# ME461_F28379D.net
KiCad netlist of a schematic drawn in EAGLE
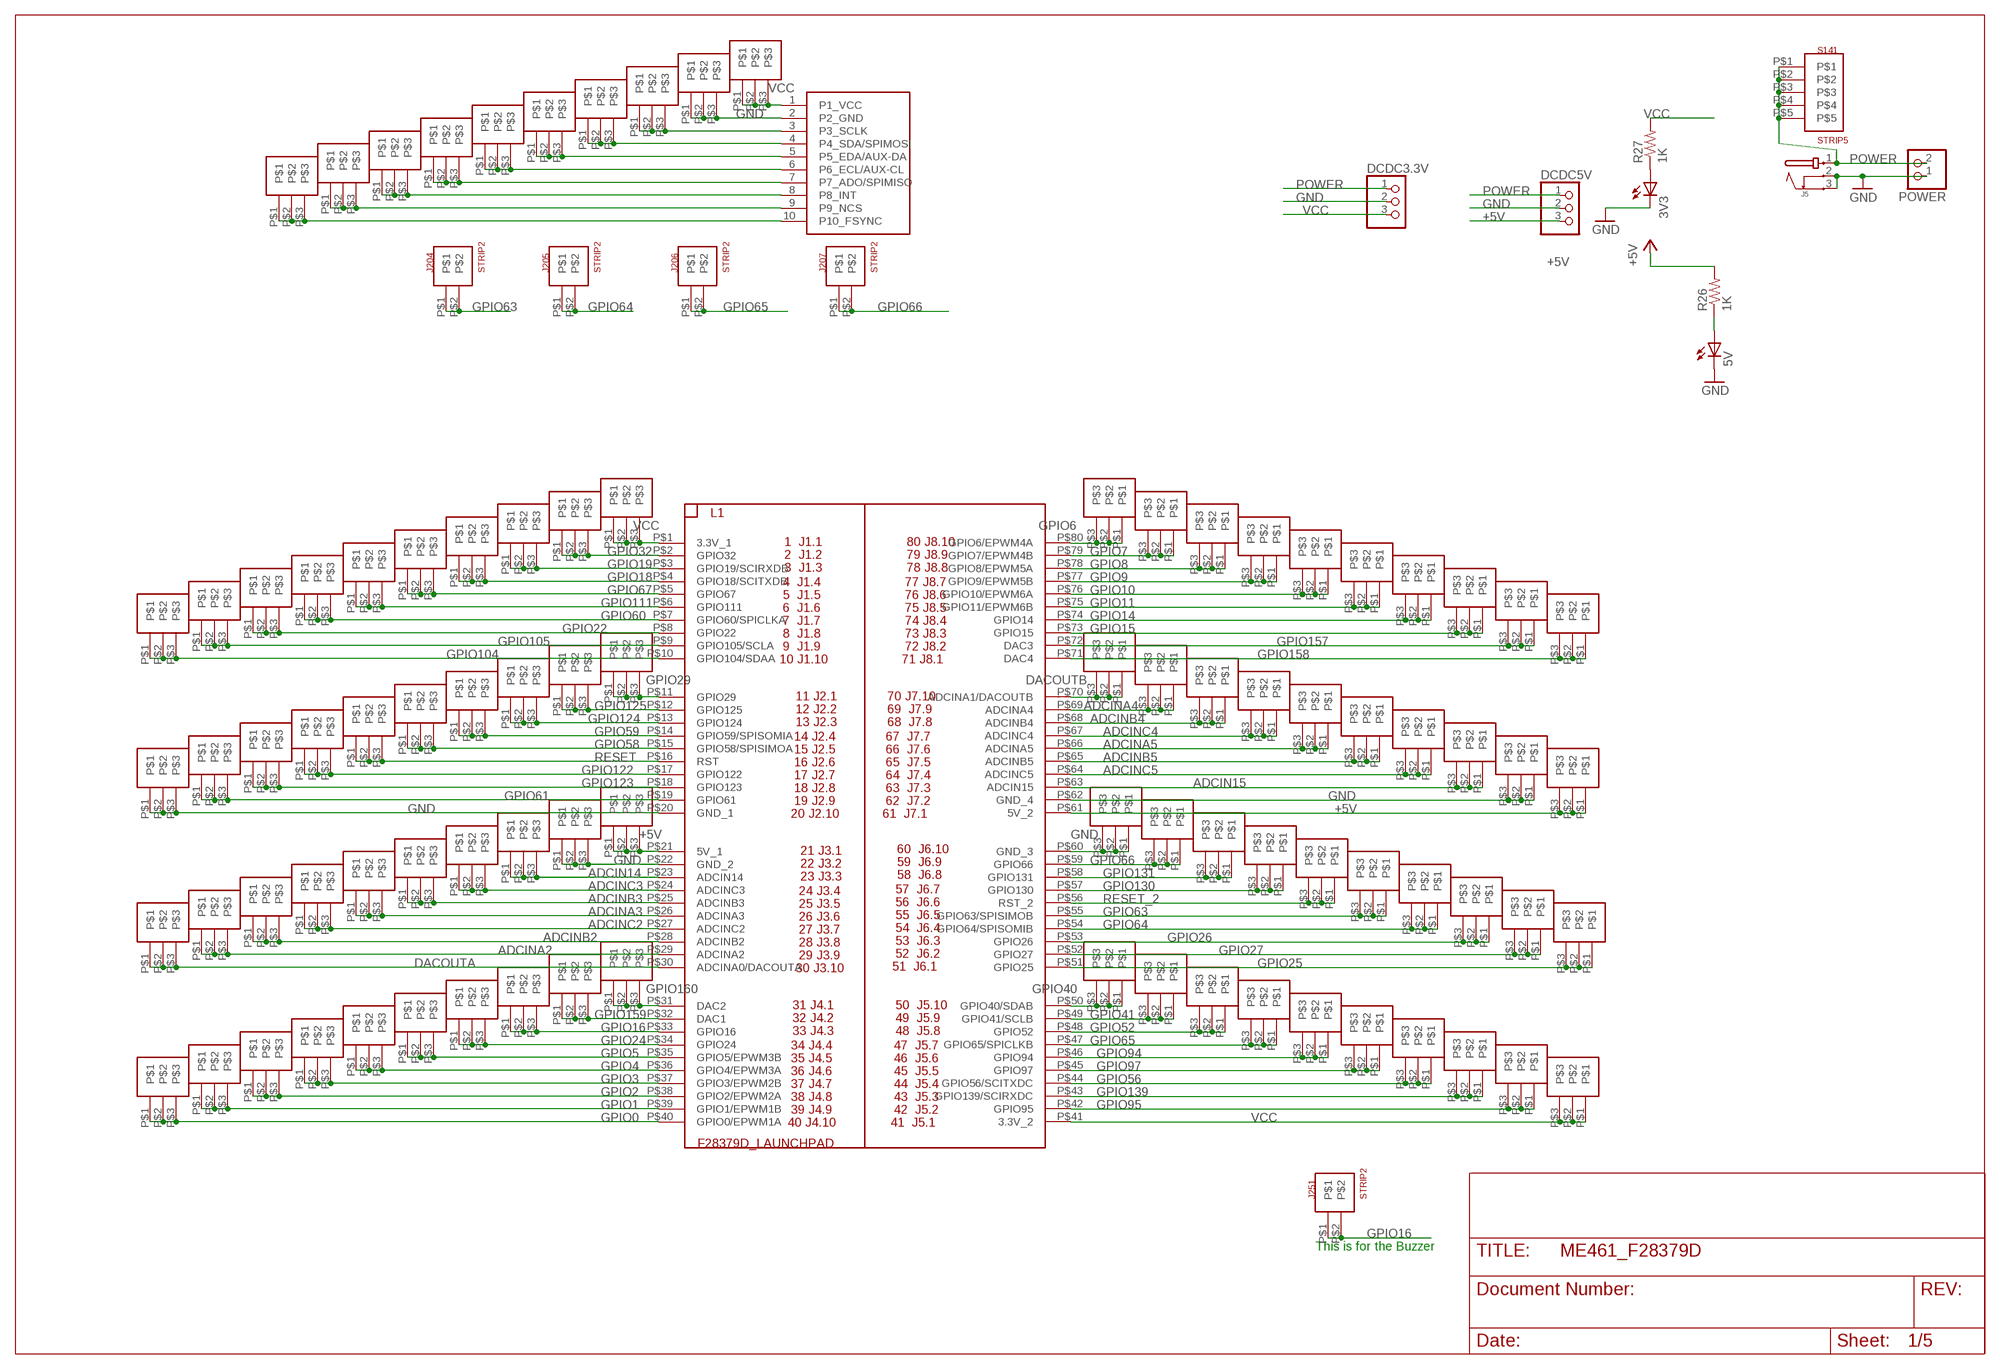
[diagram p0: schematic, sheet 1]
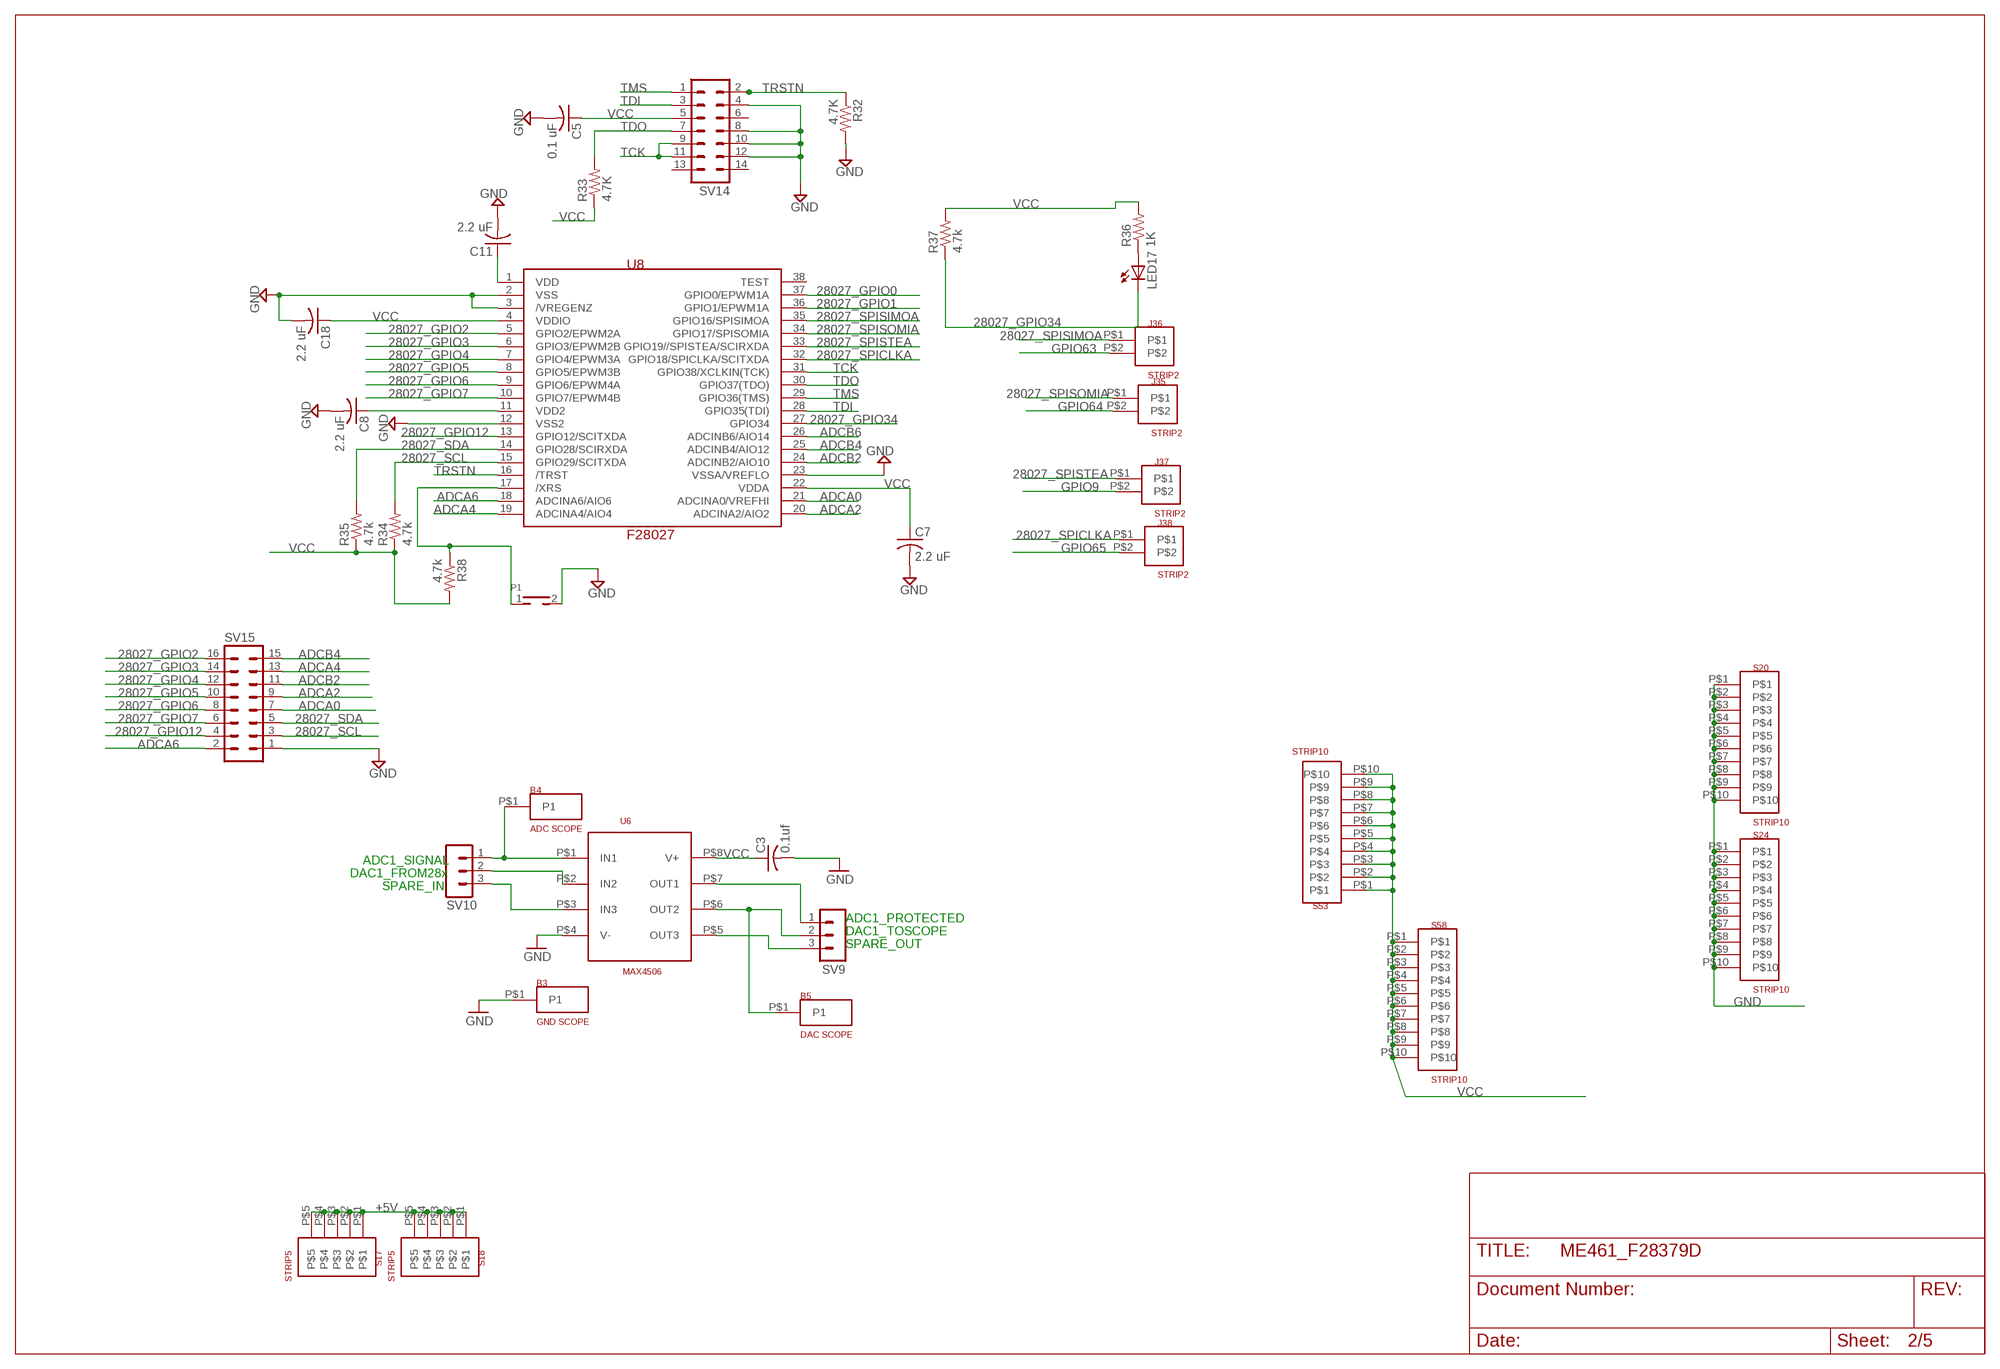
[diagram p1: schematic, sheet 2]
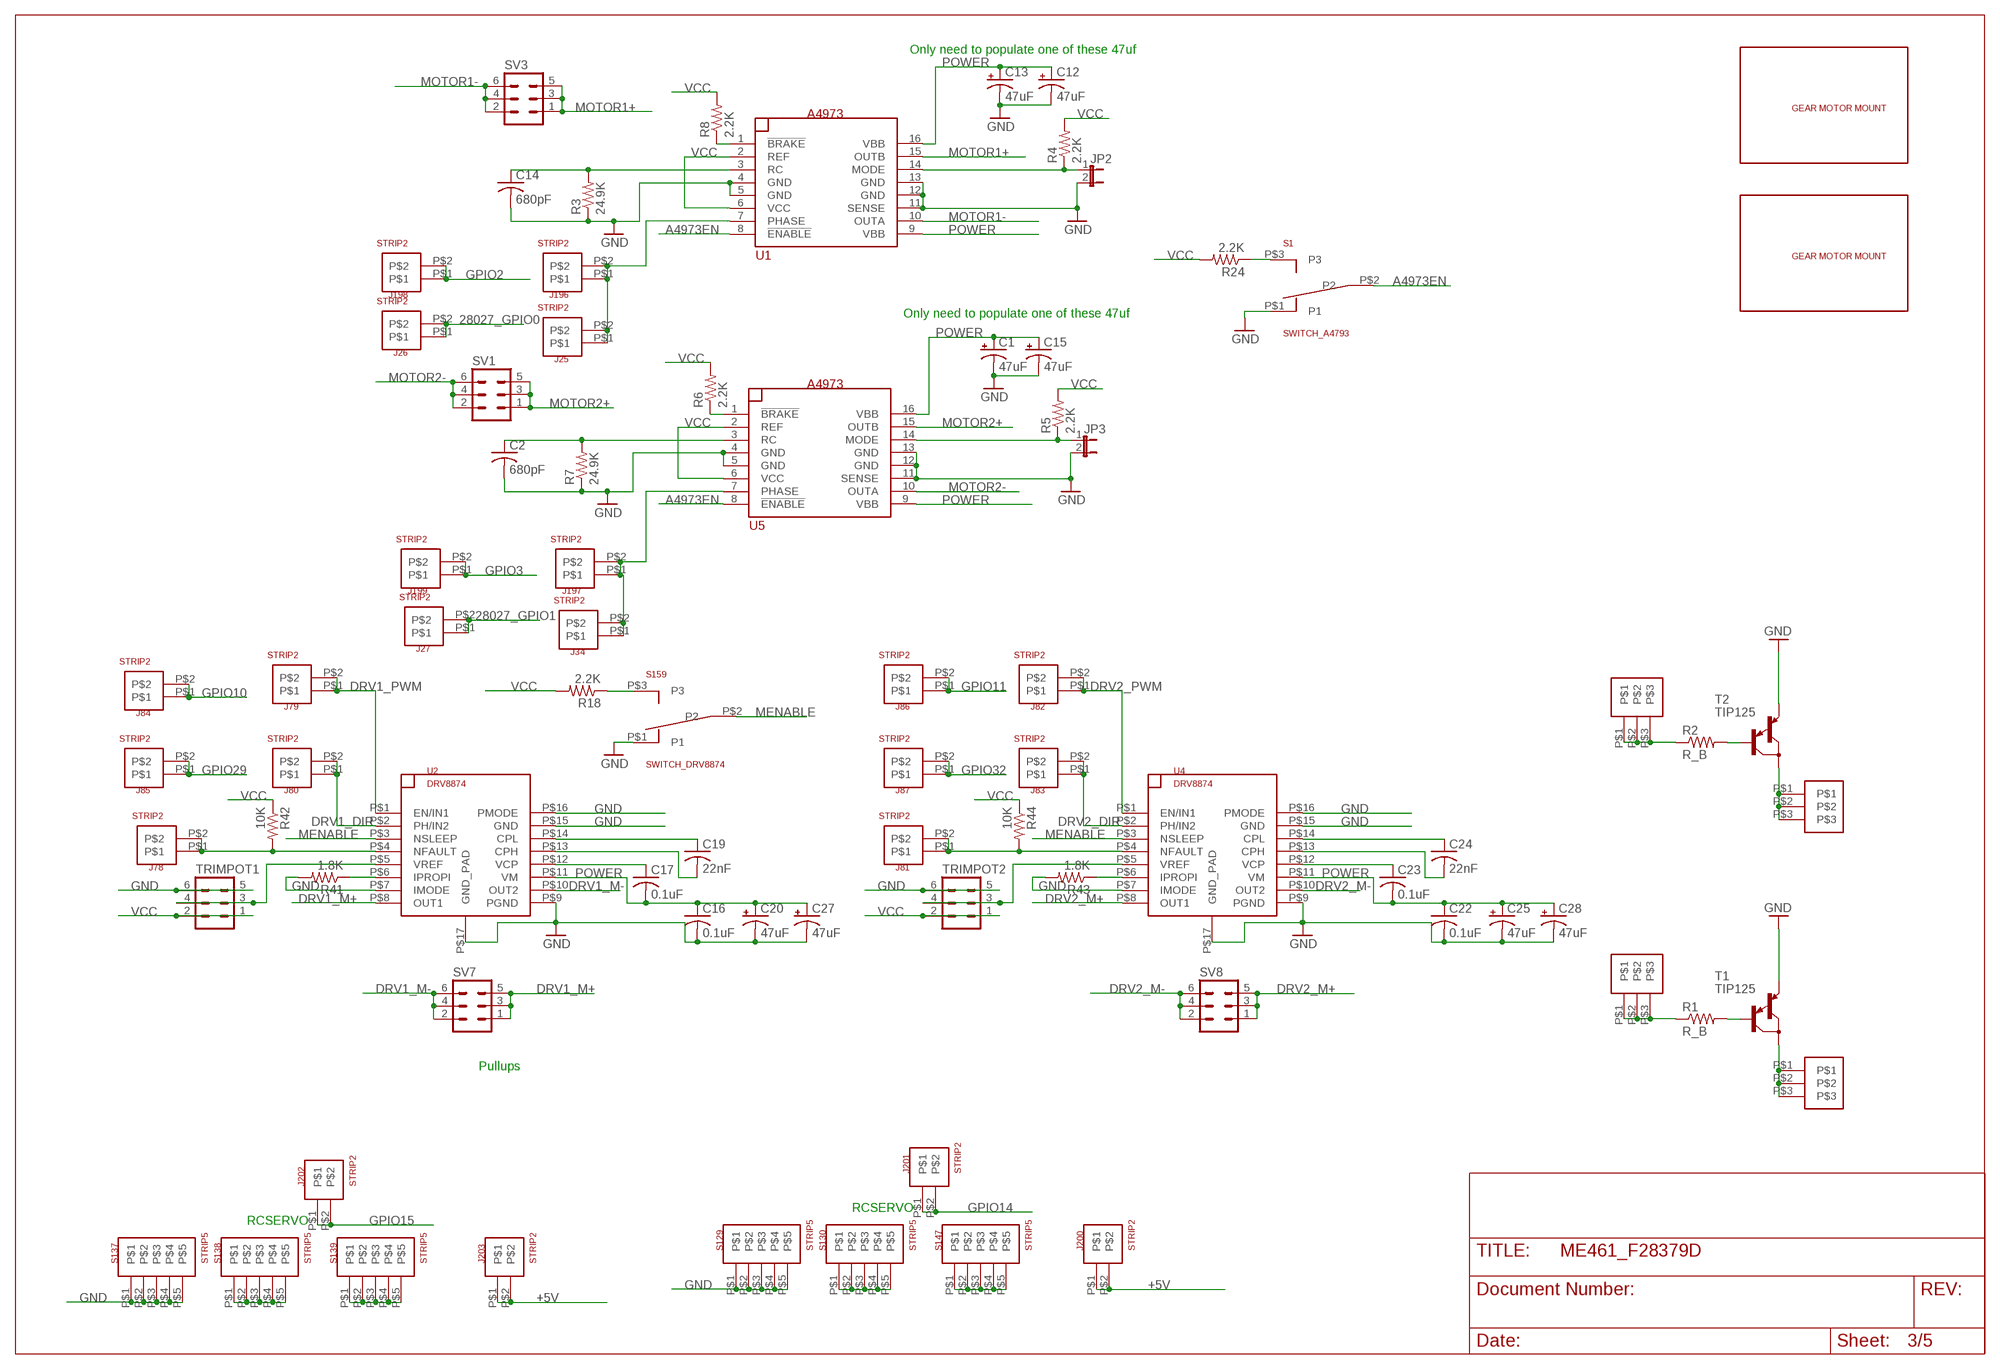
[diagram p2: schematic, sheet 3]
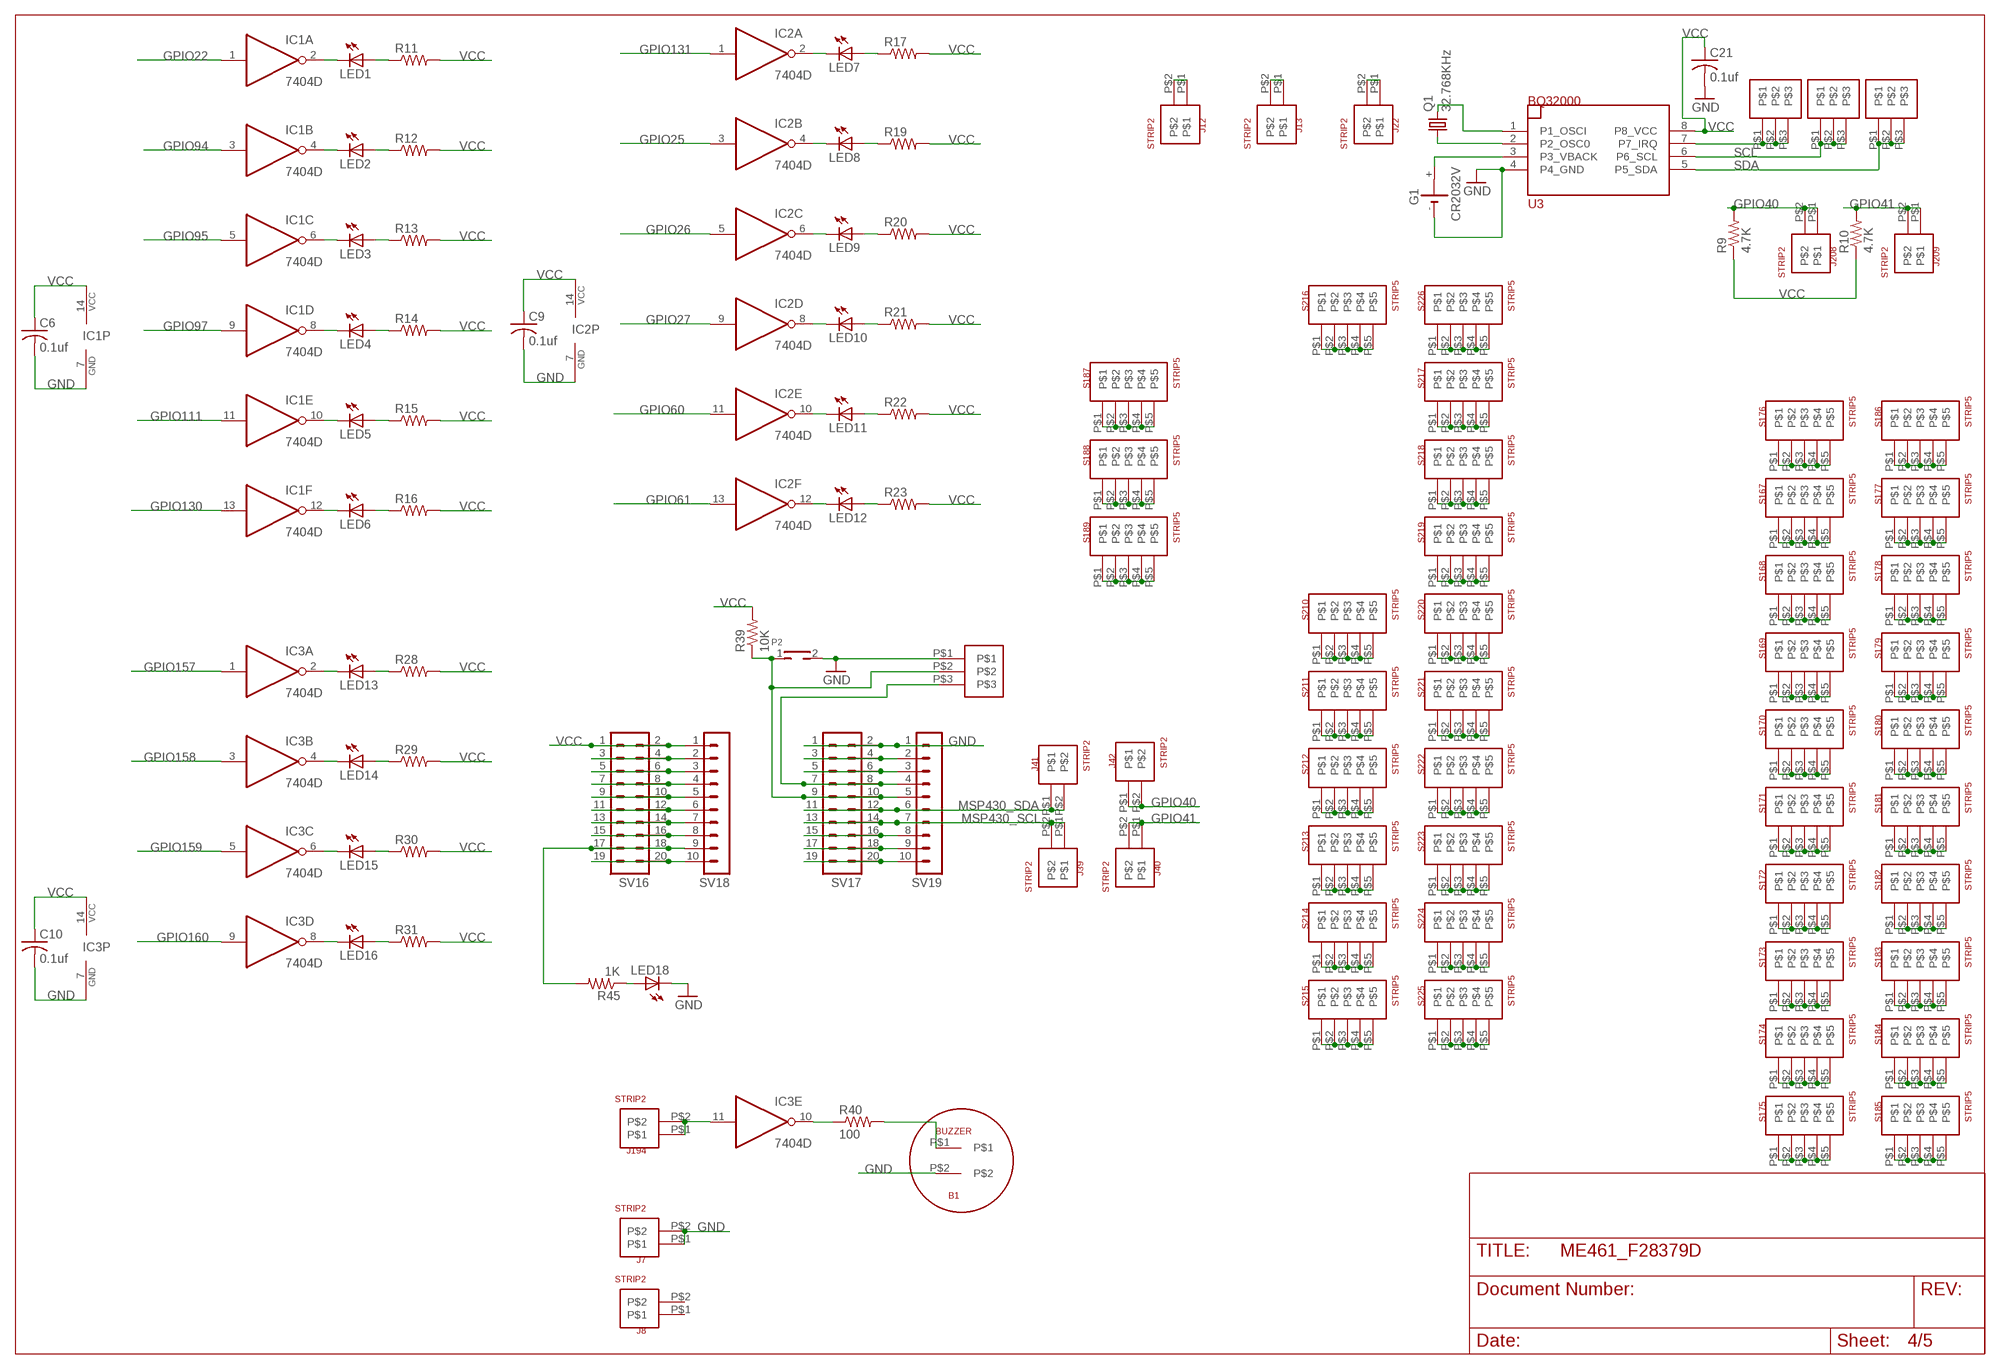
[diagram p3: schematic, sheet 4]
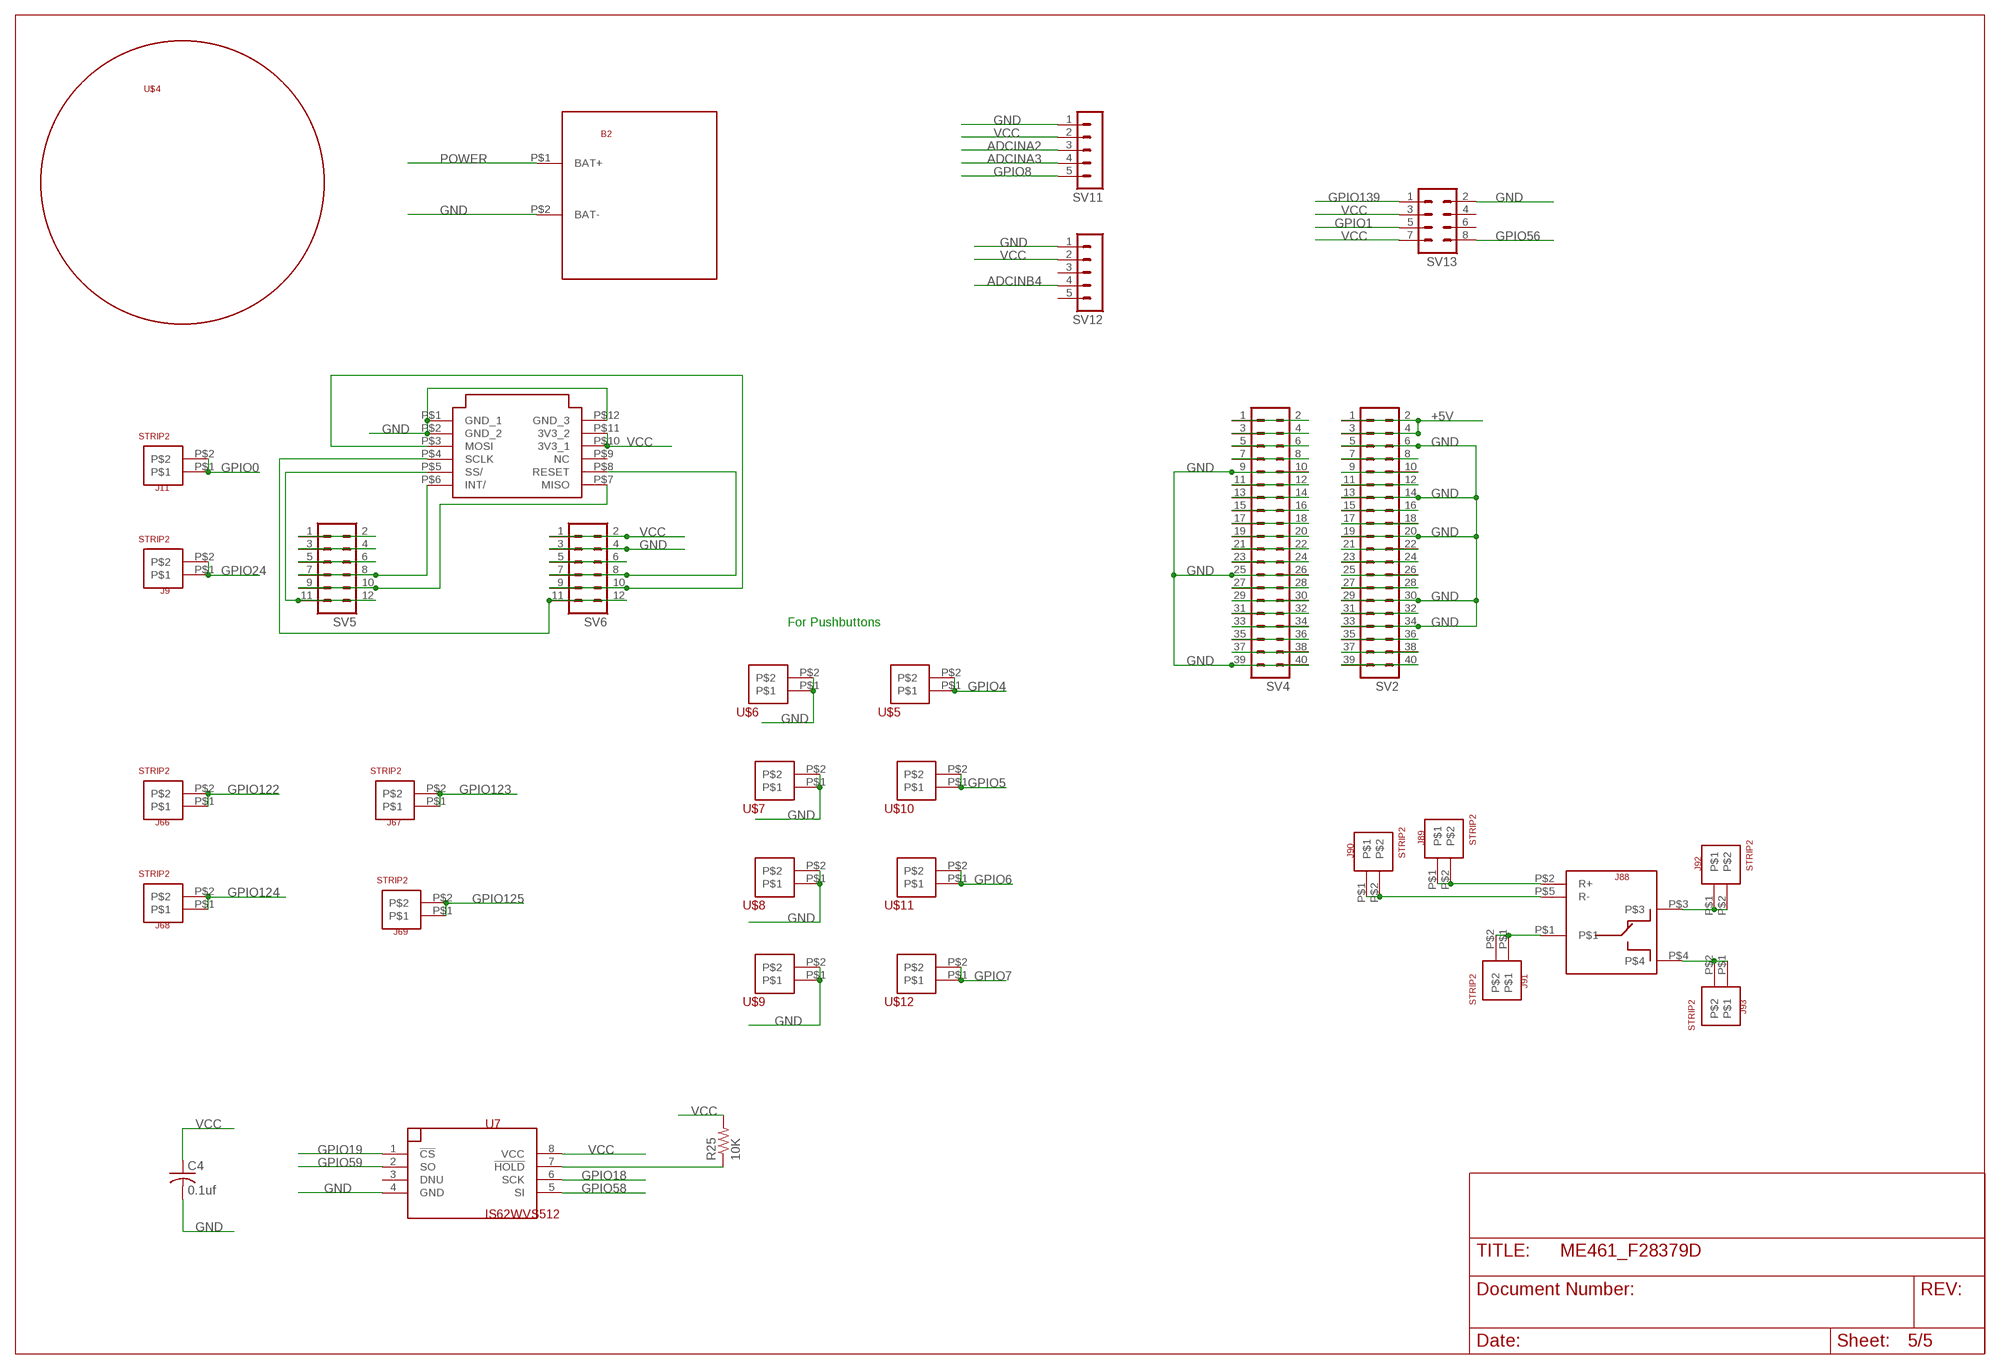
[diagram p4: schematic, sheet 5]

(export (version "E")
  (design (tool "Eeschema 10.0.6"))
  (components
    (comp (ref "B1")
      (value "BUZZER")
      (footprint "eagle-import:BUZZER")
      (libsource (lib "eagle-import") (part "BUZZER"))
    )
    (comp (ref "C6")
      (value "0.1uf")
      (footprint "eagle-import:C1206")
      (libsource (lib "eagle-import") (part "C-USC1206"))
    )
    (comp (ref "C9")
      (value "0.1uf")
      (footprint "eagle-import:C1206")
      (libsource (lib "eagle-import") (part "C-USC1206"))
    )
    (comp (ref "C10")
      (value "0.1uf")
      (footprint "eagle-import:C1206")
      (libsource (lib "eagle-import") (part "C-USC1206"))
    )
    (comp (ref "C21")
      (value "0.1uf")
      (footprint "eagle-import:C1206")
      (libsource (lib "eagle-import") (part "C-USC1206"))
    )
    (comp (ref "G1")
      (value "CR2032V")
      (footprint "eagle-import:CR2032V")
      (libsource (lib "eagle-import") (part "CR2032V"))
    )
    (comp (ref "IC1")
      (value "7404D")
      (footprint "eagle-import:SO14")
      (libsource (lib "eagle-import") (part "7404D"))
    )
    (comp (ref "IC2")
      (value "7404D")
      (footprint "eagle-import:SO14")
      (libsource (lib "eagle-import") (part "7404D"))
    )
    (comp (ref "IC3")
      (value "7404D")
      (footprint "eagle-import:SO14")
      (libsource (lib "eagle-import") (part "7404D"))
    )
    (comp (ref "J1")
      (value "STRIP3")
      (footprint "eagle-import:STRIP3")
      (libsource (lib "eagle-import") (part "STRIP3"))
    )
    (comp (ref "J2")
      (value "STRIP3")
      (footprint "eagle-import:STRIP3")
      (libsource (lib "eagle-import") (part "STRIP3"))
    )
    (comp (ref "J3")
      (value "STRIP3")
      (footprint "eagle-import:STRIP3")
      (libsource (lib "eagle-import") (part "STRIP3"))
    )
    (comp (ref "J7")
      (value "STRIP2")
      (footprint "eagle-import:STRIP2")
      (libsource (lib "eagle-import") (part "STRIP2"))
    )
    (comp (ref "J8")
      (value "STRIP2")
      (footprint "eagle-import:STRIP2")
      (libsource (lib "eagle-import") (part "STRIP2"))
    )
    (comp (ref "J12")
      (value "STRIP2")
      (footprint "eagle-import:STRIP2")
      (libsource (lib "eagle-import") (part "STRIP2"))
    )
    (comp (ref "J13")
      (value "STRIP2")
      (footprint "eagle-import:STRIP2")
      (libsource (lib "eagle-import") (part "STRIP2"))
    )
    (comp (ref "J22")
      (value "STRIP2")
      (footprint "eagle-import:STRIP2")
      (libsource (lib "eagle-import") (part "STRIP2"))
    )
    (comp (ref "J39")
      (value "STRIP2")
      (footprint "eagle-import:STRIP2")
      (libsource (lib "eagle-import") (part "STRIP2"))
    )
    (comp (ref "J40")
      (value "STRIP2")
      (footprint "eagle-import:STRIP2")
      (libsource (lib "eagle-import") (part "STRIP2"))
    )
    (comp (ref "J41")
      (value "STRIP2")
      (footprint "eagle-import:STRIP2")
      (libsource (lib "eagle-import") (part "STRIP2"))
    )
    (comp (ref "J42")
      (value "STRIP2")
      (footprint "eagle-import:STRIP2")
      (libsource (lib "eagle-import") (part "STRIP2"))
    )
    (comp (ref "J43")
      (value "STRIP3")
      (footprint "eagle-import:STRIP3")
      (libsource (lib "eagle-import") (part "STRIP3"))
    )
    (comp (ref "J194")
      (value "STRIP2")
      (footprint "eagle-import:STRIP2")
      (libsource (lib "eagle-import") (part "STRIP2"))
    )
    (comp (ref "J208")
      (value "STRIP2")
      (footprint "eagle-import:STRIP2")
      (libsource (lib "eagle-import") (part "STRIP2"))
    )
    (comp (ref "J209")
      (value "STRIP2")
      (footprint "eagle-import:STRIP2")
      (libsource (lib "eagle-import") (part "STRIP2"))
    )
    (comp (ref "LED1")
      (value "LEDCHIPLED_1206")
      (footprint "eagle-import:CHIPLED_1206")
      (libsource (lib "eagle-import") (part "LEDCHIPLED_1206"))
    )
    (comp (ref "LED2")
      (value "LEDCHIPLED_1206")
      (footprint "eagle-import:CHIPLED_1206")
      (libsource (lib "eagle-import") (part "LEDCHIPLED_1206"))
    )
    (comp (ref "LED3")
      (value "LEDCHIPLED_1206")
      (footprint "eagle-import:CHIPLED_1206")
      (libsource (lib "eagle-import") (part "LEDCHIPLED_1206"))
    )
    (comp (ref "LED4")
      (value "LEDCHIPLED_1206")
      (footprint "eagle-import:CHIPLED_1206")
      (libsource (lib "eagle-import") (part "LEDCHIPLED_1206"))
    )
    (comp (ref "LED5")
      (value "LEDCHIPLED_1206")
      (footprint "eagle-import:CHIPLED_1206")
      (libsource (lib "eagle-import") (part "LEDCHIPLED_1206"))
    )
    (comp (ref "LED6")
      (value "LEDCHIPLED_1206")
      (footprint "eagle-import:CHIPLED_1206")
      (libsource (lib "eagle-import") (part "LEDCHIPLED_1206"))
    )
    (comp (ref "LED7")
      (value "LEDCHIPLED_1206")
      (footprint "eagle-import:CHIPLED_1206")
      (libsource (lib "eagle-import") (part "LEDCHIPLED_1206"))
    )
    (comp (ref "LED8")
      (value "LEDCHIPLED_1206")
      (footprint "eagle-import:CHIPLED_1206")
      (libsource (lib "eagle-import") (part "LEDCHIPLED_1206"))
    )
    (comp (ref "LED9")
      (value "LEDCHIPLED_1206")
      (footprint "eagle-import:CHIPLED_1206")
      (libsource (lib "eagle-import") (part "LEDCHIPLED_1206"))
    )
    (comp (ref "LED10")
      (value "LEDCHIPLED_1206")
      (footprint "eagle-import:CHIPLED_1206")
      (libsource (lib "eagle-import") (part "LEDCHIPLED_1206"))
    )
    (comp (ref "LED11")
      (value "LEDCHIPLED_1206")
      (footprint "eagle-import:CHIPLED_1206")
      (libsource (lib "eagle-import") (part "LEDCHIPLED_1206"))
    )
    (comp (ref "LED12")
      (value "LEDCHIPLED_1206")
      (footprint "eagle-import:CHIPLED_1206")
      (libsource (lib "eagle-import") (part "LEDCHIPLED_1206"))
    )
    (comp (ref "LED13")
      (value "LEDCHIPLED_1206")
      (footprint "eagle-import:CHIPLED_1206")
      (libsource (lib "eagle-import") (part "LEDCHIPLED_1206"))
    )
    (comp (ref "LED14")
      (value "LEDCHIPLED_1206")
      (footprint "eagle-import:CHIPLED_1206")
      (libsource (lib "eagle-import") (part "LEDCHIPLED_1206"))
    )
    (comp (ref "LED15")
      (value "LEDCHIPLED_1206")
      (footprint "eagle-import:CHIPLED_1206")
      (libsource (lib "eagle-import") (part "LEDCHIPLED_1206"))
    )
    (comp (ref "LED16")
      (value "LEDCHIPLED_1206")
      (footprint "eagle-import:CHIPLED_1206")
      (libsource (lib "eagle-import") (part "LEDCHIPLED_1206"))
    )
    (comp (ref "LED18")
      (value "LEDCHIPLED_1206")
      (footprint "eagle-import:CHIPLED_1206")
      (libsource (lib "eagle-import") (part "LEDCHIPLED_1206"))
    )
    (comp (ref "P2")
      (value "TH_PUSHBOTTON")
      (footprint "eagle-import:TH_PUSHBUTTON")
      (libsource (lib "eagle-import") (part "TH_PUSHBOTTON"))
    )
    (comp (ref "Q1")
      (value "32.768KHz")
      (footprint "eagle-import:TC26H")
      (libsource (lib "eagle-import") (part "CRYTALTC26H"))
    )
    (comp (ref "R9")
      (value "4.7K")
      (footprint "eagle-import:R1206")
      (libsource (lib "eagle-import") (part "R-US_R1206"))
    )
    (comp (ref "R10")
      (value "4.7K")
      (footprint "eagle-import:R1206")
      (libsource (lib "eagle-import") (part "R-US_R1206"))
    )
    (comp (ref "R11")
      (value "R-US_R1206")
      (footprint "eagle-import:R1206")
      (libsource (lib "eagle-import") (part "R-US_R1206"))
    )
    (comp (ref "R12")
      (value "R-US_R1206")
      (footprint "eagle-import:R1206")
      (libsource (lib "eagle-import") (part "R-US_R1206"))
    )
    (comp (ref "R13")
      (value "R-US_R1206")
      (footprint "eagle-import:R1206")
      (libsource (lib "eagle-import") (part "R-US_R1206"))
    )
    (comp (ref "R14")
      (value "R-US_R1206")
      (footprint "eagle-import:R1206")
      (libsource (lib "eagle-import") (part "R-US_R1206"))
    )
    (comp (ref "R15")
      (value "R-US_R1206")
      (footprint "eagle-import:R1206")
      (libsource (lib "eagle-import") (part "R-US_R1206"))
    )
    (comp (ref "R16")
      (value "R-US_R1206")
      (footprint "eagle-import:R1206")
      (libsource (lib "eagle-import") (part "R-US_R1206"))
    )
    (comp (ref "R17")
      (value "R-US_R1206")
      (footprint "eagle-import:R1206")
      (libsource (lib "eagle-import") (part "R-US_R1206"))
    )
    (comp (ref "R19")
      (value "R-US_R1206")
      (footprint "eagle-import:R1206")
      (libsource (lib "eagle-import") (part "R-US_R1206"))
    )
    (comp (ref "R20")
      (value "R-US_R1206")
      (footprint "eagle-import:R1206")
      (libsource (lib "eagle-import") (part "R-US_R1206"))
    )
    (comp (ref "R21")
      (value "R-US_R1206")
      (footprint "eagle-import:R1206")
      (libsource (lib "eagle-import") (part "R-US_R1206"))
    )
    (comp (ref "R22")
      (value "R-US_R1206")
      (footprint "eagle-import:R1206")
      (libsource (lib "eagle-import") (part "R-US_R1206"))
    )
    (comp (ref "R23")
      (value "R-US_R1206")
      (footprint "eagle-import:R1206")
      (libsource (lib "eagle-import") (part "R-US_R1206"))
    )
    (comp (ref "R28")
      (value "R-US_R1206")
      (footprint "eagle-import:R1206")
      (libsource (lib "eagle-import") (part "R-US_R1206"))
    )
    (comp (ref "R29")
      (value "R-US_R1206")
      (footprint "eagle-import:R1206")
      (libsource (lib "eagle-import") (part "R-US_R1206"))
    )
    (comp (ref "R30")
      (value "R-US_R1206")
      (footprint "eagle-import:R1206")
      (libsource (lib "eagle-import") (part "R-US_R1206"))
    )
    (comp (ref "R31")
      (value "R-US_R1206")
      (footprint "eagle-import:R1206")
      (libsource (lib "eagle-import") (part "R-US_R1206"))
    )
    (comp (ref "R39")
      (value "10K")
      (footprint "eagle-import:R1206")
      (libsource (lib "eagle-import") (part "R-US_R1206"))
    )
    (comp (ref "R40")
      (value "100")
      (footprint "eagle-import:R1206")
      (libsource (lib "eagle-import") (part "R-US_R1206"))
    )
    (comp (ref "R45")
      (value "1K")
      (footprint "eagle-import:R1206")
      (libsource (lib "eagle-import") (part "R-US_R1206"))
    )
    (comp (ref "S167")
      (value "STRIP5")
      (footprint "eagle-import:STRIP5")
      (libsource (lib "eagle-import") (part "STRIP5"))
    )
    (comp (ref "S168")
      (value "STRIP5")
      (footprint "eagle-import:STRIP5")
      (libsource (lib "eagle-import") (part "STRIP5"))
    )
    (comp (ref "S169")
      (value "STRIP5")
      (footprint "eagle-import:STRIP5")
      (libsource (lib "eagle-import") (part "STRIP5"))
    )
    (comp (ref "S170")
      (value "STRIP5")
      (footprint "eagle-import:STRIP5")
      (libsource (lib "eagle-import") (part "STRIP5"))
    )
    (comp (ref "S171")
      (value "STRIP5")
      (footprint "eagle-import:STRIP5")
      (libsource (lib "eagle-import") (part "STRIP5"))
    )
    (comp (ref "S172")
      (value "STRIP5")
      (footprint "eagle-import:STRIP5")
      (libsource (lib "eagle-import") (part "STRIP5"))
    )
    (comp (ref "S173")
      (value "STRIP5")
      (footprint "eagle-import:STRIP5")
      (libsource (lib "eagle-import") (part "STRIP5"))
    )
    (comp (ref "S174")
      (value "STRIP5")
      (footprint "eagle-import:STRIP5")
      (libsource (lib "eagle-import") (part "STRIP5"))
    )
    (comp (ref "S175")
      (value "STRIP5")
      (footprint "eagle-import:STRIP5")
      (libsource (lib "eagle-import") (part "STRIP5"))
    )
    (comp (ref "S176")
      (value "STRIP5")
      (footprint "eagle-import:STRIP5")
      (libsource (lib "eagle-import") (part "STRIP5"))
    )
    (comp (ref "S177")
      (value "STRIP5")
      (footprint "eagle-import:STRIP5")
      (libsource (lib "eagle-import") (part "STRIP5"))
    )
    (comp (ref "S178")
      (value "STRIP5")
      (footprint "eagle-import:STRIP5")
      (libsource (lib "eagle-import") (part "STRIP5"))
    )
    (comp (ref "S179")
      (value "STRIP5")
      (footprint "eagle-import:STRIP5")
      (libsource (lib "eagle-import") (part "STRIP5"))
    )
    (comp (ref "S180")
      (value "STRIP5")
      (footprint "eagle-import:STRIP5")
      (libsource (lib "eagle-import") (part "STRIP5"))
    )
    (comp (ref "S181")
      (value "STRIP5")
      (footprint "eagle-import:STRIP5")
      (libsource (lib "eagle-import") (part "STRIP5"))
    )
    (comp (ref "S182")
      (value "STRIP5")
      (footprint "eagle-import:STRIP5")
      (libsource (lib "eagle-import") (part "STRIP5"))
    )
    (comp (ref "S183")
      (value "STRIP5")
      (footprint "eagle-import:STRIP5")
      (libsource (lib "eagle-import") (part "STRIP5"))
    )
    (comp (ref "S184")
      (value "STRIP5")
      (footprint "eagle-import:STRIP5")
      (libsource (lib "eagle-import") (part "STRIP5"))
    )
    (comp (ref "S185")
      (value "STRIP5")
      (footprint "eagle-import:STRIP5")
      (libsource (lib "eagle-import") (part "STRIP5"))
    )
    (comp (ref "S186")
      (value "STRIP5")
      (footprint "eagle-import:STRIP5")
      (libsource (lib "eagle-import") (part "STRIP5"))
    )
    (comp (ref "S187")
      (value "STRIP5")
      (footprint "eagle-import:STRIP5")
      (libsource (lib "eagle-import") (part "STRIP5"))
    )
    (comp (ref "S188")
      (value "STRIP5")
      (footprint "eagle-import:STRIP5")
      (libsource (lib "eagle-import") (part "STRIP5"))
    )
    (comp (ref "S189")
      (value "STRIP5")
      (footprint "eagle-import:STRIP5")
      (libsource (lib "eagle-import") (part "STRIP5"))
    )
    (comp (ref "S210")
      (value "STRIP5")
      (footprint "eagle-import:STRIP5")
      (libsource (lib "eagle-import") (part "STRIP5"))
    )
    (comp (ref "S211")
      (value "STRIP5")
      (footprint "eagle-import:STRIP5")
      (libsource (lib "eagle-import") (part "STRIP5"))
    )
    (comp (ref "S212")
      (value "STRIP5")
      (footprint "eagle-import:STRIP5")
      (libsource (lib "eagle-import") (part "STRIP5"))
    )
    (comp (ref "S213")
      (value "STRIP5")
      (footprint "eagle-import:STRIP5")
      (libsource (lib "eagle-import") (part "STRIP5"))
    )
    (comp (ref "S214")
      (value "STRIP5")
      (footprint "eagle-import:STRIP5")
      (libsource (lib "eagle-import") (part "STRIP5"))
    )
    (comp (ref "S215")
      (value "STRIP5")
      (footprint "eagle-import:STRIP5")
      (libsource (lib "eagle-import") (part "STRIP5"))
    )
    (comp (ref "S216")
      (value "STRIP5")
      (footprint "eagle-import:STRIP5")
      (libsource (lib "eagle-import") (part "STRIP5"))
    )
    (comp (ref "S217")
      (value "STRIP5")
      (footprint "eagle-import:STRIP5")
      (libsource (lib "eagle-import") (part "STRIP5"))
    )
    (comp (ref "S218")
      (value "STRIP5")
      (footprint "eagle-import:STRIP5")
      (libsource (lib "eagle-import") (part "STRIP5"))
    )
    (comp (ref "S219")
      (value "STRIP5")
      (footprint "eagle-import:STRIP5")
      (libsource (lib "eagle-import") (part "STRIP5"))
    )
    (comp (ref "S220")
      (value "STRIP5")
      (footprint "eagle-import:STRIP5")
      (libsource (lib "eagle-import") (part "STRIP5"))
    )
    (comp (ref "S221")
      (value "STRIP5")
      (footprint "eagle-import:STRIP5")
      (libsource (lib "eagle-import") (part "STRIP5"))
    )
    (comp (ref "S222")
      (value "STRIP5")
      (footprint "eagle-import:STRIP5")
      (libsource (lib "eagle-import") (part "STRIP5"))
    )
    (comp (ref "S223")
      (value "STRIP5")
      (footprint "eagle-import:STRIP5")
      (libsource (lib "eagle-import") (part "STRIP5"))
    )
    (comp (ref "S224")
      (value "STRIP5")
      (footprint "eagle-import:STRIP5")
      (libsource (lib "eagle-import") (part "STRIP5"))
    )
    (comp (ref "S225")
      (value "STRIP5")
      (footprint "eagle-import:STRIP5")
      (libsource (lib "eagle-import") (part "STRIP5"))
    )
    (comp (ref "S226")
      (value "STRIP5")
      (footprint "eagle-import:STRIP5")
      (libsource (lib "eagle-import") (part "STRIP5"))
    )
    (comp (ref "SV16")
      (value "MA10-2")
      (footprint "eagle-import:MA10-2")
      (libsource (lib "eagle-import") (part "MA10-2"))
    )
    (comp (ref "SV17")
      (value "MA10-2")
      (footprint "eagle-import:MA10-2")
      (libsource (lib "eagle-import") (part "MA10-2"))
    )
    (comp (ref "SV18")
      (value "MA10-1")
      (footprint "eagle-import:MA10-1")
      (libsource (lib "eagle-import") (part "MA10-1"))
    )
    (comp (ref "SV19")
      (value "MA10-1")
      (footprint "eagle-import:MA10-1")
      (libsource (lib "eagle-import") (part "MA10-1"))
    )
    (comp (ref "U3")
      (value "BQ32000")
      (footprint "eagle-import:SO08")
      (libsource (lib "eagle-import") (part "BQ32000"))
    )
    (comp (ref "3V3")
      (value "LEDCHIPLED_1206")
      (footprint "eagle-import:CHIPLED_1206")
      (libsource (lib "eagle-import") (part "LEDCHIPLED_1206"))
    )
    (comp (ref "5V")
      (value "LEDCHIPLED_1206")
      (footprint "eagle-import:CHIPLED_1206")
      (libsource (lib "eagle-import") (part "LEDCHIPLED_1206"))
    )
    (comp (ref "DCDC3.3V")
      (value "PINHD-1X3")
      (footprint "eagle-import:1X03")
      (libsource (lib "eagle-import") (part "PINHD-1X3"))
    )
    (comp (ref "DCDC5V")
      (value "PINHD-1X3")
      (footprint "eagle-import:1X03")
      (libsource (lib "eagle-import") (part "PINHD-1X3"))
    )
    (comp (ref "J5")
      (value "JACK-PMS")
      (footprint "eagle-import:JACK-PMS")
      (libsource (lib "eagle-import") (part "JACK-PMS"))
    )
    (comp (ref "J10")
      (value "STRIP3")
      (footprint "eagle-import:STRIP3")
      (libsource (lib "eagle-import") (part "STRIP3"))
    )
    (comp (ref "J14")
      (value "STRIP3")
      (footprint "eagle-import:STRIP3")
      (libsource (lib "eagle-import") (part "STRIP3"))
    )
    (comp (ref "J15")
      (value "STRIP3")
      (footprint "eagle-import:STRIP3")
      (libsource (lib "eagle-import") (part "STRIP3"))
    )
    (comp (ref "J16")
      (value "STRIP3")
      (footprint "eagle-import:STRIP3")
      (libsource (lib "eagle-import") (part "STRIP3"))
    )
    (comp (ref "J17")
      (value "STRIP3")
      (footprint "eagle-import:STRIP3")
      (libsource (lib "eagle-import") (part "STRIP3"))
    )
    (comp (ref "J18")
      (value "STRIP3")
      (footprint "eagle-import:STRIP3")
      (libsource (lib "eagle-import") (part "STRIP3"))
    )
    (comp (ref "J19")
      (value "STRIP3")
      (footprint "eagle-import:STRIP3")
      (libsource (lib "eagle-import") (part "STRIP3"))
    )
    (comp (ref "J20")
      (value "STRIP3")
      (footprint "eagle-import:STRIP3")
      (libsource (lib "eagle-import") (part "STRIP3"))
    )
    (comp (ref "J21")
      (value "STRIP3")
      (footprint "eagle-import:STRIP3")
      (libsource (lib "eagle-import") (part "STRIP3"))
    )
    (comp (ref "J28")
      (value "STRIP3")
      (footprint "eagle-import:STRIP3")
      (libsource (lib "eagle-import") (part "STRIP3"))
    )
    (comp (ref "J29")
      (value "STRIP3")
      (footprint "eagle-import:STRIP3")
      (libsource (lib "eagle-import") (part "STRIP3"))
    )
    (comp (ref "J30")
      (value "STRIP3")
      (footprint "eagle-import:STRIP3")
      (libsource (lib "eagle-import") (part "STRIP3"))
    )
    (comp (ref "J31")
      (value "STRIP3")
      (footprint "eagle-import:STRIP3")
      (libsource (lib "eagle-import") (part "STRIP3"))
    )
    (comp (ref "J32")
      (value "STRIP3")
      (footprint "eagle-import:STRIP3")
      (libsource (lib "eagle-import") (part "STRIP3"))
    )
    (comp (ref "J33")
      (value "STRIP3")
      (footprint "eagle-import:STRIP3")
      (libsource (lib "eagle-import") (part "STRIP3"))
    )
    (comp (ref "J98")
      (value "STRIP3")
      (footprint "eagle-import:STRIP3")
      (libsource (lib "eagle-import") (part "STRIP3"))
    )
    (comp (ref "J99")
      (value "STRIP3")
      (footprint "eagle-import:STRIP3")
      (libsource (lib "eagle-import") (part "STRIP3"))
    )
    (comp (ref "J100")
      (value "STRIP3")
      (footprint "eagle-import:STRIP3")
      (libsource (lib "eagle-import") (part "STRIP3"))
    )
    (comp (ref "J101")
      (value "STRIP3")
      (footprint "eagle-import:STRIP3")
      (libsource (lib "eagle-import") (part "STRIP3"))
    )
    (comp (ref "J102")
      (value "STRIP3")
      (footprint "eagle-import:STRIP3")
      (libsource (lib "eagle-import") (part "STRIP3"))
    )
    (comp (ref "J103")
      (value "STRIP3")
      (footprint "eagle-import:STRIP3")
      (libsource (lib "eagle-import") (part "STRIP3"))
    )
    (comp (ref "J104")
      (value "STRIP3")
      (footprint "eagle-import:STRIP3")
      (libsource (lib "eagle-import") (part "STRIP3"))
    )
    (comp (ref "J105")
      (value "STRIP3")
      (footprint "eagle-import:STRIP3")
      (libsource (lib "eagle-import") (part "STRIP3"))
    )
    (comp (ref "J106")
      (value "STRIP3")
      (footprint "eagle-import:STRIP3")
      (libsource (lib "eagle-import") (part "STRIP3"))
    )
    (comp (ref "J107")
      (value "STRIP3")
      (footprint "eagle-import:STRIP3")
      (libsource (lib "eagle-import") (part "STRIP3"))
    )
    (comp (ref "J108")
      (value "STRIP3")
      (footprint "eagle-import:STRIP3")
      (libsource (lib "eagle-import") (part "STRIP3"))
    )
    (comp (ref "J109")
      (value "STRIP3")
      (footprint "eagle-import:STRIP3")
      (libsource (lib "eagle-import") (part "STRIP3"))
    )
    (comp (ref "J110")
      (value "STRIP3")
      (footprint "eagle-import:STRIP3")
      (libsource (lib "eagle-import") (part "STRIP3"))
    )
    (comp (ref "J111")
      (value "STRIP3")
      (footprint "eagle-import:STRIP3")
      (libsource (lib "eagle-import") (part "STRIP3"))
    )
    (comp (ref "J112")
      (value "STRIP3")
      (footprint "eagle-import:STRIP3")
      (libsource (lib "eagle-import") (part "STRIP3"))
    )
    (comp (ref "J113")
      (value "STRIP3")
      (footprint "eagle-import:STRIP3")
      (libsource (lib "eagle-import") (part "STRIP3"))
    )
    (comp (ref "J114")
      (value "STRIP3")
      (footprint "eagle-import:STRIP3")
      (libsource (lib "eagle-import") (part "STRIP3"))
    )
    (comp (ref "J115")
      (value "STRIP3")
      (footprint "eagle-import:STRIP3")
      (libsource (lib "eagle-import") (part "STRIP3"))
    )
    (comp (ref "J116")
      (value "STRIP3")
      (footprint "eagle-import:STRIP3")
      (libsource (lib "eagle-import") (part "STRIP3"))
    )
    (comp (ref "J117")
      (value "STRIP3")
      (footprint "eagle-import:STRIP3")
      (libsource (lib "eagle-import") (part "STRIP3"))
    )
    (comp (ref "J118")
      (value "STRIP3")
      (footprint "eagle-import:STRIP3")
      (libsource (lib "eagle-import") (part "STRIP3"))
    )
    (comp (ref "J119")
      (value "STRIP3")
      (footprint "eagle-import:STRIP3")
      (libsource (lib "eagle-import") (part "STRIP3"))
    )
    (comp (ref "J120")
      (value "STRIP3")
      (footprint "eagle-import:STRIP3")
      (libsource (lib "eagle-import") (part "STRIP3"))
    )
    (comp (ref "J121")
      (value "STRIP3")
      (footprint "eagle-import:STRIP3")
      (libsource (lib "eagle-import") (part "STRIP3"))
    )
    (comp (ref "J122")
      (value "STRIP3")
      (footprint "eagle-import:STRIP3")
      (libsource (lib "eagle-import") (part "STRIP3"))
    )
    (comp (ref "J123")
      (value "STRIP3")
      (footprint "eagle-import:STRIP3")
      (libsource (lib "eagle-import") (part "STRIP3"))
    )
    (comp (ref "J124")
      (value "STRIP3")
      (footprint "eagle-import:STRIP3")
      (libsource (lib "eagle-import") (part "STRIP3"))
    )
    (comp (ref "J125")
      (value "STRIP3")
      (footprint "eagle-import:STRIP3")
      (libsource (lib "eagle-import") (part "STRIP3"))
    )
    (comp (ref "J126")
      (value "STRIP3")
      (footprint "eagle-import:STRIP3")
      (libsource (lib "eagle-import") (part "STRIP3"))
    )
    (comp (ref "J127")
      (value "STRIP3")
      (footprint "eagle-import:STRIP3")
      (libsource (lib "eagle-import") (part "STRIP3"))
    )
    (comp (ref "J128")
      (value "STRIP3")
      (footprint "eagle-import:STRIP3")
      (libsource (lib "eagle-import") (part "STRIP3"))
    )
    (comp (ref "J129")
      (value "STRIP3")
      (footprint "eagle-import:STRIP3")
      (libsource (lib "eagle-import") (part "STRIP3"))
    )
    (comp (ref "J130")
      (value "STRIP3")
      (footprint "eagle-import:STRIP3")
      (libsource (lib "eagle-import") (part "STRIP3"))
    )
    (comp (ref "J131")
      (value "STRIP3")
      (footprint "eagle-import:STRIP3")
      (libsource (lib "eagle-import") (part "STRIP3"))
    )
    (comp (ref "J132")
      (value "STRIP3")
      (footprint "eagle-import:STRIP3")
      (libsource (lib "eagle-import") (part "STRIP3"))
    )
    (comp (ref "J133")
      (value "STRIP3")
      (footprint "eagle-import:STRIP3")
      (libsource (lib "eagle-import") (part "STRIP3"))
    )
    (comp (ref "J134")
      (value "STRIP3")
      (footprint "eagle-import:STRIP3")
      (libsource (lib "eagle-import") (part "STRIP3"))
    )
    (comp (ref "J135")
      (value "STRIP3")
      (footprint "eagle-import:STRIP3")
      (libsource (lib "eagle-import") (part "STRIP3"))
    )
    (comp (ref "J136")
      (value "STRIP3")
      (footprint "eagle-import:STRIP3")
      (libsource (lib "eagle-import") (part "STRIP3"))
    )
    (comp (ref "J137")
      (value "STRIP3")
      (footprint "eagle-import:STRIP3")
      (libsource (lib "eagle-import") (part "STRIP3"))
    )
    (comp (ref "J138")
      (value "STRIP3")
      (footprint "eagle-import:STRIP3")
      (libsource (lib "eagle-import") (part "STRIP3"))
    )
    (comp (ref "J139")
      (value "STRIP3")
      (footprint "eagle-import:STRIP3")
      (libsource (lib "eagle-import") (part "STRIP3"))
    )
    (comp (ref "J140")
      (value "STRIP3")
      (footprint "eagle-import:STRIP3")
      (libsource (lib "eagle-import") (part "STRIP3"))
    )
    (comp (ref "J141")
      (value "STRIP3")
      (footprint "eagle-import:STRIP3")
      (libsource (lib "eagle-import") (part "STRIP3"))
    )
    (comp (ref "J142")
      (value "STRIP3")
      (footprint "eagle-import:STRIP3")
      (libsource (lib "eagle-import") (part "STRIP3"))
    )
    (comp (ref "J143")
      (value "STRIP3")
      (footprint "eagle-import:STRIP3")
      (libsource (lib "eagle-import") (part "STRIP3"))
    )
    (comp (ref "J144")
      (value "STRIP3")
      (footprint "eagle-import:STRIP3")
      (libsource (lib "eagle-import") (part "STRIP3"))
    )
    (comp (ref "J145")
      (value "STRIP3")
      (footprint "eagle-import:STRIP3")
      (libsource (lib "eagle-import") (part "STRIP3"))
    )
    (comp (ref "J146")
      (value "STRIP3")
      (footprint "eagle-import:STRIP3")
      (libsource (lib "eagle-import") (part "STRIP3"))
    )
    (comp (ref "J147")
      (value "STRIP3")
      (footprint "eagle-import:STRIP3")
      (libsource (lib "eagle-import") (part "STRIP3"))
    )
    (comp (ref "J148")
      (value "STRIP3")
      (footprint "eagle-import:STRIP3")
      (libsource (lib "eagle-import") (part "STRIP3"))
    )
    (comp (ref "J149")
      (value "STRIP3")
      (footprint "eagle-import:STRIP3")
      (libsource (lib "eagle-import") (part "STRIP3"))
    )
    (comp (ref "J150")
      (value "STRIP3")
      (footprint "eagle-import:STRIP3")
      (libsource (lib "eagle-import") (part "STRIP3"))
    )
    (comp (ref "J151")
      (value "STRIP3")
      (footprint "eagle-import:STRIP3")
      (libsource (lib "eagle-import") (part "STRIP3"))
    )
    (comp (ref "J152")
      (value "STRIP3")
      (footprint "eagle-import:STRIP3")
      (libsource (lib "eagle-import") (part "STRIP3"))
    )
    (comp (ref "J153")
      (value "STRIP3")
      (footprint "eagle-import:STRIP3")
      (libsource (lib "eagle-import") (part "STRIP3"))
    )
    (comp (ref "J154")
      (value "STRIP3")
      (footprint "eagle-import:STRIP3")
      (libsource (lib "eagle-import") (part "STRIP3"))
    )
    (comp (ref "J155")
      (value "STRIP3")
      (footprint "eagle-import:STRIP3")
      (libsource (lib "eagle-import") (part "STRIP3"))
    )
    (comp (ref "J156")
      (value "STRIP3")
      (footprint "eagle-import:STRIP3")
      (libsource (lib "eagle-import") (part "STRIP3"))
    )
    (comp (ref "J157")
      (value "STRIP3")
      (footprint "eagle-import:STRIP3")
      (libsource (lib "eagle-import") (part "STRIP3"))
    )
    (comp (ref "J158")
      (value "STRIP3")
      (footprint "eagle-import:STRIP3")
      (libsource (lib "eagle-import") (part "STRIP3"))
    )
    (comp (ref "J159")
      (value "STRIP3")
      (footprint "eagle-import:STRIP3")
      (libsource (lib "eagle-import") (part "STRIP3"))
    )
    (comp (ref "J160")
      (value "STRIP3")
      (footprint "eagle-import:STRIP3")
      (libsource (lib "eagle-import") (part "STRIP3"))
    )
    (comp (ref "J161")
      (value "STRIP3")
      (footprint "eagle-import:STRIP3")
      (libsource (lib "eagle-import") (part "STRIP3"))
    )
    (comp (ref "J162")
      (value "STRIP3")
      (footprint "eagle-import:STRIP3")
      (libsource (lib "eagle-import") (part "STRIP3"))
    )
    (comp (ref "J163")
      (value "STRIP3")
      (footprint "eagle-import:STRIP3")
      (libsource (lib "eagle-import") (part "STRIP3"))
    )
    (comp (ref "J164")
      (value "STRIP3")
      (footprint "eagle-import:STRIP3")
      (libsource (lib "eagle-import") (part "STRIP3"))
    )
    (comp (ref "J165")
      (value "STRIP3")
      (footprint "eagle-import:STRIP3")
      (libsource (lib "eagle-import") (part "STRIP3"))
    )
    (comp (ref "J166")
      (value "STRIP3")
      (footprint "eagle-import:STRIP3")
      (libsource (lib "eagle-import") (part "STRIP3"))
    )
    (comp (ref "J167")
      (value "STRIP3")
      (footprint "eagle-import:STRIP3")
      (libsource (lib "eagle-import") (part "STRIP3"))
    )
    (comp (ref "J168")
      (value "STRIP3")
      (footprint "eagle-import:STRIP3")
      (libsource (lib "eagle-import") (part "STRIP3"))
    )
    (comp (ref "J169")
      (value "STRIP3")
      (footprint "eagle-import:STRIP3")
      (libsource (lib "eagle-import") (part "STRIP3"))
    )
    (comp (ref "J170")
      (value "STRIP3")
      (footprint "eagle-import:STRIP3")
      (libsource (lib "eagle-import") (part "STRIP3"))
    )
    (comp (ref "J176")
      (value "STRIP3")
      (footprint "eagle-import:STRIP3")
      (libsource (lib "eagle-import") (part "STRIP3"))
    )
    (comp (ref "J177")
      (value "STRIP3")
      (footprint "eagle-import:STRIP3")
      (libsource (lib "eagle-import") (part "STRIP3"))
    )
    (comp (ref "J204")
      (value "STRIP2")
      (footprint "eagle-import:STRIP2")
      (libsource (lib "eagle-import") (part "STRIP2"))
    )
    (comp (ref "J205")
      (value "STRIP2")
      (footprint "eagle-import:STRIP2")
      (libsource (lib "eagle-import") (part "STRIP2"))
    )
    (comp (ref "J206")
      (value "STRIP2")
      (footprint "eagle-import:STRIP2")
      (libsource (lib "eagle-import") (part "STRIP2"))
    )
    (comp (ref "J207")
      (value "STRIP2")
      (footprint "eagle-import:STRIP2")
      (libsource (lib "eagle-import") (part "STRIP2"))
    )
    (comp (ref "J251")
      (value "STRIP2")
      (footprint "eagle-import:STRIP2")
      (libsource (lib "eagle-import") (part "STRIP2"))
    )
    (comp (ref "L1")
      (value "F28379D_LAUNCHPAD")
      (footprint "eagle-import:F28379D_LAUNCHPAD")
      (libsource (lib "eagle-import") (part "F28379D_LAUNCHPAD"))
    )
    (comp (ref "POWER")
      (value "PINHD-1X2")
      (footprint "eagle-import:1X02")
      (libsource (lib "eagle-import") (part "PINHD-1X2"))
    )
    (comp (ref "R26")
      (value "1K")
      (footprint "eagle-import:M1206")
      (libsource (lib "eagle-import") (part "R-US_M1206"))
    )
    (comp (ref "R27")
      (value "1K")
      (footprint "eagle-import:M1206")
      (libsource (lib "eagle-import") (part "R-US_M1206"))
    )
    (comp (ref "S141")
      (value "STRIP5")
      (footprint "eagle-import:STRIP5")
      (libsource (lib "eagle-import") (part "STRIP5"))
    )
    (comp (ref "U$1")
      (value "MPU-9250-BB")
      (footprint "eagle-import:MPU-9250-BB")
      (libsource (lib "eagle-import") (part "MPU-9250-BB"))
    )
    (comp (ref "B3")
      (value "GND SCOPE")
      (footprint "eagle-import:BANANA_MALE")
      (libsource (lib "eagle-import") (part "BANANA_MALE"))
    )
    (comp (ref "B4")
      (value "ADC SCOPE")
      (footprint "eagle-import:BANANA_MALE")
      (libsource (lib "eagle-import") (part "BANANA_MALE"))
    )
    (comp (ref "B5")
      (value "DAC SCOPE")
      (footprint "eagle-import:BANANA_MALE")
      (libsource (lib "eagle-import") (part "BANANA_MALE"))
    )
    (comp (ref "C3")
      (value "0.1uf")
      (footprint "eagle-import:C1206")
      (libsource (lib "eagle-import") (part "C-USC1206"))
    )
    (comp (ref "C5")
      (value "0.1 uF")
      (footprint "eagle-import:C1206")
      (libsource (lib "eagle-import") (part "C-USC1206"))
    )
    (comp (ref "C7")
      (value "2.2 uF")
      (footprint "eagle-import:C1206")
      (libsource (lib "eagle-import") (part "C-USC1206"))
    )
    (comp (ref "C8")
      (value "2.2 uF")
      (footprint "eagle-import:C1206")
      (libsource (lib "eagle-import") (part "C-USC1206"))
    )
    (comp (ref "C11")
      (value "2.2 uF")
      (footprint "eagle-import:C1206")
      (libsource (lib "eagle-import") (part "C-USC1206"))
    )
    (comp (ref "C18")
      (value "2.2 uF")
      (footprint "eagle-import:C1206")
      (libsource (lib "eagle-import") (part "C-USC1206"))
    )
    (comp (ref "J35")
      (value "STRIP2")
      (footprint "eagle-import:STRIP2")
      (libsource (lib "eagle-import") (part "STRIP2"))
    )
    (comp (ref "J36")
      (value "STRIP2")
      (footprint "eagle-import:STRIP2")
      (libsource (lib "eagle-import") (part "STRIP2"))
    )
    (comp (ref "J37")
      (value "STRIP2")
      (footprint "eagle-import:STRIP2")
      (libsource (lib "eagle-import") (part "STRIP2"))
    )
    (comp (ref "J38")
      (value "STRIP2")
      (footprint "eagle-import:STRIP2")
      (libsource (lib "eagle-import") (part "STRIP2"))
    )
    (comp (ref "LED17")
      (value "LEDCHIPLED_1206")
      (footprint "eagle-import:CHIPLED_1206")
      (libsource (lib "eagle-import") (part "LEDCHIPLED_1206"))
    )
    (comp (ref "P1")
      (value "TH_PUSHBOTTON")
      (footprint "eagle-import:TH_PUSHBUTTON")
      (libsource (lib "eagle-import") (part "TH_PUSHBOTTON"))
    )
    (comp (ref "R32")
      (value "4.7K")
      (footprint "eagle-import:M1206")
      (libsource (lib "eagle-import") (part "R-US_M1206"))
    )
    (comp (ref "R33")
      (value "4.7K")
      (footprint "eagle-import:M1206")
      (libsource (lib "eagle-import") (part "R-US_M1206"))
    )
    (comp (ref "R34")
      (value "4.7k")
      (footprint "eagle-import:M1206")
      (libsource (lib "eagle-import") (part "R-US_M1206"))
    )
    (comp (ref "R35")
      (value "4.7k")
      (footprint "eagle-import:M1206")
      (libsource (lib "eagle-import") (part "R-US_M1206"))
    )
    (comp (ref "R36")
      (value "1K")
      (footprint "eagle-import:M1206")
      (libsource (lib "eagle-import") (part "R-US_M1206"))
    )
    (comp (ref "R37")
      (value "4.7k")
      (footprint "eagle-import:M1206")
      (libsource (lib "eagle-import") (part "R-US_M1206"))
    )
    (comp (ref "R38")
      (value "4.7k")
      (footprint "eagle-import:M1206")
      (libsource (lib "eagle-import") (part "R-US_M1206"))
    )
    (comp (ref "S17")
      (value "STRIP5")
      (footprint "eagle-import:STRIP5")
      (libsource (lib "eagle-import") (part "STRIP5"))
    )
    (comp (ref "S18")
      (value "STRIP5")
      (footprint "eagle-import:STRIP5")
      (libsource (lib "eagle-import") (part "STRIP5"))
    )
    (comp (ref "S20")
      (value "STRIP10")
      (footprint "eagle-import:STRIP10")
      (libsource (lib "eagle-import") (part "STRIP10"))
    )
    (comp (ref "S24")
      (value "STRIP10")
      (footprint "eagle-import:STRIP10")
      (libsource (lib "eagle-import") (part "STRIP10"))
    )
    (comp (ref "S53")
      (value "STRIP10")
      (footprint "eagle-import:STRIP10")
      (libsource (lib "eagle-import") (part "STRIP10"))
    )
    (comp (ref "S58")
      (value "STRIP10")
      (footprint "eagle-import:STRIP10")
      (libsource (lib "eagle-import") (part "STRIP10"))
    )
    (comp (ref "SV9")
      (value "MA03-1")
      (footprint "eagle-import:MA03-1")
      (libsource (lib "eagle-import") (part "MA03-1"))
    )
    (comp (ref "SV10")
      (value "MA03-1")
      (footprint "eagle-import:MA03-1")
      (libsource (lib "eagle-import") (part "MA03-1"))
    )
    (comp (ref "SV14")
      (value "MA07-2")
      (footprint "eagle-import:MA07-2")
      (libsource (lib "eagle-import") (part "MA07-2"))
    )
    (comp (ref "SV15")
      (value "MA08-2")
      (footprint "eagle-import:MA08-2")
      (libsource (lib "eagle-import") (part "MA08-2"))
    )
    (comp (ref "U6")
      (value "MAX4506")
      (footprint "eagle-import:SOIC-8")
      (libsource (lib "eagle-import") (part "MAX4506-SOIC8"))
    )
    (comp (ref "U8")
      (value "F28027")
      (footprint "eagle-import:DA38")
      (libsource (lib "eagle-import") (part "TMS320F28027DAS"))
    )
    (comp (ref "C1")
      (value "47uF")
      (footprint "eagle-import:153CLV-0810")
      (libsource (lib "eagle-import") (part "CPOL-US153CLV-0810"))
    )
    (comp (ref "C2")
      (value "680pF")
      (footprint "eagle-import:C1206")
      (libsource (lib "eagle-import") (part "C-USC1206"))
    )
    (comp (ref "C12")
      (value "47uF")
      (footprint "eagle-import:153CLV-0810")
      (libsource (lib "eagle-import") (part "CPOL-US153CLV-0810"))
    )
    (comp (ref "C13")
      (value "47uF")
      (footprint "eagle-import:153CLV-0810")
      (libsource (lib "eagle-import") (part "CPOL-US153CLV-0810"))
    )
    (comp (ref "C14")
      (value "680pF")
      (footprint "eagle-import:C1206")
      (libsource (lib "eagle-import") (part "C-USC1206"))
    )
    (comp (ref "C15")
      (value "47uF")
      (footprint "eagle-import:153CLV-0810")
      (libsource (lib "eagle-import") (part "CPOL-US153CLV-0810"))
    )
    (comp (ref "C16")
      (value "0.1uF")
      (footprint "eagle-import:C1206")
      (libsource (lib "eagle-import") (part "C-USC1206"))
    )
    (comp (ref "C17")
      (value "0.1uF")
      (footprint "eagle-import:C1206")
      (libsource (lib "eagle-import") (part "C-USC1206"))
    )
    (comp (ref "C19")
      (value "22nF")
      (footprint "eagle-import:C1206")
      (libsource (lib "eagle-import") (part "C-USC1206"))
    )
    (comp (ref "C20")
      (value "47uF")
      (footprint "eagle-import:153CLV-0810")
      (libsource (lib "eagle-import") (part "CPOL-US153CLV-0810"))
    )
    (comp (ref "C22")
      (value "0.1uF")
      (footprint "eagle-import:C1206")
      (libsource (lib "eagle-import") (part "C-USC1206"))
    )
    (comp (ref "C23")
      (value "0.1uF")
      (footprint "eagle-import:C1206")
      (libsource (lib "eagle-import") (part "C-USC1206"))
    )
    (comp (ref "C24")
      (value "22nF")
      (footprint "eagle-import:C1206")
      (libsource (lib "eagle-import") (part "C-USC1206"))
    )
    (comp (ref "C25")
      (value "47uF")
      (footprint "eagle-import:153CLV-0810")
      (libsource (lib "eagle-import") (part "CPOL-US153CLV-0810"))
    )
    (comp (ref "C27")
      (value "47uF")
      (footprint "eagle-import:153CLV-0810")
      (libsource (lib "eagle-import") (part "CPOL-US153CLV-0810"))
    )
    (comp (ref "C28")
      (value "47uF")
      (footprint "eagle-import:153CLV-0810")
      (libsource (lib "eagle-import") (part "CPOL-US153CLV-0810"))
    )
    (comp (ref "J4")
      (value "STRIP3")
      (footprint "eagle-import:STRIP3")
      (libsource (lib "eagle-import") (part "STRIP3"))
    )
    (comp (ref "J6")
      (value "STRIP3")
      (footprint "eagle-import:STRIP3")
      (libsource (lib "eagle-import") (part "STRIP3"))
    )
    (comp (ref "J23")
      (value "STRIP3")
      (footprint "eagle-import:STRIP3")
      (libsource (lib "eagle-import") (part "STRIP3"))
    )
    (comp (ref "J24")
      (value "STRIP3")
      (footprint "eagle-import:STRIP3")
      (libsource (lib "eagle-import") (part "STRIP3"))
    )
    (comp (ref "J25")
      (value "STRIP2")
      (footprint "eagle-import:STRIP2")
      (libsource (lib "eagle-import") (part "STRIP2"))
    )
    (comp (ref "J26")
      (value "STRIP2")
      (footprint "eagle-import:STRIP2")
      (libsource (lib "eagle-import") (part "STRIP2"))
    )
    (comp (ref "J27")
      (value "STRIP2")
      (footprint "eagle-import:STRIP2")
      (libsource (lib "eagle-import") (part "STRIP2"))
    )
    (comp (ref "J34")
      (value "STRIP2")
      (footprint "eagle-import:STRIP2")
      (libsource (lib "eagle-import") (part "STRIP2"))
    )
    (comp (ref "J78")
      (value "STRIP2")
      (footprint "eagle-import:STRIP2")
      (libsource (lib "eagle-import") (part "STRIP2"))
    )
    (comp (ref "J79")
      (value "STRIP2")
      (footprint "eagle-import:STRIP2")
      (libsource (lib "eagle-import") (part "STRIP2"))
    )
    (comp (ref "J80")
      (value "STRIP2")
      (footprint "eagle-import:STRIP2")
      (libsource (lib "eagle-import") (part "STRIP2"))
    )
    (comp (ref "J81")
      (value "STRIP2")
      (footprint "eagle-import:STRIP2")
      (libsource (lib "eagle-import") (part "STRIP2"))
    )
    (comp (ref "J82")
      (value "STRIP2")
      (footprint "eagle-import:STRIP2")
      (libsource (lib "eagle-import") (part "STRIP2"))
    )
    (comp (ref "J83")
      (value "STRIP2")
      (footprint "eagle-import:STRIP2")
      (libsource (lib "eagle-import") (part "STRIP2"))
    )
    (comp (ref "J84")
      (value "STRIP2")
      (footprint "eagle-import:STRIP2")
      (libsource (lib "eagle-import") (part "STRIP2"))
    )
    (comp (ref "J85")
      (value "STRIP2")
      (footprint "eagle-import:STRIP2")
      (libsource (lib "eagle-import") (part "STRIP2"))
    )
    (comp (ref "J86")
      (value "STRIP2")
      (footprint "eagle-import:STRIP2")
      (libsource (lib "eagle-import") (part "STRIP2"))
    )
    (comp (ref "J87")
      (value "STRIP2")
      (footprint "eagle-import:STRIP2")
      (libsource (lib "eagle-import") (part "STRIP2"))
    )
    (comp (ref "J196")
      (value "STRIP2")
      (footprint "eagle-import:STRIP2")
      (libsource (lib "eagle-import") (part "STRIP2"))
    )
    (comp (ref "J197")
      (value "STRIP2")
      (footprint "eagle-import:STRIP2")
      (libsource (lib "eagle-import") (part "STRIP2"))
    )
    (comp (ref "J198")
      (value "STRIP2")
      (footprint "eagle-import:STRIP2")
      (libsource (lib "eagle-import") (part "STRIP2"))
    )
    (comp (ref "J199")
      (value "STRIP2")
      (footprint "eagle-import:STRIP2")
      (libsource (lib "eagle-import") (part "STRIP2"))
    )
    (comp (ref "J200")
      (value "STRIP2")
      (footprint "eagle-import:STRIP2")
      (libsource (lib "eagle-import") (part "STRIP2"))
    )
    (comp (ref "J201")
      (value "STRIP2")
      (footprint "eagle-import:STRIP2")
      (libsource (lib "eagle-import") (part "STRIP2"))
    )
    (comp (ref "J202")
      (value "STRIP2")
      (footprint "eagle-import:STRIP2")
      (libsource (lib "eagle-import") (part "STRIP2"))
    )
    (comp (ref "J203")
      (value "STRIP2")
      (footprint "eagle-import:STRIP2")
      (libsource (lib "eagle-import") (part "STRIP2"))
    )
    (comp (ref "JP2")
      (value "JP1E")
      (footprint "eagle-import:JP1")
      (libsource (lib "eagle-import") (part "JP1E"))
    )
    (comp (ref "JP3")
      (value "JP1E")
      (footprint "eagle-import:JP1")
      (libsource (lib "eagle-import") (part "JP1E"))
    )
    (comp (ref "R1")
      (value "R_B")
      (footprint "eagle-import:0207_10")
      (libsource (lib "eagle-import") (part "R-US_0207/10"))
    )
    (comp (ref "R2")
      (value "R_B")
      (footprint "eagle-import:0207_10")
      (libsource (lib "eagle-import") (part "R-US_0207/10"))
    )
    (comp (ref "R3")
      (value "24.9K")
      (footprint "eagle-import:M1206")
      (libsource (lib "eagle-import") (part "R-US_M1206"))
    )
    (comp (ref "R4")
      (value "2.2K")
      (footprint "eagle-import:M1206")
      (libsource (lib "eagle-import") (part "R-US_M1206"))
    )
    (comp (ref "R5")
      (value "2.2K")
      (footprint "eagle-import:M1206")
      (libsource (lib "eagle-import") (part "R-US_M1206"))
    )
    (comp (ref "R6")
      (value "2.2K")
      (footprint "eagle-import:M1206")
      (libsource (lib "eagle-import") (part "R-US_M1206"))
    )
    (comp (ref "R7")
      (value "24.9K")
      (footprint "eagle-import:M1206")
      (libsource (lib "eagle-import") (part "R-US_M1206"))
    )
    (comp (ref "R8")
      (value "2.2K")
      (footprint "eagle-import:M1206")
      (libsource (lib "eagle-import") (part "R-US_M1206"))
    )
    (comp (ref "R18")
      (value "2.2K")
      (footprint "eagle-import:M1206")
      (libsource (lib "eagle-import") (part "R-US_M1206"))
    )
    (comp (ref "R24")
      (value "2.2K")
      (footprint "eagle-import:M1206")
      (libsource (lib "eagle-import") (part "R-US_M1206"))
    )
    (comp (ref "R41")
      (value "1.8K")
      (footprint "eagle-import:M1206")
      (libsource (lib "eagle-import") (part "R-US_M1206"))
    )
    (comp (ref "R42")
      (value "10K")
      (footprint "eagle-import:M1206")
      (libsource (lib "eagle-import") (part "R-US_M1206"))
    )
    (comp (ref "R43")
      (value "1.8K")
      (footprint "eagle-import:M1206")
      (libsource (lib "eagle-import") (part "R-US_M1206"))
    )
    (comp (ref "R44")
      (value "10K")
      (footprint "eagle-import:M1206")
      (libsource (lib "eagle-import") (part "R-US_M1206"))
    )
    (comp (ref "S1")
      (value "SWITCH_A4793")
      (footprint "eagle-import:SWITCH_SLIDE")
      (libsource (lib "eagle-import") (part "SWITCH_SLIDE"))
    )
    (comp (ref "S129")
      (value "STRIP5")
      (footprint "eagle-import:STRIP5")
      (libsource (lib "eagle-import") (part "STRIP5"))
    )
    (comp (ref "S130")
      (value "STRIP5")
      (footprint "eagle-import:STRIP5")
      (libsource (lib "eagle-import") (part "STRIP5"))
    )
    (comp (ref "S137")
      (value "STRIP5")
      (footprint "eagle-import:STRIP5")
      (libsource (lib "eagle-import") (part "STRIP5"))
    )
    (comp (ref "S138")
      (value "STRIP5")
      (footprint "eagle-import:STRIP5")
      (libsource (lib "eagle-import") (part "STRIP5"))
    )
    (comp (ref "S139")
      (value "STRIP5")
      (footprint "eagle-import:STRIP5")
      (libsource (lib "eagle-import") (part "STRIP5"))
    )
    (comp (ref "S147")
      (value "STRIP5")
      (footprint "eagle-import:STRIP5")
      (libsource (lib "eagle-import") (part "STRIP5"))
    )
    (comp (ref "S159")
      (value "SWITCH_DRV8874")
      (footprint "eagle-import:SWITCH_SLIDE")
      (libsource (lib "eagle-import") (part "SWITCH_SLIDE"))
    )
    (comp (ref "SV1")
      (value "MA03-2")
      (footprint "eagle-import:MA03-2")
      (libsource (lib "eagle-import") (part "MA03-2"))
    )
    (comp (ref "SV3")
      (value "MA03-2")
      (footprint "eagle-import:MA03-2")
      (libsource (lib "eagle-import") (part "MA03-2"))
    )
    (comp (ref "SV7")
      (value "MA03-2")
      (footprint "eagle-import:MA03-2")
      (libsource (lib "eagle-import") (part "MA03-2"))
    )
    (comp (ref "SV8")
      (value "MA03-2")
      (footprint "eagle-import:MA03-2")
      (libsource (lib "eagle-import") (part "MA03-2"))
    )
    (comp (ref "T1")
      (value "TIP125")
      (footprint "eagle-import:TO220")
      (libsource (lib "eagle-import") (part "TIP125"))
    )
    (comp (ref "T2")
      (value "TIP125")
      (footprint "eagle-import:TO220")
      (libsource (lib "eagle-import") (part "TIP125"))
    )
    (comp (ref "TRIMPOT1")
      (value "MA03-2")
      (footprint "eagle-import:MA03-2")
      (libsource (lib "eagle-import") (part "MA03-2"))
    )
    (comp (ref "TRIMPOT2")
      (value "MA03-2")
      (footprint "eagle-import:MA03-2")
      (libsource (lib "eagle-import") (part "MA03-2"))
    )
    (comp (ref "U$2")
      (value "GEARMOTOR_MOUNT")
      (footprint "eagle-import:GEARMOTOR_MOUNT")
      (libsource (lib "eagle-import") (part "GEARMOTOR_MOUNT"))
    )
    (comp (ref "U$3")
      (value "GEARMOTOR_MOUNT")
      (footprint "eagle-import:GEARMOTOR_MOUNT")
      (libsource (lib "eagle-import") (part "GEARMOTOR_MOUNT"))
    )
    (comp (ref "U1")
      (value "A4973")
      (footprint "eagle-import:SO16W_LONGERPINS")
      (libsource (lib "eagle-import") (part "A3953"))
    )
    (comp (ref "U2")
      (value "DRV8874")
      (footprint "eagle-import:HTSSOP16")
      (libsource (lib "eagle-import") (part "DRV8874"))
    )
    (comp (ref "U4")
      (value "DRV8874")
      (footprint "eagle-import:HTSSOP16")
      (libsource (lib "eagle-import") (part "DRV8874"))
    )
    (comp (ref "U5")
      (value "A4973")
      (footprint "eagle-import:SO16W_LONGERPINS")
      (libsource (lib "eagle-import") (part "A3953"))
    )
    (comp (ref "B2")
      (value "BATTERY_4AA_HOLDER")
      (footprint "eagle-import:BATTERY_4AA_HOLDER")
      (libsource (lib "eagle-import") (part "BATTERY_4AA_HOLDER"))
    )
    (comp (ref "C4")
      (value "0.1uf")
      (footprint "eagle-import:C1206")
      (libsource (lib "eagle-import") (part "C-USC1206"))
    )
    (comp (ref "ETH1")
      (value "USR_ES1_W5500")
      (footprint "eagle-import:USR_ES1_W5500")
      (libsource (lib "eagle-import") (part "USR_ES1_W5500"))
    )
    (comp (ref "J9")
      (value "STRIP2")
      (footprint "eagle-import:STRIP2")
      (libsource (lib "eagle-import") (part "STRIP2"))
    )
    (comp (ref "J11")
      (value "STRIP2")
      (footprint "eagle-import:STRIP2")
      (libsource (lib "eagle-import") (part "STRIP2"))
    )
    (comp (ref "J66")
      (value "STRIP2")
      (footprint "eagle-import:STRIP2")
      (libsource (lib "eagle-import") (part "STRIP2"))
    )
    (comp (ref "J67")
      (value "STRIP2")
      (footprint "eagle-import:STRIP2")
      (libsource (lib "eagle-import") (part "STRIP2"))
    )
    (comp (ref "J68")
      (value "STRIP2")
      (footprint "eagle-import:STRIP2")
      (libsource (lib "eagle-import") (part "STRIP2"))
    )
    (comp (ref "J69")
      (value "STRIP2")
      (footprint "eagle-import:STRIP2")
      (libsource (lib "eagle-import") (part "STRIP2"))
    )
    (comp (ref "J88")
      (value "RELAY_JQC-3F_5V")
      (footprint "eagle-import:RELAY_JQC-3F_5V")
      (libsource (lib "eagle-import") (part "RELAY_JQC-3F_5V"))
    )
    (comp (ref "J89")
      (value "STRIP2")
      (footprint "eagle-import:STRIP2")
      (libsource (lib "eagle-import") (part "STRIP2"))
    )
    (comp (ref "J90")
      (value "STRIP2")
      (footprint "eagle-import:STRIP2")
      (libsource (lib "eagle-import") (part "STRIP2"))
    )
    (comp (ref "J91")
      (value "STRIP2")
      (footprint "eagle-import:STRIP2")
      (libsource (lib "eagle-import") (part "STRIP2"))
    )
    (comp (ref "J92")
      (value "STRIP2")
      (footprint "eagle-import:STRIP2")
      (libsource (lib "eagle-import") (part "STRIP2"))
    )
    (comp (ref "J93")
      (value "STRIP2")
      (footprint "eagle-import:STRIP2")
      (libsource (lib "eagle-import") (part "STRIP2"))
    )
    (comp (ref "R25")
      (value "10K")
      (footprint "eagle-import:M1206")
      (libsource (lib "eagle-import") (part "R-US_M1206"))
    )
    (comp (ref "SV2")
      (value "MA20-2")
      (footprint "eagle-import:MA20-2")
      (libsource (lib "eagle-import") (part "MA20-2"))
    )
    (comp (ref "SV4")
      (value "MA20-2")
      (footprint "eagle-import:MA20-2")
      (libsource (lib "eagle-import") (part "MA20-2"))
    )
    (comp (ref "SV5")
      (value "MA06-2")
      (footprint "eagle-import:MA06-2")
      (libsource (lib "eagle-import") (part "MA06-2"))
    )
    (comp (ref "SV6")
      (value "MA06-2")
      (footprint "eagle-import:MA06-2")
      (libsource (lib "eagle-import") (part "MA06-2"))
    )
    (comp (ref "SV11")
      (value "MA05-1")
      (footprint "eagle-import:MA05-1")
      (libsource (lib "eagle-import") (part "MA05-1"))
    )
    (comp (ref "SV12")
      (value "MA05-1")
      (footprint "eagle-import:MA05-1")
      (libsource (lib "eagle-import") (part "MA05-1"))
    )
    (comp (ref "SV13")
      (value "MA04-2")
      (footprint "eagle-import:MA04-2")
      (libsource (lib "eagle-import") (part "MA04-2"))
    )
    (comp (ref "U$4")
      (value "CASTERWHEEL")
      (footprint "eagle-import:CASTERWHEEL")
      (libsource (lib "eagle-import") (part "CASTERWHEEL"))
    )
    (comp (ref "U$5")
      (value "2PIN50MIL")
      (footprint "eagle-import:2PIN50MIL")
      (libsource (lib "eagle-import") (part "2PIN50MIL"))
    )
    (comp (ref "U$6")
      (value "2PIN50MIL")
      (footprint "eagle-import:2PIN50MIL")
      (libsource (lib "eagle-import") (part "2PIN50MIL"))
    )
    (comp (ref "U$7")
      (value "2PIN50MIL")
      (footprint "eagle-import:2PIN50MIL")
      (libsource (lib "eagle-import") (part "2PIN50MIL"))
    )
    (comp (ref "U$8")
      (value "2PIN50MIL")
      (footprint "eagle-import:2PIN50MIL")
      (libsource (lib "eagle-import") (part "2PIN50MIL"))
    )
    (comp (ref "U$9")
      (value "2PIN50MIL")
      (footprint "eagle-import:2PIN50MIL")
      (libsource (lib "eagle-import") (part "2PIN50MIL"))
    )
    (comp (ref "U$10")
      (value "2PIN50MIL")
      (footprint "eagle-import:2PIN50MIL")
      (libsource (lib "eagle-import") (part "2PIN50MIL"))
    )
    (comp (ref "U$11")
      (value "2PIN50MIL")
      (footprint "eagle-import:2PIN50MIL")
      (libsource (lib "eagle-import") (part "2PIN50MIL"))
    )
    (comp (ref "U$12")
      (value "2PIN50MIL")
      (footprint "eagle-import:2PIN50MIL")
      (libsource (lib "eagle-import") (part "2PIN50MIL"))
    )
    (comp (ref "U7")
      (value "IS62WVS512")
      (footprint "eagle-import:SO08")
      (libsource (lib "eagle-import") (part "IS62WVS512"))
    )
  )
  (nets
    (net (code "1") (name "+5V") (class "Default")
      (node (ref "DCDC5V") (pin "3") (pinfunction "3_3") (pintype "passive"))
      (node (ref "J103") (pin "P$1") (pinfunction "P$1_P$1") (pintype "bidirectional"))
      (node (ref "J103") (pin "P$2") (pinfunction "P$2_P$2") (pintype "bidirectional"))
      (node (ref "J103") (pin "P$3") (pinfunction "P$3_P$3") (pintype "bidirectional"))
      (node (ref "J152") (pin "P$1") (pinfunction "P$1_P$1") (pintype "bidirectional"))
      (node (ref "J152") (pin "P$2") (pinfunction "P$2_P$2") (pintype "bidirectional"))
      (node (ref "J152") (pin "P$3") (pinfunction "P$3_P$3") (pintype "bidirectional"))
      (node (ref "J200") (pin "P$1") (pinfunction "P$1_P$1") (pintype "bidirectional"))
      (node (ref "J200") (pin "P$2") (pinfunction "P$2_P$2") (pintype "bidirectional"))
      (node (ref "J203") (pin "P$1") (pinfunction "P$1_P$1") (pintype "bidirectional"))
      (node (ref "J203") (pin "P$2") (pinfunction "P$2_P$2") (pintype "bidirectional"))
      (node (ref "L1") (pin "P$21") (pinfunction "5V_1_P$21") (pintype "bidirectional"))
      (node (ref "L1") (pin "P$61") (pinfunction "5V_2_P$61") (pintype "bidirectional"))
      (node (ref "R26") (pin "2") (pinfunction "2_2") (pintype "passive"))
      (node (ref "S17") (pin "P$1") (pinfunction "P$1_P$1") (pintype "bidirectional"))
      (node (ref "S17") (pin "P$2") (pinfunction "P$2_P$2") (pintype "bidirectional"))
      (node (ref "S17") (pin "P$3") (pinfunction "P$3_P$3") (pintype "bidirectional"))
      (node (ref "S17") (pin "P$4") (pinfunction "P$4_P$4") (pintype "bidirectional"))
      (node (ref "S17") (pin "P$5") (pinfunction "P$5_P$5") (pintype "bidirectional"))
      (node (ref "S18") (pin "P$1") (pinfunction "P$1_P$1") (pintype "bidirectional"))
      (node (ref "S18") (pin "P$2") (pinfunction "P$2_P$2") (pintype "bidirectional"))
      (node (ref "S18") (pin "P$3") (pinfunction "P$3_P$3") (pintype "bidirectional"))
      (node (ref "S18") (pin "P$4") (pinfunction "P$4_P$4") (pintype "bidirectional"))
      (node (ref "S18") (pin "P$5") (pinfunction "P$5_P$5") (pintype "bidirectional"))
      (node (ref "SV2") (pin "1") (pinfunction "1_1") (pintype "passive"))
      (node (ref "SV2") (pin "2") (pinfunction "2_2") (pintype "passive"))
      (node (ref "SV2") (pin "3") (pinfunction "3_3") (pintype "passive"))
      (node (ref "SV2") (pin "4") (pinfunction "4_4") (pintype "passive"))
    )
    (net (code "2") (name "28027_GPIO0") (class "Default")
      (node (ref "J26") (pin "P$1") (pinfunction "P$1_P$1") (pintype "bidirectional"))
      (node (ref "J26") (pin "P$2") (pinfunction "P$2_P$2") (pintype "bidirectional"))
      (node (ref "U8") (pin "37") (pinfunction "GPIO0/EPWM1A_37") (pintype "bidirectional"))
    )
    (net (code "3") (name "28027_GPIO1") (class "Default")
      (node (ref "J27") (pin "P$1") (pinfunction "P$1_P$1") (pintype "bidirectional"))
      (node (ref "J27") (pin "P$2") (pinfunction "P$2_P$2") (pintype "bidirectional"))
      (node (ref "U8") (pin "36") (pinfunction "GPIO1/EPWM1A_36") (pintype "bidirectional"))
    )
    (net (code "4") (name "28027_GPIO2") (class "Default")
      (node (ref "SV15") (pin "16") (pinfunction "16_16") (pintype "passive"))
      (node (ref "U8") (pin "5") (pinfunction "GPIO2/EPWM2A_5") (pintype "bidirectional"))
    )
    (net (code "5") (name "28027_GPIO3") (class "Default")
      (node (ref "SV15") (pin "14") (pinfunction "14_14") (pintype "passive"))
      (node (ref "U8") (pin "6") (pinfunction "GPIO3/EPWM2B_6") (pintype "bidirectional"))
    )
    (net (code "6") (name "28027_GPIO4") (class "Default")
      (node (ref "SV15") (pin "12") (pinfunction "12_12") (pintype "passive"))
      (node (ref "U8") (pin "7") (pinfunction "GPIO4/EPWM3A_7") (pintype "bidirectional"))
    )
    (net (code "7") (name "28027_GPIO5") (class "Default")
      (node (ref "SV15") (pin "10") (pinfunction "10_10") (pintype "passive"))
      (node (ref "U8") (pin "8") (pinfunction "GPIO5/EPWM3B_8") (pintype "bidirectional"))
    )
    (net (code "8") (name "28027_GPIO6") (class "Default")
      (node (ref "SV15") (pin "8") (pinfunction "8_8") (pintype "passive"))
      (node (ref "U8") (pin "9") (pinfunction "GPIO6/EPWM4A_9") (pintype "bidirectional"))
    )
    (net (code "9") (name "28027_GPIO7") (class "Default")
      (node (ref "SV15") (pin "6") (pinfunction "6_6") (pintype "passive"))
      (node (ref "U8") (pin "10") (pinfunction "GPIO7/EPWM4B_10") (pintype "bidirectional"))
    )
    (net (code "10") (name "28027_GPIO12") (class "Default")
      (node (ref "SV15") (pin "4") (pinfunction "4_4") (pintype "passive"))
      (node (ref "U8") (pin "13") (pinfunction "GPIO12/SCITXDA_13") (pintype "bidirectional"))
    )
    (net (code "11") (name "28027_GPIO34") (class "Default")
      (node (ref "LED17") (pin "C") (pinfunction "C_C") (pintype "passive"))
      (node (ref "R37") (pin "1") (pinfunction "1_1") (pintype "passive"))
      (node (ref "U8") (pin "27") (pinfunction "GPIO34_27") (pintype "bidirectional"))
    )
    (net (code "12") (name "28027_SCL") (class "Default")
      (node (ref "R34") (pin "2") (pinfunction "2_2") (pintype "passive"))
      (node (ref "SV15") (pin "3") (pinfunction "3_3") (pintype "passive"))
      (node (ref "U8") (pin "15") (pinfunction "GPIO29/SCITXDA_15") (pintype "bidirectional"))
    )
    (net (code "13") (name "28027_SDA") (class "Default")
      (node (ref "R35") (pin "2") (pinfunction "2_2") (pintype "passive"))
      (node (ref "SV15") (pin "5") (pinfunction "5_5") (pintype "passive"))
      (node (ref "U8") (pin "14") (pinfunction "GPIO28/SCIRXDA_14") (pintype "bidirectional"))
    )
    (net (code "14") (name "28027_SPICLKA") (class "Default")
      (node (ref "J38") (pin "P$1") (pinfunction "P$1_P$1") (pintype "bidirectional"))
      (node (ref "U8") (pin "32") (pinfunction "GPIO18/SPICLKA/SCITXDA_32") (pintype "bidirectional"))
    )
    (net (code "15") (name "28027_SPISIMOA") (class "Default")
      (node (ref "J36") (pin "P$1") (pinfunction "P$1_P$1") (pintype "bidirectional"))
      (node (ref "U8") (pin "35") (pinfunction "GPIO16/SPISIMOA_35") (pintype "bidirectional"))
    )
    (net (code "16") (name "28027_SPISOMIA") (class "Default")
      (node (ref "J35") (pin "P$1") (pinfunction "P$1_P$1") (pintype "bidirectional"))
      (node (ref "U8") (pin "34") (pinfunction "GPIO17/SPISOMIA_34") (pintype "bidirectional"))
    )
    (net (code "17") (name "28027_SPISTEA") (class "Default")
      (node (ref "J37") (pin "P$1") (pinfunction "P$1_P$1") (pintype "bidirectional"))
      (node (ref "U8") (pin "33") (pinfunction "GPIO19//SPISTEA/SCIRXDA_33") (pintype "bidirectional"))
    )
    (net (code "18") (name "A4973EN") (class "Default")
      (node (ref "S1") (pin "P$2") (pinfunction "P2_P$2") (pintype "bidirectional"))
      (node (ref "U1") (pin "8") (pinfunction "~{ENABLE}_8") (pintype "bidirectional"))
      (node (ref "U5") (pin "8") (pinfunction "~{ENABLE}_8") (pintype "bidirectional"))
    )
    (net (code "19") (name "ADCA0") (class "Default")
      (node (ref "SV15") (pin "7") (pinfunction "7_7") (pintype "passive"))
      (node (ref "U8") (pin "21") (pinfunction "ADCINA0/VREFHI_21") (pintype "bidirectional"))
    )
    (net (code "20") (name "ADCA2") (class "Default")
      (node (ref "SV15") (pin "9") (pinfunction "9_9") (pintype "passive"))
      (node (ref "U8") (pin "20") (pinfunction "ADCINA2/AIO2_20") (pintype "bidirectional"))
    )
    (net (code "21") (name "ADCA4") (class "Default")
      (node (ref "SV15") (pin "13") (pinfunction "13_13") (pintype "passive"))
      (node (ref "U8") (pin "19") (pinfunction "ADCINA4/AIO4_19") (pintype "bidirectional"))
    )
    (net (code "22") (name "ADCA6") (class "Default")
      (node (ref "SV15") (pin "2") (pinfunction "2_2") (pintype "passive"))
      (node (ref "U8") (pin "18") (pinfunction "ADCINA6/AIO6_18") (pintype "bidirectional"))
    )
    (net (code "23") (name "ADCB2") (class "Default")
      (node (ref "SV15") (pin "11") (pinfunction "11_11") (pintype "passive"))
      (node (ref "U8") (pin "24") (pinfunction "ADCINB2/AIO10_24") (pintype "bidirectional"))
    )
    (net (code "24") (name "ADCB4") (class "Default")
      (node (ref "SV15") (pin "15") (pinfunction "15_15") (pintype "passive"))
      (node (ref "U8") (pin "25") (pinfunction "ADCINB4/AIO12_25") (pintype "bidirectional"))
    )
    (net (code "25") (name "ADCB6") (class "Default")
      (node (ref "U8") (pin "26") (pinfunction "ADCINB6/AIO14_26") (pintype "bidirectional"))
    )
    (net (code "26") (name "ADCIN14") (class "Default")
      (node (ref "J105") (pin "P$1") (pinfunction "P$1_P$1") (pintype "bidirectional"))
      (node (ref "J105") (pin "P$2") (pinfunction "P$2_P$2") (pintype "bidirectional"))
      (node (ref "J105") (pin "P$3") (pinfunction "P$3_P$3") (pintype "bidirectional"))
      (node (ref "L1") (pin "P$23") (pinfunction "ADCIN14_P$23") (pintype "bidirectional"))
    )
    (net (code "27") (name "ADCIN15") (class "Default")
      (node (ref "J150") (pin "P$1") (pinfunction "P$1_P$1") (pintype "bidirectional"))
      (node (ref "J150") (pin "P$2") (pinfunction "P$2_P$2") (pintype "bidirectional"))
      (node (ref "J150") (pin "P$3") (pinfunction "P$3_P$3") (pintype "bidirectional"))
      (node (ref "L1") (pin "P$63") (pinfunction "ADCIN15_P$63") (pintype "bidirectional"))
    )
    (net (code "28") (name "ADCINA2") (class "Default")
      (node (ref "J111") (pin "P$1") (pinfunction "P$1_P$1") (pintype "bidirectional"))
      (node (ref "J111") (pin "P$2") (pinfunction "P$2_P$2") (pintype "bidirectional"))
      (node (ref "J111") (pin "P$3") (pinfunction "P$3_P$3") (pintype "bidirectional"))
      (node (ref "L1") (pin "P$29") (pinfunction "ADCINA2_P$29") (pintype "bidirectional"))
      (node (ref "SV11") (pin "3") (pinfunction "3_3") (pintype "passive"))
    )
    (net (code "29") (name "ADCINA3") (class "Default")
      (node (ref "J108") (pin "P$1") (pinfunction "P$1_P$1") (pintype "bidirectional"))
      (node (ref "J108") (pin "P$2") (pinfunction "P$2_P$2") (pintype "bidirectional"))
      (node (ref "J108") (pin "P$3") (pinfunction "P$3_P$3") (pintype "bidirectional"))
      (node (ref "L1") (pin "P$26") (pinfunction "ADCINA3_P$26") (pintype "bidirectional"))
      (node (ref "SV11") (pin "4") (pinfunction "4_4") (pintype "passive"))
    )
    (net (code "30") (name "ADCINA4") (class "Default")
      (node (ref "J144") (pin "P$1") (pinfunction "P$1_P$1") (pintype "bidirectional"))
      (node (ref "J144") (pin "P$2") (pinfunction "P$2_P$2") (pintype "bidirectional"))
      (node (ref "J144") (pin "P$3") (pinfunction "P$3_P$3") (pintype "bidirectional"))
      (node (ref "L1") (pin "P$69") (pinfunction "ADCINA4_P$69") (pintype "bidirectional"))
    )
    (net (code "31") (name "ADCINA5") (class "Default")
      (node (ref "J147") (pin "P$1") (pinfunction "P$1_P$1") (pintype "bidirectional"))
      (node (ref "J147") (pin "P$2") (pinfunction "P$2_P$2") (pintype "bidirectional"))
      (node (ref "J147") (pin "P$3") (pinfunction "P$3_P$3") (pintype "bidirectional"))
      (node (ref "L1") (pin "P$66") (pinfunction "ADCINA5_P$66") (pintype "bidirectional"))
    )
    (net (code "32") (name "ADCINB2") (class "Default")
      (node (ref "J110") (pin "P$1") (pinfunction "P$1_P$1") (pintype "bidirectional"))
      (node (ref "J110") (pin "P$2") (pinfunction "P$2_P$2") (pintype "bidirectional"))
      (node (ref "J110") (pin "P$3") (pinfunction "P$3_P$3") (pintype "bidirectional"))
      (node (ref "L1") (pin "P$28") (pinfunction "ADCINB2_P$28") (pintype "bidirectional"))
    )
    (net (code "33") (name "ADCINB3") (class "Default")
      (node (ref "J107") (pin "P$1") (pinfunction "P$1_P$1") (pintype "bidirectional"))
      (node (ref "J107") (pin "P$2") (pinfunction "P$2_P$2") (pintype "bidirectional"))
      (node (ref "J107") (pin "P$3") (pinfunction "P$3_P$3") (pintype "bidirectional"))
      (node (ref "L1") (pin "P$25") (pinfunction "ADCINB3_P$25") (pintype "bidirectional"))
    )
    (net (code "34") (name "ADCINB4") (class "Default")
      (node (ref "J145") (pin "P$1") (pinfunction "P$1_P$1") (pintype "bidirectional"))
      (node (ref "J145") (pin "P$2") (pinfunction "P$2_P$2") (pintype "bidirectional"))
      (node (ref "J145") (pin "P$3") (pinfunction "P$3_P$3") (pintype "bidirectional"))
      (node (ref "L1") (pin "P$68") (pinfunction "ADCINB4_P$68") (pintype "bidirectional"))
      (node (ref "SV12") (pin "4") (pinfunction "4_4") (pintype "passive"))
    )
    (net (code "35") (name "ADCINB5") (class "Default")
      (node (ref "J148") (pin "P$1") (pinfunction "P$1_P$1") (pintype "bidirectional"))
      (node (ref "J148") (pin "P$2") (pinfunction "P$2_P$2") (pintype "bidirectional"))
      (node (ref "J148") (pin "P$3") (pinfunction "P$3_P$3") (pintype "bidirectional"))
      (node (ref "L1") (pin "P$65") (pinfunction "ADCINB5_P$65") (pintype "bidirectional"))
    )
    (net (code "36") (name "ADCINC2") (class "Default")
      (node (ref "J109") (pin "P$1") (pinfunction "P$1_P$1") (pintype "bidirectional"))
      (node (ref "J109") (pin "P$2") (pinfunction "P$2_P$2") (pintype "bidirectional"))
      (node (ref "J109") (pin "P$3") (pinfunction "P$3_P$3") (pintype "bidirectional"))
      (node (ref "L1") (pin "P$27") (pinfunction "ADCINC2_P$27") (pintype "bidirectional"))
    )
    (net (code "37") (name "ADCINC3") (class "Default")
      (node (ref "J106") (pin "P$1") (pinfunction "P$1_P$1") (pintype "bidirectional"))
      (node (ref "J106") (pin "P$2") (pinfunction "P$2_P$2") (pintype "bidirectional"))
      (node (ref "J106") (pin "P$3") (pinfunction "P$3_P$3") (pintype "bidirectional"))
      (node (ref "L1") (pin "P$24") (pinfunction "ADCINC3_P$24") (pintype "bidirectional"))
    )
    (net (code "38") (name "ADCINC4") (class "Default")
      (node (ref "J146") (pin "P$1") (pinfunction "P$1_P$1") (pintype "bidirectional"))
      (node (ref "J146") (pin "P$2") (pinfunction "P$2_P$2") (pintype "bidirectional"))
      (node (ref "J146") (pin "P$3") (pinfunction "P$3_P$3") (pintype "bidirectional"))
      (node (ref "L1") (pin "P$67") (pinfunction "ADCINC4_P$67") (pintype "bidirectional"))
    )
    (net (code "39") (name "ADCINC5") (class "Default")
      (node (ref "J149") (pin "P$1") (pinfunction "P$1_P$1") (pintype "bidirectional"))
      (node (ref "J149") (pin "P$2") (pinfunction "P$2_P$2") (pintype "bidirectional"))
      (node (ref "J149") (pin "P$3") (pinfunction "P$3_P$3") (pintype "bidirectional"))
      (node (ref "L1") (pin "P$64") (pinfunction "ADCINC5_P$64") (pintype "bidirectional"))
    )
    (net (code "40") (name "DACOUTA") (class "Default")
      (node (ref "J112") (pin "P$1") (pinfunction "P$1_P$1") (pintype "bidirectional"))
      (node (ref "J112") (pin "P$2") (pinfunction "P$2_P$2") (pintype "bidirectional"))
      (node (ref "J112") (pin "P$3") (pinfunction "P$3_P$3") (pintype "bidirectional"))
      (node (ref "L1") (pin "P$30") (pinfunction "ADCINA0/DACOUTA_P$30") (pintype "bidirectional"))
    )
    (net (code "41") (name "DACOUTB") (class "Default")
      (node (ref "J143") (pin "P$1") (pinfunction "P$1_P$1") (pintype "bidirectional"))
      (node (ref "J143") (pin "P$2") (pinfunction "P$2_P$2") (pintype "bidirectional"))
      (node (ref "J143") (pin "P$3") (pinfunction "P$3_P$3") (pintype "bidirectional"))
      (node (ref "L1") (pin "P$70") (pinfunction "ADCINA1/DACOUTB_P$70") (pintype "bidirectional"))
    )
    (net (code "42") (name "DRV1_DIR") (class "Default")
      (node (ref "J80") (pin "P$1") (pinfunction "P$1_P$1") (pintype "bidirectional"))
      (node (ref "J80") (pin "P$2") (pinfunction "P$2_P$2") (pintype "bidirectional"))
      (node (ref "U2") (pin "P$2") (pinfunction "PH/IN2_P$2") (pintype "bidirectional"))
    )
    (net (code "43") (name "DRV1_M+") (class "Default")
      (node (ref "SV7") (pin "1") (pinfunction "1_1") (pintype "passive"))
      (node (ref "SV7") (pin "3") (pinfunction "3_3") (pintype "passive"))
      (node (ref "SV7") (pin "5") (pinfunction "5_5") (pintype "passive"))
      (node (ref "U2") (pin "P$8") (pinfunction "OUT1_P$8") (pintype "bidirectional"))
    )
    (net (code "44") (name "DRV1_M-") (class "Default")
      (node (ref "SV7") (pin "2") (pinfunction "2_2") (pintype "passive"))
      (node (ref "SV7") (pin "4") (pinfunction "4_4") (pintype "passive"))
      (node (ref "SV7") (pin "6") (pinfunction "6_6") (pintype "passive"))
      (node (ref "U2") (pin "P$10") (pinfunction "OUT2_P$10") (pintype "bidirectional"))
    )
    (net (code "45") (name "DRV1_PWM") (class "Default")
      (node (ref "J79") (pin "P$1") (pinfunction "P$1_P$1") (pintype "bidirectional"))
      (node (ref "J79") (pin "P$2") (pinfunction "P$2_P$2") (pintype "bidirectional"))
      (node (ref "U2") (pin "P$1") (pinfunction "EN/IN1_P$1") (pintype "bidirectional"))
    )
    (net (code "46") (name "DRV2_DIR") (class "Default")
      (node (ref "J83") (pin "P$1") (pinfunction "P$1_P$1") (pintype "bidirectional"))
      (node (ref "J83") (pin "P$2") (pinfunction "P$2_P$2") (pintype "bidirectional"))
      (node (ref "U4") (pin "P$2") (pinfunction "PH/IN2_P$2") (pintype "bidirectional"))
    )
    (net (code "47") (name "DRV2_M+") (class "Default")
      (node (ref "SV8") (pin "1") (pinfunction "1_1") (pintype "passive"))
      (node (ref "SV8") (pin "3") (pinfunction "3_3") (pintype "passive"))
      (node (ref "SV8") (pin "5") (pinfunction "5_5") (pintype "passive"))
      (node (ref "U4") (pin "P$8") (pinfunction "OUT1_P$8") (pintype "bidirectional"))
    )
    (net (code "48") (name "DRV2_M-") (class "Default")
      (node (ref "SV8") (pin "2") (pinfunction "2_2") (pintype "passive"))
      (node (ref "SV8") (pin "4") (pinfunction "4_4") (pintype "passive"))
      (node (ref "SV8") (pin "6") (pinfunction "6_6") (pintype "passive"))
      (node (ref "U4") (pin "P$10") (pinfunction "OUT2_P$10") (pintype "bidirectional"))
    )
    (net (code "49") (name "DRV2_PWM") (class "Default")
      (node (ref "J82") (pin "P$1") (pinfunction "P$1_P$1") (pintype "bidirectional"))
      (node (ref "J82") (pin "P$2") (pinfunction "P$2_P$2") (pintype "bidirectional"))
      (node (ref "U4") (pin "P$1") (pinfunction "EN/IN1_P$1") (pintype "bidirectional"))
    )
    (net (code "50") (name "GND") (class "Default")
      (node (ref "3V3") (pin "C") (pinfunction "C_C") (pintype "passive"))
      (node (ref "5V") (pin "C") (pinfunction "C_C") (pintype "passive"))
      (node (ref "B1") (pin "P$2") (pinfunction "P$2_P$2") (pintype "bidirectional"))
      (node (ref "B2") (pin "P$2") (pinfunction "BAT-_P$2") (pintype "bidirectional"))
      (node (ref "B3") (pin "P$1") (pinfunction "P1_P$1") (pintype "bidirectional"))
      (node (ref "C1") (pin "-") (pinfunction "-_-") (pintype "passive"))
      (node (ref "C10") (pin "2") (pinfunction "2_2") (pintype "passive"))
      (node (ref "C11") (pin "2") (pinfunction "2_2") (pintype "passive"))
      (node (ref "C12") (pin "-") (pinfunction "-_-") (pintype "passive"))
      (node (ref "C13") (pin "-") (pinfunction "-_-") (pintype "passive"))
      (node (ref "C14") (pin "2") (pinfunction "2_2") (pintype "passive"))
      (node (ref "C15") (pin "-") (pinfunction "-_-") (pintype "passive"))
      (node (ref "C16") (pin "2") (pinfunction "2_2") (pintype "passive"))
      (node (ref "C18") (pin "2") (pinfunction "2_2") (pintype "passive"))
      (node (ref "C2") (pin "2") (pinfunction "2_2") (pintype "passive"))
      (node (ref "C20") (pin "-") (pinfunction "-_-") (pintype "passive"))
      (node (ref "C21") (pin "2") (pinfunction "2_2") (pintype "passive"))
      (node (ref "C22") (pin "2") (pinfunction "2_2") (pintype "passive"))
      (node (ref "C25") (pin "-") (pinfunction "-_-") (pintype "passive"))
      (node (ref "C27") (pin "-") (pinfunction "-_-") (pintype "passive"))
      (node (ref "C28") (pin "-") (pinfunction "-_-") (pintype "passive"))
      (node (ref "C3") (pin "2") (pinfunction "2_2") (pintype "passive"))
      (node (ref "C4") (pin "2") (pinfunction "2_2") (pintype "passive"))
      (node (ref "C5") (pin "2") (pinfunction "2_2") (pintype "passive"))
      (node (ref "C6") (pin "2") (pinfunction "2_2") (pintype "passive"))
      (node (ref "C7") (pin "2") (pinfunction "2_2") (pintype "passive"))
      (node (ref "C8") (pin "2") (pinfunction "2_2") (pintype "passive"))
      (node (ref "C9") (pin "2") (pinfunction "2_2") (pintype "passive"))
      (node (ref "DCDC3.3V") (pin "2") (pinfunction "2_2") (pintype "passive"))
      (node (ref "DCDC5V") (pin "2") (pinfunction "2_2") (pintype "passive"))
      (node (ref "ETH1") (pin "P$1") (pinfunction "GND_1_P$1") (pintype "bidirectional"))
      (node (ref "ETH1") (pin "P$12") (pinfunction "GND_3_P$12") (pintype "bidirectional"))
      (node (ref "ETH1") (pin "P$2") (pinfunction "GND_2_P$2") (pintype "bidirectional"))
      (node (ref "G1") (pin "-") (pinfunction "-_-") (pintype "passive"))
      (node (ref "IC1") (pin "7") (pinfunction "GND_7") (pintype "power_in"))
      (node (ref "IC2") (pin "7") (pinfunction "GND_7") (pintype "power_in"))
      (node (ref "IC3") (pin "7") (pinfunction "GND_7") (pintype "power_in"))
      (node (ref "J102") (pin "P$1") (pinfunction "P$1_P$1") (pintype "bidirectional"))
      (node (ref "J102") (pin "P$2") (pinfunction "P$2_P$2") (pintype "bidirectional"))
      (node (ref "J102") (pin "P$3") (pinfunction "P$3_P$3") (pintype "bidirectional"))
      (node (ref "J104") (pin "P$1") (pinfunction "P$1_P$1") (pintype "bidirectional"))
      (node (ref "J104") (pin "P$2") (pinfunction "P$2_P$2") (pintype "bidirectional"))
      (node (ref "J104") (pin "P$3") (pinfunction "P$3_P$3") (pintype "bidirectional"))
      (node (ref "J124") (pin "P$1") (pinfunction "P$1_P$1") (pintype "bidirectional"))
      (node (ref "J124") (pin "P$2") (pinfunction "P$2_P$2") (pintype "bidirectional"))
      (node (ref "J124") (pin "P$3") (pinfunction "P$3_P$3") (pintype "bidirectional"))
      (node (ref "J151") (pin "P$1") (pinfunction "P$1_P$1") (pintype "bidirectional"))
      (node (ref "J151") (pin "P$2") (pinfunction "P$2_P$2") (pintype "bidirectional"))
      (node (ref "J151") (pin "P$3") (pinfunction "P$3_P$3") (pintype "bidirectional"))
      (node (ref "J153") (pin "P$1") (pinfunction "P$1_P$1") (pintype "bidirectional"))
      (node (ref "J153") (pin "P$2") (pinfunction "P$2_P$2") (pintype "bidirectional"))
      (node (ref "J153") (pin "P$3") (pinfunction "P$3_P$3") (pintype "bidirectional"))
      (node (ref "J43") (pin "P$1") (pinfunction "P$1_P$1") (pintype "bidirectional"))
      (node (ref "J5") (pin "2") (pinfunction "2_2") (pintype "passive"))
      (node (ref "J5") (pin "3") (pinfunction "3_3") (pintype "passive"))
      (node (ref "J7") (pin "P$1") (pinfunction "P$1_P$1") (pintype "bidirectional"))
      (node (ref "J7") (pin "P$2") (pinfunction "P$2_P$2") (pintype "bidirectional"))
      (node (ref "JP2") (pin "2") (pinfunction "2_2") (pintype "passive"))
      (node (ref "JP3") (pin "2") (pinfunction "2_2") (pintype "passive"))
      (node (ref "L1") (pin "P$20") (pinfunction "GND_1_P$20") (pintype "bidirectional"))
      (node (ref "L1") (pin "P$22") (pinfunction "GND_2_P$22") (pintype "bidirectional"))
      (node (ref "L1") (pin "P$60") (pinfunction "GND_3_P$60") (pintype "bidirectional"))
      (node (ref "L1") (pin "P$62") (pinfunction "GND_4_P$62") (pintype "bidirectional"))
      (node (ref "LED18") (pin "C") (pinfunction "C_C") (pintype "passive"))
      (node (ref "P1") (pin "2") (pinfunction "2_2") (pintype "bidirectional"))
      (node (ref "P2") (pin "2") (pinfunction "2_2") (pintype "bidirectional"))
      (node (ref "POWER") (pin "1") (pinfunction "1_1") (pintype "passive"))
      (node (ref "R3") (pin "1") (pinfunction "1_1") (pintype "passive"))
      (node (ref "R32") (pin "2") (pinfunction "2_2") (pintype "passive"))
      (node (ref "R41") (pin "2") (pinfunction "2_2") (pintype "passive"))
      (node (ref "R43") (pin "2") (pinfunction "2_2") (pintype "passive"))
      (node (ref "R7") (pin "1") (pinfunction "1_1") (pintype "passive"))
      (node (ref "S1") (pin "P$1") (pinfunction "P1_P$1") (pintype "bidirectional"))
      (node (ref "S129") (pin "P$1") (pinfunction "P$1_P$1") (pintype "bidirectional"))
      (node (ref "S129") (pin "P$2") (pinfunction "P$2_P$2") (pintype "bidirectional"))
      (node (ref "S129") (pin "P$3") (pinfunction "P$3_P$3") (pintype "bidirectional"))
      (node (ref "S129") (pin "P$4") (pinfunction "P$4_P$4") (pintype "bidirectional"))
      (node (ref "S129") (pin "P$5") (pinfunction "P$5_P$5") (pintype "bidirectional"))
      (node (ref "S137") (pin "P$1") (pinfunction "P$1_P$1") (pintype "bidirectional"))
      (node (ref "S137") (pin "P$2") (pinfunction "P$2_P$2") (pintype "bidirectional"))
      (node (ref "S137") (pin "P$3") (pinfunction "P$3_P$3") (pintype "bidirectional"))
      (node (ref "S137") (pin "P$4") (pinfunction "P$4_P$4") (pintype "bidirectional"))
      (node (ref "S137") (pin "P$5") (pinfunction "P$5_P$5") (pintype "bidirectional"))
      (node (ref "S159") (pin "P$1") (pinfunction "P1_P$1") (pintype "bidirectional"))
      (node (ref "S20") (pin "P$1") (pinfunction "P$1_P$1") (pintype "bidirectional"))
      (node (ref "S20") (pin "P$10") (pinfunction "P$10_P$10") (pintype "bidirectional"))
      (node (ref "S20") (pin "P$2") (pinfunction "P$2_P$2") (pintype "bidirectional"))
      (node (ref "S20") (pin "P$3") (pinfunction "P$3_P$3") (pintype "bidirectional"))
      (node (ref "S20") (pin "P$4") (pinfunction "P$4_P$4") (pintype "bidirectional"))
      (node (ref "S20") (pin "P$5") (pinfunction "P$5_P$5") (pintype "bidirectional"))
      (node (ref "S20") (pin "P$6") (pinfunction "P$6_P$6") (pintype "bidirectional"))
      (node (ref "S20") (pin "P$7") (pinfunction "P$7_P$7") (pintype "bidirectional"))
      (node (ref "S20") (pin "P$8") (pinfunction "P$8_P$8") (pintype "bidirectional"))
      (node (ref "S20") (pin "P$9") (pinfunction "P$9_P$9") (pintype "bidirectional"))
      (node (ref "S24") (pin "P$1") (pinfunction "P$1_P$1") (pintype "bidirectional"))
      (node (ref "S24") (pin "P$10") (pinfunction "P$10_P$10") (pintype "bidirectional"))
      (node (ref "S24") (pin "P$2") (pinfunction "P$2_P$2") (pintype "bidirectional"))
      (node (ref "S24") (pin "P$3") (pinfunction "P$3_P$3") (pintype "bidirectional"))
      (node (ref "S24") (pin "P$4") (pinfunction "P$4_P$4") (pintype "bidirectional"))
      (node (ref "S24") (pin "P$5") (pinfunction "P$5_P$5") (pintype "bidirectional"))
      (node (ref "S24") (pin "P$6") (pinfunction "P$6_P$6") (pintype "bidirectional"))
      (node (ref "S24") (pin "P$7") (pinfunction "P$7_P$7") (pintype "bidirectional"))
      (node (ref "S24") (pin "P$8") (pinfunction "P$8_P$8") (pintype "bidirectional"))
      (node (ref "S24") (pin "P$9") (pinfunction "P$9_P$9") (pintype "bidirectional"))
      (node (ref "SV11") (pin "1") (pinfunction "1_1") (pintype "passive"))
      (node (ref "SV12") (pin "1") (pinfunction "1_1") (pintype "passive"))
      (node (ref "SV13") (pin "2") (pinfunction "2_2") (pintype "passive"))
      (node (ref "SV14") (pin "10") (pinfunction "10_10") (pintype "passive"))
      (node (ref "SV14") (pin "12") (pinfunction "12_12") (pintype "passive"))
      (node (ref "SV14") (pin "4") (pinfunction "4_4") (pintype "passive"))
      (node (ref "SV14") (pin "8") (pinfunction "8_8") (pintype "passive"))
      (node (ref "SV15") (pin "1") (pinfunction "1_1") (pintype "passive"))
      (node (ref "SV17") (pin "1") (pinfunction "1_1") (pintype "passive"))
      (node (ref "SV17") (pin "2") (pinfunction "2_2") (pintype "passive"))
      (node (ref "SV19") (pin "1") (pinfunction "1_1") (pintype "passive"))
      (node (ref "SV2") (pin "13") (pinfunction "13_13") (pintype "passive"))
      (node (ref "SV2") (pin "14") (pinfunction "14_14") (pintype "passive"))
      (node (ref "SV2") (pin "19") (pinfunction "19_19") (pintype "passive"))
      (node (ref "SV2") (pin "20") (pinfunction "20_20") (pintype "passive"))
      (node (ref "SV2") (pin "29") (pinfunction "29_29") (pintype "passive"))
      (node (ref "SV2") (pin "30") (pinfunction "30_30") (pintype "passive"))
      (node (ref "SV2") (pin "33") (pinfunction "33_33") (pintype "passive"))
      (node (ref "SV2") (pin "34") (pinfunction "34_34") (pintype "passive"))
      (node (ref "SV2") (pin "5") (pinfunction "5_5") (pintype "passive"))
      (node (ref "SV2") (pin "6") (pinfunction "6_6") (pintype "passive"))
      (node (ref "SV4") (pin "10") (pinfunction "10_10") (pintype "passive"))
      (node (ref "SV4") (pin "25") (pinfunction "25_25") (pintype "passive"))
      (node (ref "SV4") (pin "26") (pinfunction "26_26") (pintype "passive"))
      (node (ref "SV4") (pin "39") (pinfunction "39_39") (pintype "passive"))
      (node (ref "SV4") (pin "40") (pinfunction "40_40") (pintype "passive"))
      (node (ref "SV4") (pin "9") (pinfunction "9_9") (pintype "passive"))
      (node (ref "SV6") (pin "3") (pinfunction "3_3") (pintype "passive"))
      (node (ref "SV6") (pin "4") (pinfunction "4_4") (pintype "passive"))
      (node (ref "T1") (pin "3") (pinfunction "E_3") (pintype "passive"))
      (node (ref "T2") (pin "3") (pinfunction "E_3") (pintype "passive"))
      (node (ref "TRIMPOT1") (pin "5") (pinfunction "5_5") (pintype "passive"))
      (node (ref "TRIMPOT1") (pin "6") (pinfunction "6_6") (pintype "passive"))
      (node (ref "TRIMPOT2") (pin "5") (pinfunction "5_5") (pintype "passive"))
      (node (ref "TRIMPOT2") (pin "6") (pinfunction "6_6") (pintype "passive"))
      (node (ref "U$1") (pin "2") (pinfunction "P2_GND_2") (pintype "bidirectional"))
      (node (ref "U$6") (pin "P$1") (pinfunction "P$1_P$1") (pintype "bidirectional"))
      (node (ref "U$6") (pin "P$2") (pinfunction "P$2_P$2") (pintype "bidirectional"))
      (node (ref "U$7") (pin "P$1") (pinfunction "P$1_P$1") (pintype "bidirectional"))
      (node (ref "U$7") (pin "P$2") (pinfunction "P$2_P$2") (pintype "bidirectional"))
      (node (ref "U$8") (pin "P$1") (pinfunction "P$1_P$1") (pintype "bidirectional"))
      (node (ref "U$8") (pin "P$2") (pinfunction "P$2_P$2") (pintype "bidirectional"))
      (node (ref "U$9") (pin "P$1") (pinfunction "P$1_P$1") (pintype "bidirectional"))
      (node (ref "U$9") (pin "P$2") (pinfunction "P$2_P$2") (pintype "bidirectional"))
      (node (ref "U1") (pin "11") (pinfunction "SENSE_11") (pintype "bidirectional"))
      (node (ref "U1") (pin "12") (pinfunction "GND_12") (pintype "bidirectional"))
      (node (ref "U1") (pin "13") (pinfunction "GND_13") (pintype "bidirectional"))
      (node (ref "U1") (pin "4") (pinfunction "GND_4") (pintype "bidirectional"))
      (node (ref "U1") (pin "5") (pinfunction "GND_5") (pintype "bidirectional"))
      (node (ref "U2") (pin "P$15") (pinfunction "GND_P$15") (pintype "bidirectional"))
      (node (ref "U2") (pin "P$16") (pinfunction "PMODE_P$16") (pintype "bidirectional"))
      (node (ref "U2") (pin "P$17") (pinfunction "GND_PAD_P$17") (pintype "bidirectional"))
      (node (ref "U2") (pin "P$7") (pinfunction "IMODE_P$7") (pintype "bidirectional"))
      (node (ref "U2") (pin "P$9") (pinfunction "PGND_P$9") (pintype "bidirectional"))
      (node (ref "U3") (pin "4") (pinfunction "P4_GND_4") (pintype "bidirectional"))
      (node (ref "U4") (pin "P$15") (pinfunction "GND_P$15") (pintype "bidirectional"))
      (node (ref "U4") (pin "P$16") (pinfunction "PMODE_P$16") (pintype "bidirectional"))
      (node (ref "U4") (pin "P$17") (pinfunction "GND_PAD_P$17") (pintype "bidirectional"))
      (node (ref "U4") (pin "P$7") (pinfunction "IMODE_P$7") (pintype "bidirectional"))
      (node (ref "U4") (pin "P$9") (pinfunction "PGND_P$9") (pintype "bidirectional"))
      (node (ref "U5") (pin "11") (pinfunction "SENSE_11") (pintype "bidirectional"))
      (node (ref "U5") (pin "12") (pinfunction "GND_12") (pintype "bidirectional"))
      (node (ref "U5") (pin "13") (pinfunction "GND_13") (pintype "bidirectional"))
      (node (ref "U5") (pin "4") (pinfunction "GND_4") (pintype "bidirectional"))
      (node (ref "U5") (pin "5") (pinfunction "GND_5") (pintype "bidirectional"))
      (node (ref "U6") (pin "P$4") (pinfunction "V-_P$4") (pintype "bidirectional"))
      (node (ref "U7") (pin "4") (pinfunction "GND_4") (pintype "bidirectional"))
      (node (ref "U8") (pin "12") (pinfunction "VSS2_12") (pintype "bidirectional"))
      (node (ref "U8") (pin "2") (pinfunction "VSS_2") (pintype "bidirectional"))
      (node (ref "U8") (pin "23") (pinfunction "VSSA/VREFLO_23") (pintype "bidirectional"))
      (node (ref "U8") (pin "3") (pinfunction "/VREGENZ_3") (pintype "bidirectional"))
    )
    (net (code "51") (name "GPIO0") (class "Default")
      (node (ref "J11") (pin "P$1") (pinfunction "P$1_P$1") (pintype "bidirectional"))
      (node (ref "J11") (pin "P$2") (pinfunction "P$2_P$2") (pintype "bidirectional"))
      (node (ref "J122") (pin "P$1") (pinfunction "P$1_P$1") (pintype "bidirectional"))
      (node (ref "J122") (pin "P$2") (pinfunction "P$2_P$2") (pintype "bidirectional"))
      (node (ref "J122") (pin "P$3") (pinfunction "P$3_P$3") (pintype "bidirectional"))
      (node (ref "L1") (pin "P$40") (pinfunction "GPIO0/EPWM1A_P$40") (pintype "bidirectional"))
    )
    (net (code "52") (name "GPIO1") (class "Default")
      (node (ref "J121") (pin "P$1") (pinfunction "P$1_P$1") (pintype "bidirectional"))
      (node (ref "J121") (pin "P$2") (pinfunction "P$2_P$2") (pintype "bidirectional"))
      (node (ref "J121") (pin "P$3") (pinfunction "P$3_P$3") (pintype "bidirectional"))
      (node (ref "L1") (pin "P$39") (pinfunction "GPIO1/EPWM1B_P$39") (pintype "bidirectional"))
      (node (ref "SV13") (pin "5") (pinfunction "5_5") (pintype "passive"))
    )
    (net (code "53") (name "GPIO2") (class "Default")
      (node (ref "J120") (pin "P$1") (pinfunction "P$1_P$1") (pintype "bidirectional"))
      (node (ref "J120") (pin "P$2") (pinfunction "P$2_P$2") (pintype "bidirectional"))
      (node (ref "J120") (pin "P$3") (pinfunction "P$3_P$3") (pintype "bidirectional"))
      (node (ref "J198") (pin "P$1") (pinfunction "P$1_P$1") (pintype "bidirectional"))
      (node (ref "J198") (pin "P$2") (pinfunction "P$2_P$2") (pintype "bidirectional"))
      (node (ref "L1") (pin "P$38") (pinfunction "GPIO2/EPWM2A_P$38") (pintype "bidirectional"))
    )
    (net (code "54") (name "GPIO3") (class "Default")
      (node (ref "J119") (pin "P$1") (pinfunction "P$1_P$1") (pintype "bidirectional"))
      (node (ref "J119") (pin "P$2") (pinfunction "P$2_P$2") (pintype "bidirectional"))
      (node (ref "J119") (pin "P$3") (pinfunction "P$3_P$3") (pintype "bidirectional"))
      (node (ref "J199") (pin "P$1") (pinfunction "P$1_P$1") (pintype "bidirectional"))
      (node (ref "J199") (pin "P$2") (pinfunction "P$2_P$2") (pintype "bidirectional"))
      (node (ref "L1") (pin "P$37") (pinfunction "GPIO3/EPWM2B_P$37") (pintype "bidirectional"))
    )
    (net (code "55") (name "GPIO4") (class "Default")
      (node (ref "J118") (pin "P$1") (pinfunction "P$1_P$1") (pintype "bidirectional"))
      (node (ref "J118") (pin "P$2") (pinfunction "P$2_P$2") (pintype "bidirectional"))
      (node (ref "J118") (pin "P$3") (pinfunction "P$3_P$3") (pintype "bidirectional"))
      (node (ref "L1") (pin "P$36") (pinfunction "GPIO4/EPWM3A_P$36") (pintype "bidirectional"))
      (node (ref "U$5") (pin "P$1") (pinfunction "P$1_P$1") (pintype "bidirectional"))
      (node (ref "U$5") (pin "P$2") (pinfunction "P$2_P$2") (pintype "bidirectional"))
    )
    (net (code "56") (name "GPIO5") (class "Default")
      (node (ref "J117") (pin "P$1") (pinfunction "P$1_P$1") (pintype "bidirectional"))
      (node (ref "J117") (pin "P$2") (pinfunction "P$2_P$2") (pintype "bidirectional"))
      (node (ref "J117") (pin "P$3") (pinfunction "P$3_P$3") (pintype "bidirectional"))
      (node (ref "L1") (pin "P$35") (pinfunction "GPIO5/EPWM3B_P$35") (pintype "bidirectional"))
      (node (ref "U$10") (pin "P$1") (pinfunction "P$1_P$1") (pintype "bidirectional"))
      (node (ref "U$10") (pin "P$2") (pinfunction "P$2_P$2") (pintype "bidirectional"))
    )
    (net (code "57") (name "GPIO6") (class "Default")
      (node (ref "J133") (pin "P$1") (pinfunction "P$1_P$1") (pintype "bidirectional"))
      (node (ref "J133") (pin "P$2") (pinfunction "P$2_P$2") (pintype "bidirectional"))
      (node (ref "J133") (pin "P$3") (pinfunction "P$3_P$3") (pintype "bidirectional"))
      (node (ref "L1") (pin "P$80") (pinfunction "GPIO6/EPWM4A_P$80") (pintype "bidirectional"))
      (node (ref "U$11") (pin "P$1") (pinfunction "P$1_P$1") (pintype "bidirectional"))
      (node (ref "U$11") (pin "P$2") (pinfunction "P$2_P$2") (pintype "bidirectional"))
    )
    (net (code "58") (name "GPIO7") (class "Default")
      (node (ref "J134") (pin "P$1") (pinfunction "P$1_P$1") (pintype "bidirectional"))
      (node (ref "J134") (pin "P$2") (pinfunction "P$2_P$2") (pintype "bidirectional"))
      (node (ref "J134") (pin "P$3") (pinfunction "P$3_P$3") (pintype "bidirectional"))
      (node (ref "L1") (pin "P$79") (pinfunction "GPIO7/EPWM4B_P$79") (pintype "bidirectional"))
      (node (ref "U$12") (pin "P$1") (pinfunction "P$1_P$1") (pintype "bidirectional"))
      (node (ref "U$12") (pin "P$2") (pinfunction "P$2_P$2") (pintype "bidirectional"))
    )
    (net (code "59") (name "GPIO8") (class "Default")
      (node (ref "J135") (pin "P$1") (pinfunction "P$1_P$1") (pintype "bidirectional"))
      (node (ref "J135") (pin "P$2") (pinfunction "P$2_P$2") (pintype "bidirectional"))
      (node (ref "J135") (pin "P$3") (pinfunction "P$3_P$3") (pintype "bidirectional"))
      (node (ref "L1") (pin "P$78") (pinfunction "GPIO8/EPWM5A_P$78") (pintype "bidirectional"))
      (node (ref "SV11") (pin "5") (pinfunction "5_5") (pintype "passive"))
    )
    (net (code "60") (name "GPIO9") (class "Default")
      (node (ref "J136") (pin "P$1") (pinfunction "P$1_P$1") (pintype "bidirectional"))
      (node (ref "J136") (pin "P$2") (pinfunction "P$2_P$2") (pintype "bidirectional"))
      (node (ref "J136") (pin "P$3") (pinfunction "P$3_P$3") (pintype "bidirectional"))
      (node (ref "J37") (pin "P$2") (pinfunction "P$2_P$2") (pintype "bidirectional"))
      (node (ref "L1") (pin "P$77") (pinfunction "GPIO9/EPWM5B_P$77") (pintype "bidirectional"))
    )
    (net (code "61") (name "GPIO10") (class "Default")
      (node (ref "J137") (pin "P$1") (pinfunction "P$1_P$1") (pintype "bidirectional"))
      (node (ref "J137") (pin "P$2") (pinfunction "P$2_P$2") (pintype "bidirectional"))
      (node (ref "J137") (pin "P$3") (pinfunction "P$3_P$3") (pintype "bidirectional"))
      (node (ref "J84") (pin "P$1") (pinfunction "P$1_P$1") (pintype "bidirectional"))
      (node (ref "J84") (pin "P$2") (pinfunction "P$2_P$2") (pintype "bidirectional"))
      (node (ref "L1") (pin "P$76") (pinfunction "GPIO10/EPWM6A_P$76") (pintype "bidirectional"))
    )
    (net (code "62") (name "GPIO11") (class "Default")
      (node (ref "J138") (pin "P$1") (pinfunction "P$1_P$1") (pintype "bidirectional"))
      (node (ref "J138") (pin "P$2") (pinfunction "P$2_P$2") (pintype "bidirectional"))
      (node (ref "J138") (pin "P$3") (pinfunction "P$3_P$3") (pintype "bidirectional"))
      (node (ref "J86") (pin "P$1") (pinfunction "P$1_P$1") (pintype "bidirectional"))
      (node (ref "J86") (pin "P$2") (pinfunction "P$2_P$2") (pintype "bidirectional"))
      (node (ref "L1") (pin "P$75") (pinfunction "GPIO11/EPWM6B_P$75") (pintype "bidirectional"))
    )
    (net (code "63") (name "GPIO14") (class "Default")
      (node (ref "J139") (pin "P$1") (pinfunction "P$1_P$1") (pintype "bidirectional"))
      (node (ref "J139") (pin "P$2") (pinfunction "P$2_P$2") (pintype "bidirectional"))
      (node (ref "J139") (pin "P$3") (pinfunction "P$3_P$3") (pintype "bidirectional"))
      (node (ref "J201") (pin "P$1") (pinfunction "P$1_P$1") (pintype "bidirectional"))
      (node (ref "J201") (pin "P$2") (pinfunction "P$2_P$2") (pintype "bidirectional"))
      (node (ref "L1") (pin "P$74") (pinfunction "GPIO14_P$74") (pintype "bidirectional"))
    )
    (net (code "64") (name "GPIO15") (class "Default")
      (node (ref "J140") (pin "P$1") (pinfunction "P$1_P$1") (pintype "bidirectional"))
      (node (ref "J140") (pin "P$2") (pinfunction "P$2_P$2") (pintype "bidirectional"))
      (node (ref "J140") (pin "P$3") (pinfunction "P$3_P$3") (pintype "bidirectional"))
      (node (ref "J202") (pin "P$1") (pinfunction "P$1_P$1") (pintype "bidirectional"))
      (node (ref "J202") (pin "P$2") (pinfunction "P$2_P$2") (pintype "bidirectional"))
      (node (ref "L1") (pin "P$73") (pinfunction "GPIO15_P$73") (pintype "bidirectional"))
    )
    (net (code "65") (name "GPIO16") (class "Default")
      (node (ref "J115") (pin "P$1") (pinfunction "P$1_P$1") (pintype "bidirectional"))
      (node (ref "J115") (pin "P$2") (pinfunction "P$2_P$2") (pintype "bidirectional"))
      (node (ref "J115") (pin "P$3") (pinfunction "P$3_P$3") (pintype "bidirectional"))
      (node (ref "J251") (pin "P$1") (pinfunction "P$1_P$1") (pintype "bidirectional"))
      (node (ref "J251") (pin "P$2") (pinfunction "P$2_P$2") (pintype "bidirectional"))
      (node (ref "L1") (pin "P$33") (pinfunction "GPIO16_P$33") (pintype "bidirectional"))
    )
    (net (code "66") (name "GPIO18") (class "Default")
      (node (ref "J16") (pin "P$1") (pinfunction "P$1_P$1") (pintype "bidirectional"))
      (node (ref "J16") (pin "P$2") (pinfunction "P$2_P$2") (pintype "bidirectional"))
      (node (ref "J16") (pin "P$3") (pinfunction "P$3_P$3") (pintype "bidirectional"))
      (node (ref "L1") (pin "P$4") (pinfunction "GPIO18/SCITXDB_P$4") (pintype "bidirectional"))
      (node (ref "U7") (pin "6") (pinfunction "SCK_6") (pintype "bidirectional"))
    )
    (net (code "67") (name "GPIO19") (class "Default")
      (node (ref "J15") (pin "P$1") (pinfunction "P$1_P$1") (pintype "bidirectional"))
      (node (ref "J15") (pin "P$2") (pinfunction "P$2_P$2") (pintype "bidirectional"))
      (node (ref "J15") (pin "P$3") (pinfunction "P$3_P$3") (pintype "bidirectional"))
      (node (ref "L1") (pin "P$3") (pinfunction "GPIO19/SCIRXDB_P$3") (pintype "bidirectional"))
      (node (ref "U7") (pin "1") (pinfunction "~{CS}_1") (pintype "bidirectional"))
    )
    (net (code "68") (name "GPIO22") (class "Default")
      (node (ref "IC1") (pin "1") (pinfunction "I_1") (pintype "input"))
      (node (ref "J20") (pin "P$1") (pinfunction "P$1_P$1") (pintype "bidirectional"))
      (node (ref "J20") (pin "P$2") (pinfunction "P$2_P$2") (pintype "bidirectional"))
      (node (ref "J20") (pin "P$3") (pinfunction "P$3_P$3") (pintype "bidirectional"))
      (node (ref "L1") (pin "P$8") (pinfunction "GPIO22_P$8") (pintype "bidirectional"))
    )
    (net (code "69") (name "GPIO24") (class "Default")
      (node (ref "J116") (pin "P$1") (pinfunction "P$1_P$1") (pintype "bidirectional"))
      (node (ref "J116") (pin "P$2") (pinfunction "P$2_P$2") (pintype "bidirectional"))
      (node (ref "J116") (pin "P$3") (pinfunction "P$3_P$3") (pintype "bidirectional"))
      (node (ref "J9") (pin "P$1") (pinfunction "P$1_P$1") (pintype "bidirectional"))
      (node (ref "J9") (pin "P$2") (pinfunction "P$2_P$2") (pintype "bidirectional"))
      (node (ref "L1") (pin "P$34") (pinfunction "GPIO24_P$34") (pintype "bidirectional"))
    )
    (net (code "70") (name "GPIO25") (class "Default")
      (node (ref "IC2") (pin "3") (pinfunction "I_3") (pintype "input"))
      (node (ref "J162") (pin "P$1") (pinfunction "P$1_P$1") (pintype "bidirectional"))
      (node (ref "J162") (pin "P$2") (pinfunction "P$2_P$2") (pintype "bidirectional"))
      (node (ref "J162") (pin "P$3") (pinfunction "P$3_P$3") (pintype "bidirectional"))
      (node (ref "L1") (pin "P$51") (pinfunction "GPIO25_P$51") (pintype "bidirectional"))
    )
    (net (code "71") (name "GPIO26") (class "Default")
      (node (ref "IC2") (pin "5") (pinfunction "I_5") (pintype "input"))
      (node (ref "J160") (pin "P$1") (pinfunction "P$1_P$1") (pintype "bidirectional"))
      (node (ref "J160") (pin "P$2") (pinfunction "P$2_P$2") (pintype "bidirectional"))
      (node (ref "J160") (pin "P$3") (pinfunction "P$3_P$3") (pintype "bidirectional"))
      (node (ref "L1") (pin "P$53") (pinfunction "GPIO26_P$53") (pintype "bidirectional"))
    )
    (net (code "72") (name "GPIO27") (class "Default")
      (node (ref "IC2") (pin "9") (pinfunction "I_9") (pintype "input"))
      (node (ref "J161") (pin "P$1") (pinfunction "P$1_P$1") (pintype "bidirectional"))
      (node (ref "J161") (pin "P$2") (pinfunction "P$2_P$2") (pintype "bidirectional"))
      (node (ref "J161") (pin "P$3") (pinfunction "P$3_P$3") (pintype "bidirectional"))
      (node (ref "L1") (pin "P$52") (pinfunction "GPIO27_P$52") (pintype "bidirectional"))
    )
    (net (code "73") (name "GPIO29") (class "Default")
      (node (ref "J29") (pin "P$1") (pinfunction "P$1_P$1") (pintype "bidirectional"))
      (node (ref "J29") (pin "P$2") (pinfunction "P$2_P$2") (pintype "bidirectional"))
      (node (ref "J29") (pin "P$3") (pinfunction "P$3_P$3") (pintype "bidirectional"))
      (node (ref "J85") (pin "P$1") (pinfunction "P$1_P$1") (pintype "bidirectional"))
      (node (ref "J85") (pin "P$2") (pinfunction "P$2_P$2") (pintype "bidirectional"))
      (node (ref "L1") (pin "P$11") (pinfunction "GPIO29_P$11") (pintype "bidirectional"))
    )
    (net (code "74") (name "GPIO32") (class "Default")
      (node (ref "J14") (pin "P$1") (pinfunction "P$1_P$1") (pintype "bidirectional"))
      (node (ref "J14") (pin "P$2") (pinfunction "P$2_P$2") (pintype "bidirectional"))
      (node (ref "J14") (pin "P$3") (pinfunction "P$3_P$3") (pintype "bidirectional"))
      (node (ref "J87") (pin "P$1") (pinfunction "P$1_P$1") (pintype "bidirectional"))
      (node (ref "J87") (pin "P$2") (pinfunction "P$2_P$2") (pintype "bidirectional"))
      (node (ref "L1") (pin "P$2") (pinfunction "GPIO32_P$2") (pintype "bidirectional"))
    )
    (net (code "75") (name "GPIO40") (class "Default")
      (node (ref "J163") (pin "P$1") (pinfunction "P$1_P$1") (pintype "bidirectional"))
      (node (ref "J163") (pin "P$2") (pinfunction "P$2_P$2") (pintype "bidirectional"))
      (node (ref "J163") (pin "P$3") (pinfunction "P$3_P$3") (pintype "bidirectional"))
      (node (ref "J208") (pin "P$1") (pinfunction "P$1_P$1") (pintype "bidirectional"))
      (node (ref "J208") (pin "P$2") (pinfunction "P$2_P$2") (pintype "bidirectional"))
      (node (ref "J42") (pin "P$1") (pinfunction "P$1_P$1") (pintype "bidirectional"))
      (node (ref "J42") (pin "P$2") (pinfunction "P$2_P$2") (pintype "bidirectional"))
      (node (ref "L1") (pin "P$50") (pinfunction "GPIO40/SDAB_P$50") (pintype "bidirectional"))
      (node (ref "R9") (pin "2") (pinfunction "2_2") (pintype "passive"))
    )
    (net (code "76") (name "GPIO41") (class "Default")
      (node (ref "J164") (pin "P$1") (pinfunction "P$1_P$1") (pintype "bidirectional"))
      (node (ref "J164") (pin "P$2") (pinfunction "P$2_P$2") (pintype "bidirectional"))
      (node (ref "J164") (pin "P$3") (pinfunction "P$3_P$3") (pintype "bidirectional"))
      (node (ref "J209") (pin "P$1") (pinfunction "P$1_P$1") (pintype "bidirectional"))
      (node (ref "J209") (pin "P$2") (pinfunction "P$2_P$2") (pintype "bidirectional"))
      (node (ref "J40") (pin "P$1") (pinfunction "P$1_P$1") (pintype "bidirectional"))
      (node (ref "J40") (pin "P$2") (pinfunction "P$2_P$2") (pintype "bidirectional"))
      (node (ref "L1") (pin "P$49") (pinfunction "GPIO41/SCLB_P$49") (pintype "bidirectional"))
      (node (ref "R10") (pin "2") (pinfunction "2_2") (pintype "passive"))
    )
    (net (code "77") (name "GPIO52") (class "Default")
      (node (ref "J165") (pin "P$1") (pinfunction "P$1_P$1") (pintype "bidirectional"))
      (node (ref "J165") (pin "P$2") (pinfunction "P$2_P$2") (pintype "bidirectional"))
      (node (ref "J165") (pin "P$3") (pinfunction "P$3_P$3") (pintype "bidirectional"))
      (node (ref "L1") (pin "P$48") (pinfunction "GPIO52_P$48") (pintype "bidirectional"))
    )
    (net (code "78") (name "GPIO56") (class "Default")
      (node (ref "J169") (pin "P$1") (pinfunction "P$1_P$1") (pintype "bidirectional"))
      (node (ref "J169") (pin "P$2") (pinfunction "P$2_P$2") (pintype "bidirectional"))
      (node (ref "J169") (pin "P$3") (pinfunction "P$3_P$3") (pintype "bidirectional"))
      (node (ref "L1") (pin "P$44") (pinfunction "GPIO56/SCITXDC_P$44") (pintype "bidirectional"))
      (node (ref "SV13") (pin "8") (pinfunction "8_8") (pintype "passive"))
    )
    (net (code "79") (name "GPIO58") (class "Default")
      (node (ref "J33") (pin "P$1") (pinfunction "P$1_P$1") (pintype "bidirectional"))
      (node (ref "J33") (pin "P$2") (pinfunction "P$2_P$2") (pintype "bidirectional"))
      (node (ref "J33") (pin "P$3") (pinfunction "P$3_P$3") (pintype "bidirectional"))
      (node (ref "L1") (pin "P$15") (pinfunction "GPIO58/SPISIMOA_P$15") (pintype "bidirectional"))
      (node (ref "U7") (pin "5") (pinfunction "SI_5") (pintype "bidirectional"))
    )
    (net (code "80") (name "GPIO59") (class "Default")
      (node (ref "J32") (pin "P$1") (pinfunction "P$1_P$1") (pintype "bidirectional"))
      (node (ref "J32") (pin "P$2") (pinfunction "P$2_P$2") (pintype "bidirectional"))
      (node (ref "J32") (pin "P$3") (pinfunction "P$3_P$3") (pintype "bidirectional"))
      (node (ref "L1") (pin "P$14") (pinfunction "GPIO59/SPISOMIA_P$14") (pintype "bidirectional"))
      (node (ref "U7") (pin "2") (pinfunction "SO_2") (pintype "bidirectional"))
    )
    (net (code "81") (name "GPIO60") (class "Default")
      (node (ref "IC2") (pin "11") (pinfunction "I_11") (pintype "input"))
      (node (ref "J19") (pin "P$1") (pinfunction "P$1_P$1") (pintype "bidirectional"))
      (node (ref "J19") (pin "P$2") (pinfunction "P$2_P$2") (pintype "bidirectional"))
      (node (ref "J19") (pin "P$3") (pinfunction "P$3_P$3") (pintype "bidirectional"))
      (node (ref "L1") (pin "P$7") (pinfunction "GPIO60/SPICLKA_P$7") (pintype "bidirectional"))
    )
    (net (code "82") (name "GPIO61") (class "Default")
      (node (ref "IC2") (pin "13") (pinfunction "I_13") (pintype "input"))
      (node (ref "J101") (pin "P$1") (pinfunction "P$1_P$1") (pintype "bidirectional"))
      (node (ref "J101") (pin "P$2") (pinfunction "P$2_P$2") (pintype "bidirectional"))
      (node (ref "J101") (pin "P$3") (pinfunction "P$3_P$3") (pintype "bidirectional"))
      (node (ref "L1") (pin "P$19") (pinfunction "GPIO61_P$19") (pintype "bidirectional"))
    )
    (net (code "83") (name "GPIO63") (class "Default")
      (node (ref "J158") (pin "P$1") (pinfunction "P$1_P$1") (pintype "bidirectional"))
      (node (ref "J158") (pin "P$2") (pinfunction "P$2_P$2") (pintype "bidirectional"))
      (node (ref "J158") (pin "P$3") (pinfunction "P$3_P$3") (pintype "bidirectional"))
      (node (ref "J204") (pin "P$1") (pinfunction "P$1_P$1") (pintype "bidirectional"))
      (node (ref "J204") (pin "P$2") (pinfunction "P$2_P$2") (pintype "bidirectional"))
      (node (ref "J36") (pin "P$2") (pinfunction "P$2_P$2") (pintype "bidirectional"))
      (node (ref "L1") (pin "P$55") (pinfunction "GPIO63/SPISIMOB_P$55") (pintype "bidirectional"))
    )
    (net (code "84") (name "GPIO64") (class "Default")
      (node (ref "J159") (pin "P$1") (pinfunction "P$1_P$1") (pintype "bidirectional"))
      (node (ref "J159") (pin "P$2") (pinfunction "P$2_P$2") (pintype "bidirectional"))
      (node (ref "J159") (pin "P$3") (pinfunction "P$3_P$3") (pintype "bidirectional"))
      (node (ref "J205") (pin "P$1") (pinfunction "P$1_P$1") (pintype "bidirectional"))
      (node (ref "J205") (pin "P$2") (pinfunction "P$2_P$2") (pintype "bidirectional"))
      (node (ref "J35") (pin "P$2") (pinfunction "P$2_P$2") (pintype "bidirectional"))
      (node (ref "L1") (pin "P$54") (pinfunction "GPIO64/SPISOMIB_P$54") (pintype "bidirectional"))
    )
    (net (code "85") (name "GPIO65") (class "Default")
      (node (ref "J166") (pin "P$1") (pinfunction "P$1_P$1") (pintype "bidirectional"))
      (node (ref "J166") (pin "P$2") (pinfunction "P$2_P$2") (pintype "bidirectional"))
      (node (ref "J166") (pin "P$3") (pinfunction "P$3_P$3") (pintype "bidirectional"))
      (node (ref "J206") (pin "P$1") (pinfunction "P$1_P$1") (pintype "bidirectional"))
      (node (ref "J206") (pin "P$2") (pinfunction "P$2_P$2") (pintype "bidirectional"))
      (node (ref "J38") (pin "P$2") (pinfunction "P$2_P$2") (pintype "bidirectional"))
      (node (ref "L1") (pin "P$47") (pinfunction "GPIO65/SPICLKB_P$47") (pintype "bidirectional"))
    )
    (net (code "86") (name "GPIO66") (class "Default")
      (node (ref "J154") (pin "P$1") (pinfunction "P$1_P$1") (pintype "bidirectional"))
      (node (ref "J154") (pin "P$2") (pinfunction "P$2_P$2") (pintype "bidirectional"))
      (node (ref "J154") (pin "P$3") (pinfunction "P$3_P$3") (pintype "bidirectional"))
      (node (ref "J207") (pin "P$1") (pinfunction "P$1_P$1") (pintype "bidirectional"))
      (node (ref "J207") (pin "P$2") (pinfunction "P$2_P$2") (pintype "bidirectional"))
      (node (ref "L1") (pin "P$59") (pinfunction "GPIO66_P$59") (pintype "bidirectional"))
    )
    (net (code "87") (name "GPIO67") (class "Default")
      (node (ref "J17") (pin "P$1") (pinfunction "P$1_P$1") (pintype "bidirectional"))
      (node (ref "J17") (pin "P$2") (pinfunction "P$2_P$2") (pintype "bidirectional"))
      (node (ref "J17") (pin "P$3") (pinfunction "P$3_P$3") (pintype "bidirectional"))
      (node (ref "L1") (pin "P$5") (pinfunction "GPIO67_P$5") (pintype "bidirectional"))
    )
    (net (code "88") (name "GPIO94") (class "Default")
      (node (ref "IC1") (pin "3") (pinfunction "I_3") (pintype "input"))
      (node (ref "J167") (pin "P$1") (pinfunction "P$1_P$1") (pintype "bidirectional"))
      (node (ref "J167") (pin "P$2") (pinfunction "P$2_P$2") (pintype "bidirectional"))
      (node (ref "J167") (pin "P$3") (pinfunction "P$3_P$3") (pintype "bidirectional"))
      (node (ref "L1") (pin "P$46") (pinfunction "GPIO94_P$46") (pintype "bidirectional"))
    )
    (net (code "89") (name "GPIO95") (class "Default")
      (node (ref "IC1") (pin "5") (pinfunction "I_5") (pintype "input"))
      (node (ref "J176") (pin "P$1") (pinfunction "P$1_P$1") (pintype "bidirectional"))
      (node (ref "J176") (pin "P$2") (pinfunction "P$2_P$2") (pintype "bidirectional"))
      (node (ref "J176") (pin "P$3") (pinfunction "P$3_P$3") (pintype "bidirectional"))
      (node (ref "L1") (pin "P$42") (pinfunction "GPIO95_P$42") (pintype "bidirectional"))
    )
    (net (code "90") (name "GPIO97") (class "Default")
      (node (ref "IC1") (pin "9") (pinfunction "I_9") (pintype "input"))
      (node (ref "J168") (pin "P$1") (pinfunction "P$1_P$1") (pintype "bidirectional"))
      (node (ref "J168") (pin "P$2") (pinfunction "P$2_P$2") (pintype "bidirectional"))
      (node (ref "J168") (pin "P$3") (pinfunction "P$3_P$3") (pintype "bidirectional"))
      (node (ref "L1") (pin "P$45") (pinfunction "GPIO97_P$45") (pintype "bidirectional"))
    )
    (net (code "91") (name "GPIO104") (class "Default")
      (node (ref "J28") (pin "P$1") (pinfunction "P$1_P$1") (pintype "bidirectional"))
      (node (ref "J28") (pin "P$2") (pinfunction "P$2_P$2") (pintype "bidirectional"))
      (node (ref "J28") (pin "P$3") (pinfunction "P$3_P$3") (pintype "bidirectional"))
      (node (ref "L1") (pin "P$10") (pinfunction "GPIO104/SDAA_P$10") (pintype "bidirectional"))
    )
    (net (code "92") (name "GPIO105") (class "Default")
      (node (ref "J21") (pin "P$1") (pinfunction "P$1_P$1") (pintype "bidirectional"))
      (node (ref "J21") (pin "P$2") (pinfunction "P$2_P$2") (pintype "bidirectional"))
      (node (ref "J21") (pin "P$3") (pinfunction "P$3_P$3") (pintype "bidirectional"))
      (node (ref "L1") (pin "P$9") (pinfunction "GPIO105/SCLA_P$9") (pintype "bidirectional"))
    )
    (net (code "93") (name "GPIO111") (class "Default")
      (node (ref "IC1") (pin "11") (pinfunction "I_11") (pintype "input"))
      (node (ref "J18") (pin "P$1") (pinfunction "P$1_P$1") (pintype "bidirectional"))
      (node (ref "J18") (pin "P$2") (pinfunction "P$2_P$2") (pintype "bidirectional"))
      (node (ref "J18") (pin "P$3") (pinfunction "P$3_P$3") (pintype "bidirectional"))
      (node (ref "L1") (pin "P$6") (pinfunction "GPIO111_P$6") (pintype "bidirectional"))
    )
    (net (code "94") (name "GPIO122") (class "Default")
      (node (ref "J66") (pin "P$1") (pinfunction "P$1_P$1") (pintype "bidirectional"))
      (node (ref "J66") (pin "P$2") (pinfunction "P$2_P$2") (pintype "bidirectional"))
      (node (ref "J99") (pin "P$1") (pinfunction "P$1_P$1") (pintype "bidirectional"))
      (node (ref "J99") (pin "P$2") (pinfunction "P$2_P$2") (pintype "bidirectional"))
      (node (ref "J99") (pin "P$3") (pinfunction "P$3_P$3") (pintype "bidirectional"))
      (node (ref "L1") (pin "P$17") (pinfunction "GPIO122_P$17") (pintype "bidirectional"))
    )
    (net (code "95") (name "GPIO123") (class "Default")
      (node (ref "J100") (pin "P$1") (pinfunction "P$1_P$1") (pintype "bidirectional"))
      (node (ref "J100") (pin "P$2") (pinfunction "P$2_P$2") (pintype "bidirectional"))
      (node (ref "J100") (pin "P$3") (pinfunction "P$3_P$3") (pintype "bidirectional"))
      (node (ref "J67") (pin "P$1") (pinfunction "P$1_P$1") (pintype "bidirectional"))
      (node (ref "J67") (pin "P$2") (pinfunction "P$2_P$2") (pintype "bidirectional"))
      (node (ref "L1") (pin "P$18") (pinfunction "GPIO123_P$18") (pintype "bidirectional"))
    )
    (net (code "96") (name "GPIO124") (class "Default")
      (node (ref "J31") (pin "P$1") (pinfunction "P$1_P$1") (pintype "bidirectional"))
      (node (ref "J31") (pin "P$2") (pinfunction "P$2_P$2") (pintype "bidirectional"))
      (node (ref "J31") (pin "P$3") (pinfunction "P$3_P$3") (pintype "bidirectional"))
      (node (ref "J68") (pin "P$1") (pinfunction "P$1_P$1") (pintype "bidirectional"))
      (node (ref "J68") (pin "P$2") (pinfunction "P$2_P$2") (pintype "bidirectional"))
      (node (ref "L1") (pin "P$13") (pinfunction "GPIO124_P$13") (pintype "bidirectional"))
    )
    (net (code "97") (name "GPIO125") (class "Default")
      (node (ref "J30") (pin "P$1") (pinfunction "P$1_P$1") (pintype "bidirectional"))
      (node (ref "J30") (pin "P$2") (pinfunction "P$2_P$2") (pintype "bidirectional"))
      (node (ref "J30") (pin "P$3") (pinfunction "P$3_P$3") (pintype "bidirectional"))
      (node (ref "J69") (pin "P$1") (pinfunction "P$1_P$1") (pintype "bidirectional"))
      (node (ref "J69") (pin "P$2") (pinfunction "P$2_P$2") (pintype "bidirectional"))
      (node (ref "L1") (pin "P$12") (pinfunction "GPIO125_P$12") (pintype "bidirectional"))
    )
    (net (code "98") (name "GPIO130") (class "Default")
      (node (ref "IC1") (pin "13") (pinfunction "I_13") (pintype "input"))
      (node (ref "J156") (pin "P$1") (pinfunction "P$1_P$1") (pintype "bidirectional"))
      (node (ref "J156") (pin "P$2") (pinfunction "P$2_P$2") (pintype "bidirectional"))
      (node (ref "J156") (pin "P$3") (pinfunction "P$3_P$3") (pintype "bidirectional"))
      (node (ref "L1") (pin "P$57") (pinfunction "GPIO130_P$57") (pintype "bidirectional"))
    )
    (net (code "99") (name "GPIO131") (class "Default")
      (node (ref "IC2") (pin "1") (pinfunction "I_1") (pintype "input"))
      (node (ref "J155") (pin "P$1") (pinfunction "P$1_P$1") (pintype "bidirectional"))
      (node (ref "J155") (pin "P$2") (pinfunction "P$2_P$2") (pintype "bidirectional"))
      (node (ref "J155") (pin "P$3") (pinfunction "P$3_P$3") (pintype "bidirectional"))
      (node (ref "L1") (pin "P$58") (pinfunction "GPIO131_P$58") (pintype "bidirectional"))
    )
    (net (code "100") (name "GPIO139") (class "Default")
      (node (ref "J170") (pin "P$1") (pinfunction "P$1_P$1") (pintype "bidirectional"))
      (node (ref "J170") (pin "P$2") (pinfunction "P$2_P$2") (pintype "bidirectional"))
      (node (ref "J170") (pin "P$3") (pinfunction "P$3_P$3") (pintype "bidirectional"))
      (node (ref "L1") (pin "P$43") (pinfunction "GPIO139/SCIRXDC_P$43") (pintype "bidirectional"))
      (node (ref "SV13") (pin "1") (pinfunction "1_1") (pintype "passive"))
    )
    (net (code "101") (name "GPIO157") (class "Default")
      (node (ref "IC3") (pin "1") (pinfunction "I_1") (pintype "input"))
      (node (ref "J141") (pin "P$1") (pinfunction "P$1_P$1") (pintype "bidirectional"))
      (node (ref "J141") (pin "P$2") (pinfunction "P$2_P$2") (pintype "bidirectional"))
      (node (ref "J141") (pin "P$3") (pinfunction "P$3_P$3") (pintype "bidirectional"))
      (node (ref "L1") (pin "P$72") (pinfunction "DAC3_P$72") (pintype "bidirectional"))
    )
    (net (code "102") (name "GPIO158") (class "Default")
      (node (ref "IC3") (pin "3") (pinfunction "I_3") (pintype "input"))
      (node (ref "J142") (pin "P$1") (pinfunction "P$1_P$1") (pintype "bidirectional"))
      (node (ref "J142") (pin "P$2") (pinfunction "P$2_P$2") (pintype "bidirectional"))
      (node (ref "J142") (pin "P$3") (pinfunction "P$3_P$3") (pintype "bidirectional"))
      (node (ref "L1") (pin "P$71") (pinfunction "DAC4_P$71") (pintype "bidirectional"))
    )
    (net (code "103") (name "GPIO159") (class "Default")
      (node (ref "IC3") (pin "5") (pinfunction "I_5") (pintype "input"))
      (node (ref "J114") (pin "P$1") (pinfunction "P$1_P$1") (pintype "bidirectional"))
      (node (ref "J114") (pin "P$2") (pinfunction "P$2_P$2") (pintype "bidirectional"))
      (node (ref "J114") (pin "P$3") (pinfunction "P$3_P$3") (pintype "bidirectional"))
      (node (ref "L1") (pin "P$32") (pinfunction "DAC1_P$32") (pintype "bidirectional"))
    )
    (net (code "104") (name "GPIO160") (class "Default")
      (node (ref "IC3") (pin "9") (pinfunction "I_9") (pintype "input"))
      (node (ref "J113") (pin "P$1") (pinfunction "P$1_P$1") (pintype "bidirectional"))
      (node (ref "J113") (pin "P$2") (pinfunction "P$2_P$2") (pintype "bidirectional"))
      (node (ref "J113") (pin "P$3") (pinfunction "P$3_P$3") (pintype "bidirectional"))
      (node (ref "L1") (pin "P$31") (pinfunction "DAC2_P$31") (pintype "bidirectional"))
    )
    (net (code "105") (name "MENABLE") (class "Default")
      (node (ref "S159") (pin "P$2") (pinfunction "P2_P$2") (pintype "bidirectional"))
      (node (ref "U2") (pin "P$3") (pinfunction "NSLEEP_P$3") (pintype "bidirectional"))
      (node (ref "U4") (pin "P$3") (pinfunction "NSLEEP_P$3") (pintype "bidirectional"))
    )
    (net (code "106") (name "MOTOR1+") (class "Default")
      (node (ref "SV3") (pin "1") (pinfunction "1_1") (pintype "passive"))
      (node (ref "SV3") (pin "3") (pinfunction "3_3") (pintype "passive"))
      (node (ref "SV3") (pin "5") (pinfunction "5_5") (pintype "passive"))
      (node (ref "U1") (pin "15") (pinfunction "OUTB_15") (pintype "bidirectional"))
    )
    (net (code "107") (name "MOTOR1-") (class "Default")
      (node (ref "SV3") (pin "2") (pinfunction "2_2") (pintype "passive"))
      (node (ref "SV3") (pin "4") (pinfunction "4_4") (pintype "passive"))
      (node (ref "SV3") (pin "6") (pinfunction "6_6") (pintype "passive"))
      (node (ref "U1") (pin "10") (pinfunction "OUTA_10") (pintype "bidirectional"))
    )
    (net (code "108") (name "MOTOR2+") (class "Default")
      (node (ref "SV1") (pin "1") (pinfunction "1_1") (pintype "passive"))
      (node (ref "SV1") (pin "3") (pinfunction "3_3") (pintype "passive"))
      (node (ref "SV1") (pin "5") (pinfunction "5_5") (pintype "passive"))
      (node (ref "U5") (pin "15") (pinfunction "OUTB_15") (pintype "bidirectional"))
    )
    (net (code "109") (name "MOTOR2-") (class "Default")
      (node (ref "SV1") (pin "2") (pinfunction "2_2") (pintype "passive"))
      (node (ref "SV1") (pin "4") (pinfunction "4_4") (pintype "passive"))
      (node (ref "SV1") (pin "6") (pinfunction "6_6") (pintype "passive"))
      (node (ref "U5") (pin "10") (pinfunction "OUTA_10") (pintype "bidirectional"))
    )
    (net (code "110") (name "MSP430_SCL") (class "Default")
      (node (ref "J39") (pin "P$1") (pinfunction "P$1_P$1") (pintype "bidirectional"))
      (node (ref "J39") (pin "P$2") (pinfunction "P$2_P$2") (pintype "bidirectional"))
      (node (ref "SV17") (pin "13") (pinfunction "13_13") (pintype "passive"))
      (node (ref "SV17") (pin "14") (pinfunction "14_14") (pintype "passive"))
      (node (ref "SV19") (pin "7") (pinfunction "7_7") (pintype "passive"))
    )
    (net (code "111") (name "MSP430_SDA") (class "Default")
      (node (ref "J41") (pin "P$1") (pinfunction "P$1_P$1") (pintype "bidirectional"))
      (node (ref "J41") (pin "P$2") (pinfunction "P$2_P$2") (pintype "bidirectional"))
      (node (ref "SV17") (pin "11") (pinfunction "11_11") (pintype "passive"))
      (node (ref "SV17") (pin "12") (pinfunction "12_12") (pintype "passive"))
      (node (ref "SV19") (pin "6") (pinfunction "6_6") (pintype "passive"))
    )
    (net (code "112") (name "Net-(3V3-PadA)") (class "Default")
      (node (ref "3V3") (pin "A") (pinfunction "A_A") (pintype "passive"))
      (node (ref "R27") (pin "1") (pinfunction "1_1") (pintype "passive"))
    )
    (net (code "113") (name "Net-(5V-PadA)") (class "Default")
      (node (ref "5V") (pin "A") (pinfunction "A_A") (pintype "passive"))
      (node (ref "R26") (pin "1") (pinfunction "1_1") (pintype "passive"))
    )
    (net (code "114") (name "Net-(B1-PadP$1)") (class "Default")
      (node (ref "B1") (pin "P$1") (pinfunction "P$1_P$1") (pintype "bidirectional"))
      (node (ref "R40") (pin "2") (pinfunction "2_2") (pintype "passive"))
    )
    (net (code "115") (name "Net-(B4-P1)") (class "Default")
      (node (ref "B4") (pin "P$1") (pinfunction "P1_P$1") (pintype "bidirectional"))
      (node (ref "SV10") (pin "1") (pinfunction "1_1") (pintype "passive"))
      (node (ref "U6") (pin "P$1") (pinfunction "IN1_P$1") (pintype "bidirectional"))
    )
    (net (code "116") (name "Net-(B5-P1)") (class "Default")
      (node (ref "B5") (pin "P$1") (pinfunction "P1_P$1") (pintype "bidirectional"))
      (node (ref "SV9") (pin "2") (pinfunction "2_2") (pintype "passive"))
      (node (ref "U6") (pin "P$6") (pinfunction "OUT2_P$6") (pintype "bidirectional"))
    )
    (net (code "117") (name "Net-(ETH1-INT{slash})") (class "Default")
      (node (ref "ETH1") (pin "P$6") (pinfunction "INT/_P$6") (pintype "bidirectional"))
      (node (ref "SV5") (pin "7") (pinfunction "7_7") (pintype "passive"))
      (node (ref "SV5") (pin "8") (pinfunction "8_8") (pintype "passive"))
    )
    (net (code "118") (name "Net-(ETH1-MISO)") (class "Default")
      (node (ref "ETH1") (pin "P$7") (pinfunction "MISO_P$7") (pintype "bidirectional"))
      (node (ref "SV5") (pin "10") (pinfunction "10_10") (pintype "passive"))
      (node (ref "SV5") (pin "9") (pinfunction "9_9") (pintype "passive"))
    )
    (net (code "119") (name "Net-(ETH1-MOSI)") (class "Default")
      (node (ref "ETH1") (pin "P$3") (pinfunction "MOSI_P$3") (pintype "bidirectional"))
      (node (ref "SV6") (pin "10") (pinfunction "10_10") (pintype "passive"))
      (node (ref "SV6") (pin "9") (pinfunction "9_9") (pintype "passive"))
    )
    (net (code "120") (name "Net-(ETH1-RESET)") (class "Default")
      (node (ref "ETH1") (pin "P$8") (pinfunction "RESET_P$8") (pintype "bidirectional"))
      (node (ref "SV6") (pin "7") (pinfunction "7_7") (pintype "passive"))
      (node (ref "SV6") (pin "8") (pinfunction "8_8") (pintype "passive"))
    )
    (net (code "121") (name "Net-(ETH1-SCLK)") (class "Default")
      (node (ref "ETH1") (pin "P$4") (pinfunction "SCLK_P$4") (pintype "bidirectional"))
      (node (ref "SV6") (pin "11") (pinfunction "11_11") (pintype "passive"))
      (node (ref "SV6") (pin "12") (pinfunction "12_12") (pintype "passive"))
    )
    (net (code "122") (name "Net-(ETH1-SS{slash})") (class "Default")
      (node (ref "ETH1") (pin "P$5") (pinfunction "SS/_P$5") (pintype "bidirectional"))
      (node (ref "SV5") (pin "11") (pinfunction "11_11") (pintype "passive"))
      (node (ref "SV5") (pin "12") (pinfunction "12_12") (pintype "passive"))
    )
    (net (code "123") (name "Net-(IC1A-O)") (class "Default")
      (node (ref "IC1") (pin "2") (pinfunction "O_2") (pintype "output"))
      (node (ref "LED1") (pin "C") (pinfunction "C_C") (pintype "passive"))
    )
    (net (code "124") (name "Net-(IC1B-O)") (class "Default")
      (node (ref "IC1") (pin "4") (pinfunction "O_4") (pintype "output"))
      (node (ref "LED2") (pin "C") (pinfunction "C_C") (pintype "passive"))
    )
    (net (code "125") (name "Net-(IC1C-O)") (class "Default")
      (node (ref "IC1") (pin "6") (pinfunction "O_6") (pintype "output"))
      (node (ref "LED3") (pin "C") (pinfunction "C_C") (pintype "passive"))
    )
    (net (code "126") (name "Net-(IC1D-O)") (class "Default")
      (node (ref "IC1") (pin "8") (pinfunction "O_8") (pintype "output"))
      (node (ref "LED4") (pin "C") (pinfunction "C_C") (pintype "passive"))
    )
    (net (code "127") (name "Net-(IC1E-O)") (class "Default")
      (node (ref "IC1") (pin "10") (pinfunction "O_10") (pintype "output"))
      (node (ref "LED5") (pin "C") (pinfunction "C_C") (pintype "passive"))
    )
    (net (code "128") (name "Net-(IC1F-O)") (class "Default")
      (node (ref "IC1") (pin "12") (pinfunction "O_12") (pintype "output"))
      (node (ref "LED6") (pin "C") (pinfunction "C_C") (pintype "passive"))
    )
    (net (code "129") (name "Net-(IC2A-O)") (class "Default")
      (node (ref "IC2") (pin "2") (pinfunction "O_2") (pintype "output"))
      (node (ref "LED7") (pin "C") (pinfunction "C_C") (pintype "passive"))
    )
    (net (code "130") (name "Net-(IC2B-O)") (class "Default")
      (node (ref "IC2") (pin "4") (pinfunction "O_4") (pintype "output"))
      (node (ref "LED8") (pin "C") (pinfunction "C_C") (pintype "passive"))
    )
    (net (code "131") (name "Net-(IC2C-O)") (class "Default")
      (node (ref "IC2") (pin "6") (pinfunction "O_6") (pintype "output"))
      (node (ref "LED9") (pin "C") (pinfunction "C_C") (pintype "passive"))
    )
    (net (code "132") (name "Net-(IC2D-O)") (class "Default")
      (node (ref "IC2") (pin "8") (pinfunction "O_8") (pintype "output"))
      (node (ref "LED10") (pin "C") (pinfunction "C_C") (pintype "passive"))
    )
    (net (code "133") (name "Net-(IC2E-O)") (class "Default")
      (node (ref "IC2") (pin "10") (pinfunction "O_10") (pintype "output"))
      (node (ref "LED11") (pin "C") (pinfunction "C_C") (pintype "passive"))
    )
    (net (code "134") (name "Net-(IC2F-O)") (class "Default")
      (node (ref "IC2") (pin "12") (pinfunction "O_12") (pintype "output"))
      (node (ref "LED12") (pin "C") (pinfunction "C_C") (pintype "passive"))
    )
    (net (code "135") (name "Net-(IC3A-O)") (class "Default")
      (node (ref "IC3") (pin "2") (pinfunction "O_2") (pintype "output"))
      (node (ref "LED13") (pin "C") (pinfunction "C_C") (pintype "passive"))
    )
    (net (code "136") (name "Net-(IC3B-O)") (class "Default")
      (node (ref "IC3") (pin "4") (pinfunction "O_4") (pintype "output"))
      (node (ref "LED14") (pin "C") (pinfunction "C_C") (pintype "passive"))
    )
    (net (code "137") (name "Net-(IC3C-O)") (class "Default")
      (node (ref "IC3") (pin "6") (pinfunction "O_6") (pintype "output"))
      (node (ref "LED15") (pin "C") (pinfunction "C_C") (pintype "passive"))
    )
    (net (code "138") (name "Net-(IC3D-O)") (class "Default")
      (node (ref "IC3") (pin "8") (pinfunction "O_8") (pintype "output"))
      (node (ref "LED16") (pin "C") (pinfunction "C_C") (pintype "passive"))
    )
    (net (code "139") (name "Net-(IC3E-I)") (class "Default")
      (node (ref "IC3") (pin "11") (pinfunction "I_11") (pintype "input"))
      (node (ref "J194") (pin "P$1") (pinfunction "P$1_P$1") (pintype "bidirectional"))
      (node (ref "J194") (pin "P$2") (pinfunction "P$2_P$2") (pintype "bidirectional"))
    )
    (net (code "140") (name "Net-(IC3E-O)") (class "Default")
      (node (ref "IC3") (pin "10") (pinfunction "O_10") (pintype "output"))
      (node (ref "R40") (pin "1") (pinfunction "1_1") (pintype "passive"))
    )
    (net (code "141") (name "Net-(J6-PadP$1)") (class "Default")
      (node (ref "J6") (pin "P$1") (pinfunction "P$1_P$1") (pintype "bidirectional"))
      (node (ref "J6") (pin "P$2") (pinfunction "P$2_P$2") (pintype "bidirectional"))
      (node (ref "J6") (pin "P$3") (pinfunction "P$3_P$3") (pintype "bidirectional"))
      (node (ref "R1") (pin "1") (pinfunction "1_1") (pintype "passive"))
    )
    (net (code "142") (name "Net-(J12-PadP$1)") (class "Default")
      (node (ref "J12") (pin "P$1") (pinfunction "P$1_P$1") (pintype "bidirectional"))
      (node (ref "J12") (pin "P$2") (pinfunction "P$2_P$2") (pintype "bidirectional"))
    )
    (net (code "143") (name "Net-(J13-PadP$1)") (class "Default")
      (node (ref "J13") (pin "P$1") (pinfunction "P$1_P$1") (pintype "bidirectional"))
      (node (ref "J13") (pin "P$2") (pinfunction "P$2_P$2") (pintype "bidirectional"))
    )
    (net (code "144") (name "Net-(J22-PadP$1)") (class "Default")
      (node (ref "J22") (pin "P$1") (pinfunction "P$1_P$1") (pintype "bidirectional"))
      (node (ref "J22") (pin "P$2") (pinfunction "P$2_P$2") (pintype "bidirectional"))
    )
    (net (code "145") (name "Net-(J24-PadP$1)") (class "Default")
      (node (ref "J24") (pin "P$1") (pinfunction "P$1_P$1") (pintype "bidirectional"))
      (node (ref "J24") (pin "P$2") (pinfunction "P$2_P$2") (pintype "bidirectional"))
      (node (ref "J24") (pin "P$3") (pinfunction "P$3_P$3") (pintype "bidirectional"))
      (node (ref "R2") (pin "1") (pinfunction "1_1") (pintype "passive"))
    )
    (net (code "146") (name "Net-(J43-PadP$2)") (class "Default")
      (node (ref "J43") (pin "P$2") (pinfunction "P$2_P$2") (pintype "bidirectional"))
      (node (ref "P2") (pin "1") (pinfunction "1_1") (pintype "bidirectional"))
      (node (ref "R39") (pin "1") (pinfunction "1_1") (pintype "passive"))
      (node (ref "SV17") (pin "10") (pinfunction "10_10") (pintype "passive"))
      (node (ref "SV17") (pin "9") (pinfunction "9_9") (pintype "passive"))
      (node (ref "SV19") (pin "5") (pinfunction "5_5") (pintype "passive"))
    )
    (net (code "147") (name "Net-(J43-PadP$3)") (class "Default")
      (node (ref "J43") (pin "P$3") (pinfunction "P$3_P$3") (pintype "bidirectional"))
      (node (ref "SV17") (pin "7") (pinfunction "7_7") (pintype "passive"))
      (node (ref "SV17") (pin "8") (pinfunction "8_8") (pintype "passive"))
      (node (ref "SV19") (pin "4") (pinfunction "4_4") (pintype "passive"))
    )
    (net (code "148") (name "Net-(J88-PadP$1)") (class "Default")
      (node (ref "J88") (pin "P$1") (pinfunction "P$1_P$1") (pintype "bidirectional"))
      (node (ref "J91") (pin "P$1") (pinfunction "P$1_P$1") (pintype "bidirectional"))
      (node (ref "J91") (pin "P$2") (pinfunction "P$2_P$2") (pintype "bidirectional"))
    )
    (net (code "149") (name "Net-(J88-PadP$3)") (class "Default")
      (node (ref "J88") (pin "P$3") (pinfunction "P$3_P$3") (pintype "bidirectional"))
      (node (ref "J92") (pin "P$1") (pinfunction "P$1_P$1") (pintype "bidirectional"))
      (node (ref "J92") (pin "P$2") (pinfunction "P$2_P$2") (pintype "bidirectional"))
    )
    (net (code "150") (name "Net-(J88-PadP$4)") (class "Default")
      (node (ref "J88") (pin "P$4") (pinfunction "P$4_P$4") (pintype "bidirectional"))
      (node (ref "J93") (pin "P$1") (pinfunction "P$1_P$1") (pintype "bidirectional"))
      (node (ref "J93") (pin "P$2") (pinfunction "P$2_P$2") (pintype "bidirectional"))
    )
    (net (code "151") (name "Net-(J88-R+)") (class "Default")
      (node (ref "J88") (pin "P$2") (pinfunction "R+_P$2") (pintype "bidirectional"))
      (node (ref "J89") (pin "P$1") (pinfunction "P$1_P$1") (pintype "bidirectional"))
      (node (ref "J89") (pin "P$2") (pinfunction "P$2_P$2") (pintype "bidirectional"))
    )
    (net (code "152") (name "Net-(J88-R-)") (class "Default")
      (node (ref "J88") (pin "P$5") (pinfunction "R-_P$5") (pintype "bidirectional"))
      (node (ref "J90") (pin "P$1") (pinfunction "P$1_P$1") (pintype "bidirectional"))
      (node (ref "J90") (pin "P$2") (pinfunction "P$2_P$2") (pintype "bidirectional"))
    )
    (net (code "153") (name "Net-(LED1-PadA)") (class "Default")
      (node (ref "LED1") (pin "A") (pinfunction "A_A") (pintype "passive"))
      (node (ref "R11") (pin "1") (pinfunction "1_1") (pintype "passive"))
    )
    (net (code "154") (name "Net-(LED2-PadA)") (class "Default")
      (node (ref "LED2") (pin "A") (pinfunction "A_A") (pintype "passive"))
      (node (ref "R12") (pin "1") (pinfunction "1_1") (pintype "passive"))
    )
    (net (code "155") (name "Net-(LED3-PadA)") (class "Default")
      (node (ref "LED3") (pin "A") (pinfunction "A_A") (pintype "passive"))
      (node (ref "R13") (pin "1") (pinfunction "1_1") (pintype "passive"))
    )
    (net (code "156") (name "Net-(LED4-PadA)") (class "Default")
      (node (ref "LED4") (pin "A") (pinfunction "A_A") (pintype "passive"))
      (node (ref "R14") (pin "1") (pinfunction "1_1") (pintype "passive"))
    )
    (net (code "157") (name "Net-(LED5-PadA)") (class "Default")
      (node (ref "LED5") (pin "A") (pinfunction "A_A") (pintype "passive"))
      (node (ref "R15") (pin "1") (pinfunction "1_1") (pintype "passive"))
    )
    (net (code "158") (name "Net-(LED6-PadA)") (class "Default")
      (node (ref "LED6") (pin "A") (pinfunction "A_A") (pintype "passive"))
      (node (ref "R16") (pin "1") (pinfunction "1_1") (pintype "passive"))
    )
    (net (code "159") (name "Net-(LED7-PadA)") (class "Default")
      (node (ref "LED7") (pin "A") (pinfunction "A_A") (pintype "passive"))
      (node (ref "R17") (pin "1") (pinfunction "1_1") (pintype "passive"))
    )
    (net (code "160") (name "Net-(LED8-PadA)") (class "Default")
      (node (ref "LED8") (pin "A") (pinfunction "A_A") (pintype "passive"))
      (node (ref "R19") (pin "1") (pinfunction "1_1") (pintype "passive"))
    )
    (net (code "161") (name "Net-(LED9-PadA)") (class "Default")
      (node (ref "LED9") (pin "A") (pinfunction "A_A") (pintype "passive"))
      (node (ref "R20") (pin "1") (pinfunction "1_1") (pintype "passive"))
    )
    (net (code "162") (name "Net-(LED10-PadA)") (class "Default")
      (node (ref "LED10") (pin "A") (pinfunction "A_A") (pintype "passive"))
      (node (ref "R21") (pin "1") (pinfunction "1_1") (pintype "passive"))
    )
    (net (code "163") (name "Net-(LED11-PadA)") (class "Default")
      (node (ref "LED11") (pin "A") (pinfunction "A_A") (pintype "passive"))
      (node (ref "R22") (pin "1") (pinfunction "1_1") (pintype "passive"))
    )
    (net (code "164") (name "Net-(LED12-PadA)") (class "Default")
      (node (ref "LED12") (pin "A") (pinfunction "A_A") (pintype "passive"))
      (node (ref "R23") (pin "1") (pinfunction "1_1") (pintype "passive"))
    )
    (net (code "165") (name "Net-(LED13-PadA)") (class "Default")
      (node (ref "LED13") (pin "A") (pinfunction "A_A") (pintype "passive"))
      (node (ref "R28") (pin "1") (pinfunction "1_1") (pintype "passive"))
    )
    (net (code "166") (name "Net-(LED14-PadA)") (class "Default")
      (node (ref "LED14") (pin "A") (pinfunction "A_A") (pintype "passive"))
      (node (ref "R29") (pin "1") (pinfunction "1_1") (pintype "passive"))
    )
    (net (code "167") (name "Net-(LED15-PadA)") (class "Default")
      (node (ref "LED15") (pin "A") (pinfunction "A_A") (pintype "passive"))
      (node (ref "R30") (pin "1") (pinfunction "1_1") (pintype "passive"))
    )
    (net (code "168") (name "Net-(LED16-PadA)") (class "Default")
      (node (ref "LED16") (pin "A") (pinfunction "A_A") (pintype "passive"))
      (node (ref "R31") (pin "1") (pinfunction "1_1") (pintype "passive"))
    )
    (net (code "169") (name "Net-(LED17-PadA)") (class "Default")
      (node (ref "LED17") (pin "A") (pinfunction "A_A") (pintype "passive"))
      (node (ref "R36") (pin "1") (pinfunction "1_1") (pintype "passive"))
    )
    (net (code "170") (name "Net-(LED18-PadA)") (class "Default")
      (node (ref "LED18") (pin "A") (pinfunction "A_A") (pintype "passive"))
      (node (ref "R45") (pin "1") (pinfunction "1_1") (pintype "passive"))
    )
    (net (code "171") (name "Net-(R45-Pad2)") (class "Default")
      (node (ref "R45") (pin "2") (pinfunction "2_2") (pintype "passive"))
      (node (ref "SV16") (pin "17") (pinfunction "17_17") (pintype "passive"))
      (node (ref "SV16") (pin "18") (pinfunction "18_18") (pintype "passive"))
      (node (ref "SV18") (pin "9") (pinfunction "9_9") (pintype "passive"))
    )
    (net (code "172") (name "Net-(S1-P3)") (class "Default")
      (node (ref "R24") (pin "1") (pinfunction "1_1") (pintype "passive"))
      (node (ref "S1") (pin "P$3") (pinfunction "P3_P$3") (pintype "bidirectional"))
    )
    (net (code "173") (name "Net-(S130-PadP$1)") (class "Default")
      (node (ref "S130") (pin "P$1") (pinfunction "P$1_P$1") (pintype "bidirectional"))
      (node (ref "S130") (pin "P$2") (pinfunction "P$2_P$2") (pintype "bidirectional"))
      (node (ref "S130") (pin "P$3") (pinfunction "P$3_P$3") (pintype "bidirectional"))
      (node (ref "S130") (pin "P$4") (pinfunction "P$4_P$4") (pintype "bidirectional"))
      (node (ref "S130") (pin "P$5") (pinfunction "P$5_P$5") (pintype "bidirectional"))
    )
    (net (code "174") (name "Net-(S138-PadP$1)") (class "Default")
      (node (ref "S138") (pin "P$1") (pinfunction "P$1_P$1") (pintype "bidirectional"))
      (node (ref "S138") (pin "P$2") (pinfunction "P$2_P$2") (pintype "bidirectional"))
      (node (ref "S138") (pin "P$3") (pinfunction "P$3_P$3") (pintype "bidirectional"))
      (node (ref "S138") (pin "P$4") (pinfunction "P$4_P$4") (pintype "bidirectional"))
      (node (ref "S138") (pin "P$5") (pinfunction "P$5_P$5") (pintype "bidirectional"))
    )
    (net (code "175") (name "Net-(S139-PadP$1)") (class "Default")
      (node (ref "S139") (pin "P$1") (pinfunction "P$1_P$1") (pintype "bidirectional"))
      (node (ref "S139") (pin "P$2") (pinfunction "P$2_P$2") (pintype "bidirectional"))
      (node (ref "S139") (pin "P$3") (pinfunction "P$3_P$3") (pintype "bidirectional"))
      (node (ref "S139") (pin "P$4") (pinfunction "P$4_P$4") (pintype "bidirectional"))
      (node (ref "S139") (pin "P$5") (pinfunction "P$5_P$5") (pintype "bidirectional"))
    )
    (net (code "176") (name "Net-(S147-PadP$1)") (class "Default")
      (node (ref "S147") (pin "P$1") (pinfunction "P$1_P$1") (pintype "bidirectional"))
      (node (ref "S147") (pin "P$2") (pinfunction "P$2_P$2") (pintype "bidirectional"))
      (node (ref "S147") (pin "P$3") (pinfunction "P$3_P$3") (pintype "bidirectional"))
      (node (ref "S147") (pin "P$4") (pinfunction "P$4_P$4") (pintype "bidirectional"))
      (node (ref "S147") (pin "P$5") (pinfunction "P$5_P$5") (pintype "bidirectional"))
    )
    (net (code "177") (name "Net-(S159-P3)") (class "Default")
      (node (ref "R18") (pin "1") (pinfunction "1_1") (pintype "passive"))
      (node (ref "S159") (pin "P$3") (pinfunction "P3_P$3") (pintype "bidirectional"))
    )
    (net (code "178") (name "Net-(S167-PadP$1)") (class "Default")
      (node (ref "S167") (pin "P$1") (pinfunction "P$1_P$1") (pintype "bidirectional"))
      (node (ref "S167") (pin "P$2") (pinfunction "P$2_P$2") (pintype "bidirectional"))
      (node (ref "S167") (pin "P$3") (pinfunction "P$3_P$3") (pintype "bidirectional"))
      (node (ref "S167") (pin "P$4") (pinfunction "P$4_P$4") (pintype "bidirectional"))
      (node (ref "S167") (pin "P$5") (pinfunction "P$5_P$5") (pintype "bidirectional"))
    )
    (net (code "179") (name "Net-(S168-PadP$1)") (class "Default")
      (node (ref "S168") (pin "P$1") (pinfunction "P$1_P$1") (pintype "bidirectional"))
      (node (ref "S168") (pin "P$2") (pinfunction "P$2_P$2") (pintype "bidirectional"))
      (node (ref "S168") (pin "P$3") (pinfunction "P$3_P$3") (pintype "bidirectional"))
      (node (ref "S168") (pin "P$4") (pinfunction "P$4_P$4") (pintype "bidirectional"))
      (node (ref "S168") (pin "P$5") (pinfunction "P$5_P$5") (pintype "bidirectional"))
    )
    (net (code "180") (name "Net-(S169-PadP$1)") (class "Default")
      (node (ref "S169") (pin "P$1") (pinfunction "P$1_P$1") (pintype "bidirectional"))
      (node (ref "S169") (pin "P$2") (pinfunction "P$2_P$2") (pintype "bidirectional"))
      (node (ref "S169") (pin "P$3") (pinfunction "P$3_P$3") (pintype "bidirectional"))
      (node (ref "S169") (pin "P$4") (pinfunction "P$4_P$4") (pintype "bidirectional"))
      (node (ref "S169") (pin "P$5") (pinfunction "P$5_P$5") (pintype "bidirectional"))
    )
    (net (code "181") (name "Net-(S170-PadP$1)") (class "Default")
      (node (ref "S170") (pin "P$1") (pinfunction "P$1_P$1") (pintype "bidirectional"))
      (node (ref "S170") (pin "P$2") (pinfunction "P$2_P$2") (pintype "bidirectional"))
      (node (ref "S170") (pin "P$3") (pinfunction "P$3_P$3") (pintype "bidirectional"))
      (node (ref "S170") (pin "P$4") (pinfunction "P$4_P$4") (pintype "bidirectional"))
      (node (ref "S170") (pin "P$5") (pinfunction "P$5_P$5") (pintype "bidirectional"))
    )
    (net (code "182") (name "Net-(S171-PadP$1)") (class "Default")
      (node (ref "S171") (pin "P$1") (pinfunction "P$1_P$1") (pintype "bidirectional"))
      (node (ref "S171") (pin "P$2") (pinfunction "P$2_P$2") (pintype "bidirectional"))
      (node (ref "S171") (pin "P$3") (pinfunction "P$3_P$3") (pintype "bidirectional"))
      (node (ref "S171") (pin "P$4") (pinfunction "P$4_P$4") (pintype "bidirectional"))
      (node (ref "S171") (pin "P$5") (pinfunction "P$5_P$5") (pintype "bidirectional"))
    )
    (net (code "183") (name "Net-(S172-PadP$1)") (class "Default")
      (node (ref "S172") (pin "P$1") (pinfunction "P$1_P$1") (pintype "bidirectional"))
      (node (ref "S172") (pin "P$2") (pinfunction "P$2_P$2") (pintype "bidirectional"))
      (node (ref "S172") (pin "P$3") (pinfunction "P$3_P$3") (pintype "bidirectional"))
      (node (ref "S172") (pin "P$4") (pinfunction "P$4_P$4") (pintype "bidirectional"))
      (node (ref "S172") (pin "P$5") (pinfunction "P$5_P$5") (pintype "bidirectional"))
    )
    (net (code "184") (name "Net-(S173-PadP$1)") (class "Default")
      (node (ref "S173") (pin "P$1") (pinfunction "P$1_P$1") (pintype "bidirectional"))
      (node (ref "S173") (pin "P$2") (pinfunction "P$2_P$2") (pintype "bidirectional"))
      (node (ref "S173") (pin "P$3") (pinfunction "P$3_P$3") (pintype "bidirectional"))
      (node (ref "S173") (pin "P$4") (pinfunction "P$4_P$4") (pintype "bidirectional"))
      (node (ref "S173") (pin "P$5") (pinfunction "P$5_P$5") (pintype "bidirectional"))
    )
    (net (code "185") (name "Net-(S174-PadP$1)") (class "Default")
      (node (ref "S174") (pin "P$1") (pinfunction "P$1_P$1") (pintype "bidirectional"))
      (node (ref "S174") (pin "P$2") (pinfunction "P$2_P$2") (pintype "bidirectional"))
      (node (ref "S174") (pin "P$3") (pinfunction "P$3_P$3") (pintype "bidirectional"))
      (node (ref "S174") (pin "P$4") (pinfunction "P$4_P$4") (pintype "bidirectional"))
      (node (ref "S174") (pin "P$5") (pinfunction "P$5_P$5") (pintype "bidirectional"))
    )
    (net (code "186") (name "Net-(S175-PadP$1)") (class "Default")
      (node (ref "S175") (pin "P$1") (pinfunction "P$1_P$1") (pintype "bidirectional"))
      (node (ref "S175") (pin "P$2") (pinfunction "P$2_P$2") (pintype "bidirectional"))
      (node (ref "S175") (pin "P$3") (pinfunction "P$3_P$3") (pintype "bidirectional"))
      (node (ref "S175") (pin "P$4") (pinfunction "P$4_P$4") (pintype "bidirectional"))
      (node (ref "S175") (pin "P$5") (pinfunction "P$5_P$5") (pintype "bidirectional"))
    )
    (net (code "187") (name "Net-(S176-PadP$1)") (class "Default")
      (node (ref "S176") (pin "P$1") (pinfunction "P$1_P$1") (pintype "bidirectional"))
      (node (ref "S176") (pin "P$2") (pinfunction "P$2_P$2") (pintype "bidirectional"))
      (node (ref "S176") (pin "P$3") (pinfunction "P$3_P$3") (pintype "bidirectional"))
      (node (ref "S176") (pin "P$4") (pinfunction "P$4_P$4") (pintype "bidirectional"))
      (node (ref "S176") (pin "P$5") (pinfunction "P$5_P$5") (pintype "bidirectional"))
    )
    (net (code "188") (name "Net-(S177-PadP$1)") (class "Default")
      (node (ref "S177") (pin "P$1") (pinfunction "P$1_P$1") (pintype "bidirectional"))
      (node (ref "S177") (pin "P$2") (pinfunction "P$2_P$2") (pintype "bidirectional"))
      (node (ref "S177") (pin "P$3") (pinfunction "P$3_P$3") (pintype "bidirectional"))
      (node (ref "S177") (pin "P$4") (pinfunction "P$4_P$4") (pintype "bidirectional"))
      (node (ref "S177") (pin "P$5") (pinfunction "P$5_P$5") (pintype "bidirectional"))
    )
    (net (code "189") (name "Net-(S178-PadP$1)") (class "Default")
      (node (ref "S178") (pin "P$1") (pinfunction "P$1_P$1") (pintype "bidirectional"))
      (node (ref "S178") (pin "P$2") (pinfunction "P$2_P$2") (pintype "bidirectional"))
      (node (ref "S178") (pin "P$3") (pinfunction "P$3_P$3") (pintype "bidirectional"))
      (node (ref "S178") (pin "P$4") (pinfunction "P$4_P$4") (pintype "bidirectional"))
      (node (ref "S178") (pin "P$5") (pinfunction "P$5_P$5") (pintype "bidirectional"))
    )
    (net (code "190") (name "Net-(S179-PadP$1)") (class "Default")
      (node (ref "S179") (pin "P$1") (pinfunction "P$1_P$1") (pintype "bidirectional"))
      (node (ref "S179") (pin "P$2") (pinfunction "P$2_P$2") (pintype "bidirectional"))
      (node (ref "S179") (pin "P$3") (pinfunction "P$3_P$3") (pintype "bidirectional"))
      (node (ref "S179") (pin "P$4") (pinfunction "P$4_P$4") (pintype "bidirectional"))
      (node (ref "S179") (pin "P$5") (pinfunction "P$5_P$5") (pintype "bidirectional"))
    )
    (net (code "191") (name "Net-(S180-PadP$1)") (class "Default")
      (node (ref "S180") (pin "P$1") (pinfunction "P$1_P$1") (pintype "bidirectional"))
      (node (ref "S180") (pin "P$2") (pinfunction "P$2_P$2") (pintype "bidirectional"))
      (node (ref "S180") (pin "P$3") (pinfunction "P$3_P$3") (pintype "bidirectional"))
      (node (ref "S180") (pin "P$4") (pinfunction "P$4_P$4") (pintype "bidirectional"))
      (node (ref "S180") (pin "P$5") (pinfunction "P$5_P$5") (pintype "bidirectional"))
    )
    (net (code "192") (name "Net-(S181-PadP$1)") (class "Default")
      (node (ref "S181") (pin "P$1") (pinfunction "P$1_P$1") (pintype "bidirectional"))
      (node (ref "S181") (pin "P$2") (pinfunction "P$2_P$2") (pintype "bidirectional"))
      (node (ref "S181") (pin "P$3") (pinfunction "P$3_P$3") (pintype "bidirectional"))
      (node (ref "S181") (pin "P$4") (pinfunction "P$4_P$4") (pintype "bidirectional"))
      (node (ref "S181") (pin "P$5") (pinfunction "P$5_P$5") (pintype "bidirectional"))
    )
    (net (code "193") (name "Net-(S182-PadP$1)") (class "Default")
      (node (ref "S182") (pin "P$1") (pinfunction "P$1_P$1") (pintype "bidirectional"))
      (node (ref "S182") (pin "P$2") (pinfunction "P$2_P$2") (pintype "bidirectional"))
      (node (ref "S182") (pin "P$3") (pinfunction "P$3_P$3") (pintype "bidirectional"))
      (node (ref "S182") (pin "P$4") (pinfunction "P$4_P$4") (pintype "bidirectional"))
      (node (ref "S182") (pin "P$5") (pinfunction "P$5_P$5") (pintype "bidirectional"))
    )
    (net (code "194") (name "Net-(S183-PadP$1)") (class "Default")
      (node (ref "S183") (pin "P$1") (pinfunction "P$1_P$1") (pintype "bidirectional"))
      (node (ref "S183") (pin "P$2") (pinfunction "P$2_P$2") (pintype "bidirectional"))
      (node (ref "S183") (pin "P$3") (pinfunction "P$3_P$3") (pintype "bidirectional"))
      (node (ref "S183") (pin "P$4") (pinfunction "P$4_P$4") (pintype "bidirectional"))
      (node (ref "S183") (pin "P$5") (pinfunction "P$5_P$5") (pintype "bidirectional"))
    )
    (net (code "195") (name "Net-(S184-PadP$1)") (class "Default")
      (node (ref "S184") (pin "P$1") (pinfunction "P$1_P$1") (pintype "bidirectional"))
      (node (ref "S184") (pin "P$2") (pinfunction "P$2_P$2") (pintype "bidirectional"))
      (node (ref "S184") (pin "P$3") (pinfunction "P$3_P$3") (pintype "bidirectional"))
      (node (ref "S184") (pin "P$4") (pinfunction "P$4_P$4") (pintype "bidirectional"))
      (node (ref "S184") (pin "P$5") (pinfunction "P$5_P$5") (pintype "bidirectional"))
    )
    (net (code "196") (name "Net-(S185-PadP$1)") (class "Default")
      (node (ref "S185") (pin "P$1") (pinfunction "P$1_P$1") (pintype "bidirectional"))
      (node (ref "S185") (pin "P$2") (pinfunction "P$2_P$2") (pintype "bidirectional"))
      (node (ref "S185") (pin "P$3") (pinfunction "P$3_P$3") (pintype "bidirectional"))
      (node (ref "S185") (pin "P$4") (pinfunction "P$4_P$4") (pintype "bidirectional"))
      (node (ref "S185") (pin "P$5") (pinfunction "P$5_P$5") (pintype "bidirectional"))
    )
    (net (code "197") (name "Net-(S186-PadP$1)") (class "Default")
      (node (ref "S186") (pin "P$1") (pinfunction "P$1_P$1") (pintype "bidirectional"))
      (node (ref "S186") (pin "P$2") (pinfunction "P$2_P$2") (pintype "bidirectional"))
      (node (ref "S186") (pin "P$3") (pinfunction "P$3_P$3") (pintype "bidirectional"))
      (node (ref "S186") (pin "P$4") (pinfunction "P$4_P$4") (pintype "bidirectional"))
      (node (ref "S186") (pin "P$5") (pinfunction "P$5_P$5") (pintype "bidirectional"))
    )
    (net (code "198") (name "Net-(S187-PadP$1)") (class "Default")
      (node (ref "S187") (pin "P$1") (pinfunction "P$1_P$1") (pintype "bidirectional"))
      (node (ref "S187") (pin "P$2") (pinfunction "P$2_P$2") (pintype "bidirectional"))
      (node (ref "S187") (pin "P$3") (pinfunction "P$3_P$3") (pintype "bidirectional"))
      (node (ref "S187") (pin "P$4") (pinfunction "P$4_P$4") (pintype "bidirectional"))
      (node (ref "S187") (pin "P$5") (pinfunction "P$5_P$5") (pintype "bidirectional"))
    )
    (net (code "199") (name "Net-(S188-PadP$1)") (class "Default")
      (node (ref "S188") (pin "P$1") (pinfunction "P$1_P$1") (pintype "bidirectional"))
      (node (ref "S188") (pin "P$2") (pinfunction "P$2_P$2") (pintype "bidirectional"))
      (node (ref "S188") (pin "P$3") (pinfunction "P$3_P$3") (pintype "bidirectional"))
      (node (ref "S188") (pin "P$4") (pinfunction "P$4_P$4") (pintype "bidirectional"))
      (node (ref "S188") (pin "P$5") (pinfunction "P$5_P$5") (pintype "bidirectional"))
    )
    (net (code "200") (name "Net-(S189-PadP$1)") (class "Default")
      (node (ref "S189") (pin "P$1") (pinfunction "P$1_P$1") (pintype "bidirectional"))
      (node (ref "S189") (pin "P$2") (pinfunction "P$2_P$2") (pintype "bidirectional"))
      (node (ref "S189") (pin "P$3") (pinfunction "P$3_P$3") (pintype "bidirectional"))
      (node (ref "S189") (pin "P$4") (pinfunction "P$4_P$4") (pintype "bidirectional"))
      (node (ref "S189") (pin "P$5") (pinfunction "P$5_P$5") (pintype "bidirectional"))
    )
    (net (code "201") (name "Net-(S210-PadP$1)") (class "Default")
      (node (ref "S210") (pin "P$1") (pinfunction "P$1_P$1") (pintype "bidirectional"))
      (node (ref "S210") (pin "P$2") (pinfunction "P$2_P$2") (pintype "bidirectional"))
      (node (ref "S210") (pin "P$3") (pinfunction "P$3_P$3") (pintype "bidirectional"))
      (node (ref "S210") (pin "P$4") (pinfunction "P$4_P$4") (pintype "bidirectional"))
      (node (ref "S210") (pin "P$5") (pinfunction "P$5_P$5") (pintype "bidirectional"))
    )
    (net (code "202") (name "Net-(S211-PadP$1)") (class "Default")
      (node (ref "S211") (pin "P$1") (pinfunction "P$1_P$1") (pintype "bidirectional"))
      (node (ref "S211") (pin "P$2") (pinfunction "P$2_P$2") (pintype "bidirectional"))
      (node (ref "S211") (pin "P$3") (pinfunction "P$3_P$3") (pintype "bidirectional"))
      (node (ref "S211") (pin "P$4") (pinfunction "P$4_P$4") (pintype "bidirectional"))
      (node (ref "S211") (pin "P$5") (pinfunction "P$5_P$5") (pintype "bidirectional"))
    )
    (net (code "203") (name "Net-(S212-PadP$1)") (class "Default")
      (node (ref "S212") (pin "P$1") (pinfunction "P$1_P$1") (pintype "bidirectional"))
      (node (ref "S212") (pin "P$2") (pinfunction "P$2_P$2") (pintype "bidirectional"))
      (node (ref "S212") (pin "P$3") (pinfunction "P$3_P$3") (pintype "bidirectional"))
      (node (ref "S212") (pin "P$4") (pinfunction "P$4_P$4") (pintype "bidirectional"))
      (node (ref "S212") (pin "P$5") (pinfunction "P$5_P$5") (pintype "bidirectional"))
    )
    (net (code "204") (name "Net-(S213-PadP$1)") (class "Default")
      (node (ref "S213") (pin "P$1") (pinfunction "P$1_P$1") (pintype "bidirectional"))
      (node (ref "S213") (pin "P$2") (pinfunction "P$2_P$2") (pintype "bidirectional"))
      (node (ref "S213") (pin "P$3") (pinfunction "P$3_P$3") (pintype "bidirectional"))
      (node (ref "S213") (pin "P$4") (pinfunction "P$4_P$4") (pintype "bidirectional"))
      (node (ref "S213") (pin "P$5") (pinfunction "P$5_P$5") (pintype "bidirectional"))
    )
    (net (code "205") (name "Net-(S214-PadP$1)") (class "Default")
      (node (ref "S214") (pin "P$1") (pinfunction "P$1_P$1") (pintype "bidirectional"))
      (node (ref "S214") (pin "P$2") (pinfunction "P$2_P$2") (pintype "bidirectional"))
      (node (ref "S214") (pin "P$3") (pinfunction "P$3_P$3") (pintype "bidirectional"))
      (node (ref "S214") (pin "P$4") (pinfunction "P$4_P$4") (pintype "bidirectional"))
      (node (ref "S214") (pin "P$5") (pinfunction "P$5_P$5") (pintype "bidirectional"))
    )
    (net (code "206") (name "Net-(S215-PadP$1)") (class "Default")
      (node (ref "S215") (pin "P$1") (pinfunction "P$1_P$1") (pintype "bidirectional"))
      (node (ref "S215") (pin "P$2") (pinfunction "P$2_P$2") (pintype "bidirectional"))
      (node (ref "S215") (pin "P$3") (pinfunction "P$3_P$3") (pintype "bidirectional"))
      (node (ref "S215") (pin "P$4") (pinfunction "P$4_P$4") (pintype "bidirectional"))
      (node (ref "S215") (pin "P$5") (pinfunction "P$5_P$5") (pintype "bidirectional"))
    )
    (net (code "207") (name "Net-(S216-PadP$1)") (class "Default")
      (node (ref "S216") (pin "P$1") (pinfunction "P$1_P$1") (pintype "bidirectional"))
      (node (ref "S216") (pin "P$2") (pinfunction "P$2_P$2") (pintype "bidirectional"))
      (node (ref "S216") (pin "P$3") (pinfunction "P$3_P$3") (pintype "bidirectional"))
      (node (ref "S216") (pin "P$4") (pinfunction "P$4_P$4") (pintype "bidirectional"))
      (node (ref "S216") (pin "P$5") (pinfunction "P$5_P$5") (pintype "bidirectional"))
    )
    (net (code "208") (name "Net-(S217-PadP$1)") (class "Default")
      (node (ref "S217") (pin "P$1") (pinfunction "P$1_P$1") (pintype "bidirectional"))
      (node (ref "S217") (pin "P$2") (pinfunction "P$2_P$2") (pintype "bidirectional"))
      (node (ref "S217") (pin "P$3") (pinfunction "P$3_P$3") (pintype "bidirectional"))
      (node (ref "S217") (pin "P$4") (pinfunction "P$4_P$4") (pintype "bidirectional"))
      (node (ref "S217") (pin "P$5") (pinfunction "P$5_P$5") (pintype "bidirectional"))
    )
    (net (code "209") (name "Net-(S218-PadP$1)") (class "Default")
      (node (ref "S218") (pin "P$1") (pinfunction "P$1_P$1") (pintype "bidirectional"))
      (node (ref "S218") (pin "P$2") (pinfunction "P$2_P$2") (pintype "bidirectional"))
      (node (ref "S218") (pin "P$3") (pinfunction "P$3_P$3") (pintype "bidirectional"))
      (node (ref "S218") (pin "P$4") (pinfunction "P$4_P$4") (pintype "bidirectional"))
      (node (ref "S218") (pin "P$5") (pinfunction "P$5_P$5") (pintype "bidirectional"))
    )
    (net (code "210") (name "Net-(S219-PadP$1)") (class "Default")
      (node (ref "S219") (pin "P$1") (pinfunction "P$1_P$1") (pintype "bidirectional"))
      (node (ref "S219") (pin "P$2") (pinfunction "P$2_P$2") (pintype "bidirectional"))
      (node (ref "S219") (pin "P$3") (pinfunction "P$3_P$3") (pintype "bidirectional"))
      (node (ref "S219") (pin "P$4") (pinfunction "P$4_P$4") (pintype "bidirectional"))
      (node (ref "S219") (pin "P$5") (pinfunction "P$5_P$5") (pintype "bidirectional"))
    )
    (net (code "211") (name "Net-(S220-PadP$1)") (class "Default")
      (node (ref "S220") (pin "P$1") (pinfunction "P$1_P$1") (pintype "bidirectional"))
      (node (ref "S220") (pin "P$2") (pinfunction "P$2_P$2") (pintype "bidirectional"))
      (node (ref "S220") (pin "P$3") (pinfunction "P$3_P$3") (pintype "bidirectional"))
      (node (ref "S220") (pin "P$4") (pinfunction "P$4_P$4") (pintype "bidirectional"))
      (node (ref "S220") (pin "P$5") (pinfunction "P$5_P$5") (pintype "bidirectional"))
    )
    (net (code "212") (name "Net-(S221-PadP$1)") (class "Default")
      (node (ref "S221") (pin "P$1") (pinfunction "P$1_P$1") (pintype "bidirectional"))
      (node (ref "S221") (pin "P$2") (pinfunction "P$2_P$2") (pintype "bidirectional"))
      (node (ref "S221") (pin "P$3") (pinfunction "P$3_P$3") (pintype "bidirectional"))
      (node (ref "S221") (pin "P$4") (pinfunction "P$4_P$4") (pintype "bidirectional"))
      (node (ref "S221") (pin "P$5") (pinfunction "P$5_P$5") (pintype "bidirectional"))
    )
    (net (code "213") (name "Net-(S222-PadP$1)") (class "Default")
      (node (ref "S222") (pin "P$1") (pinfunction "P$1_P$1") (pintype "bidirectional"))
      (node (ref "S222") (pin "P$2") (pinfunction "P$2_P$2") (pintype "bidirectional"))
      (node (ref "S222") (pin "P$3") (pinfunction "P$3_P$3") (pintype "bidirectional"))
      (node (ref "S222") (pin "P$4") (pinfunction "P$4_P$4") (pintype "bidirectional"))
      (node (ref "S222") (pin "P$5") (pinfunction "P$5_P$5") (pintype "bidirectional"))
    )
    (net (code "214") (name "Net-(S223-PadP$1)") (class "Default")
      (node (ref "S223") (pin "P$1") (pinfunction "P$1_P$1") (pintype "bidirectional"))
      (node (ref "S223") (pin "P$2") (pinfunction "P$2_P$2") (pintype "bidirectional"))
      (node (ref "S223") (pin "P$3") (pinfunction "P$3_P$3") (pintype "bidirectional"))
      (node (ref "S223") (pin "P$4") (pinfunction "P$4_P$4") (pintype "bidirectional"))
      (node (ref "S223") (pin "P$5") (pinfunction "P$5_P$5") (pintype "bidirectional"))
    )
    (net (code "215") (name "Net-(S224-PadP$1)") (class "Default")
      (node (ref "S224") (pin "P$1") (pinfunction "P$1_P$1") (pintype "bidirectional"))
      (node (ref "S224") (pin "P$2") (pinfunction "P$2_P$2") (pintype "bidirectional"))
      (node (ref "S224") (pin "P$3") (pinfunction "P$3_P$3") (pintype "bidirectional"))
      (node (ref "S224") (pin "P$4") (pinfunction "P$4_P$4") (pintype "bidirectional"))
      (node (ref "S224") (pin "P$5") (pinfunction "P$5_P$5") (pintype "bidirectional"))
    )
    (net (code "216") (name "Net-(S225-PadP$1)") (class "Default")
      (node (ref "S225") (pin "P$1") (pinfunction "P$1_P$1") (pintype "bidirectional"))
      (node (ref "S225") (pin "P$2") (pinfunction "P$2_P$2") (pintype "bidirectional"))
      (node (ref "S225") (pin "P$3") (pinfunction "P$3_P$3") (pintype "bidirectional"))
      (node (ref "S225") (pin "P$4") (pinfunction "P$4_P$4") (pintype "bidirectional"))
      (node (ref "S225") (pin "P$5") (pinfunction "P$5_P$5") (pintype "bidirectional"))
    )
    (net (code "217") (name "Net-(S226-PadP$1)") (class "Default")
      (node (ref "S226") (pin "P$1") (pinfunction "P$1_P$1") (pintype "bidirectional"))
      (node (ref "S226") (pin "P$2") (pinfunction "P$2_P$2") (pintype "bidirectional"))
      (node (ref "S226") (pin "P$3") (pinfunction "P$3_P$3") (pintype "bidirectional"))
      (node (ref "S226") (pin "P$4") (pinfunction "P$4_P$4") (pintype "bidirectional"))
      (node (ref "S226") (pin "P$5") (pinfunction "P$5_P$5") (pintype "bidirectional"))
    )
    (net (code "218") (name "Net-(SV2-Pad7)") (class "Default")
      (node (ref "SV2") (pin "7") (pinfunction "7_7") (pintype "passive"))
      (node (ref "SV2") (pin "8") (pinfunction "8_8") (pintype "passive"))
    )
    (net (code "219") (name "Net-(SV2-Pad10)") (class "Default")
      (node (ref "SV2") (pin "10") (pinfunction "10_10") (pintype "passive"))
      (node (ref "SV2") (pin "9") (pinfunction "9_9") (pintype "passive"))
    )
    (net (code "220") (name "Net-(SV2-Pad11)") (class "Default")
      (node (ref "SV2") (pin "11") (pinfunction "11_11") (pintype "passive"))
      (node (ref "SV2") (pin "12") (pinfunction "12_12") (pintype "passive"))
    )
    (net (code "221") (name "Net-(SV2-Pad15)") (class "Default")
      (node (ref "SV2") (pin "15") (pinfunction "15_15") (pintype "passive"))
      (node (ref "SV2") (pin "16") (pinfunction "16_16") (pintype "passive"))
    )
    (net (code "222") (name "Net-(SV2-Pad17)") (class "Default")
      (node (ref "SV2") (pin "17") (pinfunction "17_17") (pintype "passive"))
      (node (ref "SV2") (pin "18") (pinfunction "18_18") (pintype "passive"))
    )
    (net (code "223") (name "Net-(SV2-Pad21)") (class "Default")
      (node (ref "SV2") (pin "21") (pinfunction "21_21") (pintype "passive"))
      (node (ref "SV2") (pin "22") (pinfunction "22_22") (pintype "passive"))
    )
    (net (code "224") (name "Net-(SV2-Pad23)") (class "Default")
      (node (ref "SV2") (pin "23") (pinfunction "23_23") (pintype "passive"))
      (node (ref "SV2") (pin "24") (pinfunction "24_24") (pintype "passive"))
    )
    (net (code "225") (name "Net-(SV2-Pad25)") (class "Default")
      (node (ref "SV2") (pin "25") (pinfunction "25_25") (pintype "passive"))
      (node (ref "SV2") (pin "26") (pinfunction "26_26") (pintype "passive"))
    )
    (net (code "226") (name "Net-(SV2-Pad27)") (class "Default")
      (node (ref "SV2") (pin "27") (pinfunction "27_27") (pintype "passive"))
      (node (ref "SV2") (pin "28") (pinfunction "28_28") (pintype "passive"))
    )
    (net (code "227") (name "Net-(SV2-Pad31)") (class "Default")
      (node (ref "SV2") (pin "31") (pinfunction "31_31") (pintype "passive"))
      (node (ref "SV2") (pin "32") (pinfunction "32_32") (pintype "passive"))
    )
    (net (code "228") (name "Net-(SV2-Pad35)") (class "Default")
      (node (ref "SV2") (pin "35") (pinfunction "35_35") (pintype "passive"))
      (node (ref "SV2") (pin "36") (pinfunction "36_36") (pintype "passive"))
    )
    (net (code "229") (name "Net-(SV2-Pad37)") (class "Default")
      (node (ref "SV2") (pin "37") (pinfunction "37_37") (pintype "passive"))
      (node (ref "SV2") (pin "38") (pinfunction "38_38") (pintype "passive"))
    )
    (net (code "230") (name "Net-(SV2-Pad39)") (class "Default")
      (node (ref "SV2") (pin "39") (pinfunction "39_39") (pintype "passive"))
      (node (ref "SV2") (pin "40") (pinfunction "40_40") (pintype "passive"))
    )
    (net (code "231") (name "Net-(SV4-Pad1)") (class "Default")
      (node (ref "SV4") (pin "1") (pinfunction "1_1") (pintype "passive"))
      (node (ref "SV4") (pin "2") (pinfunction "2_2") (pintype "passive"))
    )
    (net (code "232") (name "Net-(SV4-Pad3)") (class "Default")
      (node (ref "SV4") (pin "3") (pinfunction "3_3") (pintype "passive"))
      (node (ref "SV4") (pin "4") (pinfunction "4_4") (pintype "passive"))
    )
    (net (code "233") (name "Net-(SV4-Pad5)") (class "Default")
      (node (ref "SV4") (pin "5") (pinfunction "5_5") (pintype "passive"))
      (node (ref "SV4") (pin "6") (pinfunction "6_6") (pintype "passive"))
    )
    (net (code "234") (name "Net-(SV4-Pad7)") (class "Default")
      (node (ref "SV4") (pin "7") (pinfunction "7_7") (pintype "passive"))
      (node (ref "SV4") (pin "8") (pinfunction "8_8") (pintype "passive"))
    )
    (net (code "235") (name "Net-(SV4-Pad11)") (class "Default")
      (node (ref "SV4") (pin "11") (pinfunction "11_11") (pintype "passive"))
      (node (ref "SV4") (pin "12") (pinfunction "12_12") (pintype "passive"))
    )
    (net (code "236") (name "Net-(SV4-Pad13)") (class "Default")
      (node (ref "SV4") (pin "13") (pinfunction "13_13") (pintype "passive"))
      (node (ref "SV4") (pin "14") (pinfunction "14_14") (pintype "passive"))
    )
    (net (code "237") (name "Net-(SV4-Pad15)") (class "Default")
      (node (ref "SV4") (pin "15") (pinfunction "15_15") (pintype "passive"))
      (node (ref "SV4") (pin "16") (pinfunction "16_16") (pintype "passive"))
    )
    (net (code "238") (name "Net-(SV4-Pad17)") (class "Default")
      (node (ref "SV4") (pin "17") (pinfunction "17_17") (pintype "passive"))
      (node (ref "SV4") (pin "18") (pinfunction "18_18") (pintype "passive"))
    )
    (net (code "239") (name "Net-(SV4-Pad19)") (class "Default")
      (node (ref "SV4") (pin "19") (pinfunction "19_19") (pintype "passive"))
      (node (ref "SV4") (pin "20") (pinfunction "20_20") (pintype "passive"))
    )
    (net (code "240") (name "Net-(SV4-Pad21)") (class "Default")
      (node (ref "SV4") (pin "21") (pinfunction "21_21") (pintype "passive"))
      (node (ref "SV4") (pin "22") (pinfunction "22_22") (pintype "passive"))
    )
    (net (code "241") (name "Net-(SV4-Pad23)") (class "Default")
      (node (ref "SV4") (pin "23") (pinfunction "23_23") (pintype "passive"))
      (node (ref "SV4") (pin "24") (pinfunction "24_24") (pintype "passive"))
    )
    (net (code "242") (name "Net-(SV4-Pad27)") (class "Default")
      (node (ref "SV4") (pin "27") (pinfunction "27_27") (pintype "passive"))
      (node (ref "SV4") (pin "28") (pinfunction "28_28") (pintype "passive"))
    )
    (net (code "243") (name "Net-(SV4-Pad29)") (class "Default")
      (node (ref "SV4") (pin "29") (pinfunction "29_29") (pintype "passive"))
      (node (ref "SV4") (pin "30") (pinfunction "30_30") (pintype "passive"))
    )
    (net (code "244") (name "Net-(SV4-Pad31)") (class "Default")
      (node (ref "SV4") (pin "31") (pinfunction "31_31") (pintype "passive"))
      (node (ref "SV4") (pin "32") (pinfunction "32_32") (pintype "passive"))
    )
    (net (code "245") (name "Net-(SV4-Pad33)") (class "Default")
      (node (ref "SV4") (pin "33") (pinfunction "33_33") (pintype "passive"))
      (node (ref "SV4") (pin "34") (pinfunction "34_34") (pintype "passive"))
    )
    (net (code "246") (name "Net-(SV4-Pad35)") (class "Default")
      (node (ref "SV4") (pin "35") (pinfunction "35_35") (pintype "passive"))
      (node (ref "SV4") (pin "36") (pinfunction "36_36") (pintype "passive"))
    )
    (net (code "247") (name "Net-(SV4-Pad37)") (class "Default")
      (node (ref "SV4") (pin "37") (pinfunction "37_37") (pintype "passive"))
      (node (ref "SV4") (pin "38") (pinfunction "38_38") (pintype "passive"))
    )
    (net (code "248") (name "Net-(SV5-Pad1)") (class "Default")
      (node (ref "SV5") (pin "1") (pinfunction "1_1") (pintype "passive"))
      (node (ref "SV5") (pin "2") (pinfunction "2_2") (pintype "passive"))
    )
    (net (code "249") (name "Net-(SV5-Pad3)") (class "Default")
      (node (ref "SV5") (pin "3") (pinfunction "3_3") (pintype "passive"))
      (node (ref "SV5") (pin "4") (pinfunction "4_4") (pintype "passive"))
    )
    (net (code "250") (name "Net-(SV5-Pad5)") (class "Default")
      (node (ref "SV5") (pin "5") (pinfunction "5_5") (pintype "passive"))
      (node (ref "SV5") (pin "6") (pinfunction "6_6") (pintype "passive"))
    )
    (net (code "251") (name "Net-(SV6-Pad5)") (class "Default")
      (node (ref "SV6") (pin "5") (pinfunction "5_5") (pintype "passive"))
      (node (ref "SV6") (pin "6") (pinfunction "6_6") (pintype "passive"))
    )
    (net (code "252") (name "Net-(SV16-Pad3)") (class "Default")
      (node (ref "SV16") (pin "3") (pinfunction "3_3") (pintype "passive"))
      (node (ref "SV16") (pin "4") (pinfunction "4_4") (pintype "passive"))
      (node (ref "SV18") (pin "2") (pinfunction "2_2") (pintype "passive"))
    )
    (net (code "253") (name "Net-(SV16-Pad5)") (class "Default")
      (node (ref "SV16") (pin "5") (pinfunction "5_5") (pintype "passive"))
      (node (ref "SV16") (pin "6") (pinfunction "6_6") (pintype "passive"))
      (node (ref "SV18") (pin "3") (pinfunction "3_3") (pintype "passive"))
    )
    (net (code "254") (name "Net-(SV16-Pad7)") (class "Default")
      (node (ref "SV16") (pin "7") (pinfunction "7_7") (pintype "passive"))
      (node (ref "SV16") (pin "8") (pinfunction "8_8") (pintype "passive"))
      (node (ref "SV18") (pin "4") (pinfunction "4_4") (pintype "passive"))
    )
    (net (code "255") (name "Net-(SV16-Pad10)") (class "Default")
      (node (ref "SV16") (pin "10") (pinfunction "10_10") (pintype "passive"))
      (node (ref "SV16") (pin "9") (pinfunction "9_9") (pintype "passive"))
      (node (ref "SV18") (pin "5") (pinfunction "5_5") (pintype "passive"))
    )
    (net (code "256") (name "Net-(SV16-Pad11)") (class "Default")
      (node (ref "SV16") (pin "11") (pinfunction "11_11") (pintype "passive"))
      (node (ref "SV16") (pin "12") (pinfunction "12_12") (pintype "passive"))
      (node (ref "SV18") (pin "6") (pinfunction "6_6") (pintype "passive"))
    )
    (net (code "257") (name "Net-(SV16-Pad13)") (class "Default")
      (node (ref "SV16") (pin "13") (pinfunction "13_13") (pintype "passive"))
      (node (ref "SV16") (pin "14") (pinfunction "14_14") (pintype "passive"))
      (node (ref "SV18") (pin "7") (pinfunction "7_7") (pintype "passive"))
    )
    (net (code "258") (name "Net-(SV16-Pad15)") (class "Default")
      (node (ref "SV16") (pin "15") (pinfunction "15_15") (pintype "passive"))
      (node (ref "SV16") (pin "16") (pinfunction "16_16") (pintype "passive"))
      (node (ref "SV18") (pin "8") (pinfunction "8_8") (pintype "passive"))
    )
    (net (code "259") (name "Net-(SV16-Pad19)") (class "Default")
      (node (ref "SV16") (pin "19") (pinfunction "19_19") (pintype "passive"))
      (node (ref "SV16") (pin "20") (pinfunction "20_20") (pintype "passive"))
      (node (ref "SV18") (pin "10") (pinfunction "10_10") (pintype "passive"))
    )
    (net (code "260") (name "Net-(SV17-Pad3)") (class "Default")
      (node (ref "SV17") (pin "3") (pinfunction "3_3") (pintype "passive"))
      (node (ref "SV17") (pin "4") (pinfunction "4_4") (pintype "passive"))
      (node (ref "SV19") (pin "2") (pinfunction "2_2") (pintype "passive"))
    )
    (net (code "261") (name "Net-(SV17-Pad5)") (class "Default")
      (node (ref "SV17") (pin "5") (pinfunction "5_5") (pintype "passive"))
      (node (ref "SV17") (pin "6") (pinfunction "6_6") (pintype "passive"))
      (node (ref "SV19") (pin "3") (pinfunction "3_3") (pintype "passive"))
    )
    (net (code "262") (name "Net-(SV17-Pad15)") (class "Default")
      (node (ref "SV17") (pin "15") (pinfunction "15_15") (pintype "passive"))
      (node (ref "SV17") (pin "16") (pinfunction "16_16") (pintype "passive"))
      (node (ref "SV19") (pin "8") (pinfunction "8_8") (pintype "passive"))
    )
    (net (code "263") (name "Net-(SV17-Pad17)") (class "Default")
      (node (ref "SV17") (pin "17") (pinfunction "17_17") (pintype "passive"))
      (node (ref "SV17") (pin "18") (pinfunction "18_18") (pintype "passive"))
      (node (ref "SV19") (pin "9") (pinfunction "9_9") (pintype "passive"))
    )
    (net (code "264") (name "Net-(SV17-Pad19)") (class "Default")
      (node (ref "SV17") (pin "19") (pinfunction "19_19") (pintype "passive"))
      (node (ref "SV17") (pin "20") (pinfunction "20_20") (pintype "passive"))
      (node (ref "SV19") (pin "10") (pinfunction "10_10") (pintype "passive"))
    )
    (net (code "265") (name "Net-(T1-B)") (class "Default")
      (node (ref "R1") (pin "2") (pinfunction "2_2") (pintype "passive"))
      (node (ref "T1") (pin "1") (pinfunction "B_1") (pintype "passive"))
    )
    (net (code "266") (name "Net-(T1-C)") (class "Default")
      (node (ref "J4") (pin "P$1") (pinfunction "P$1_P$1") (pintype "bidirectional"))
      (node (ref "J4") (pin "P$2") (pinfunction "P$2_P$2") (pintype "bidirectional"))
      (node (ref "J4") (pin "P$3") (pinfunction "P$3_P$3") (pintype "bidirectional"))
      (node (ref "T1") (pin "2") (pinfunction "C_2") (pintype "passive"))
    )
    (net (code "267") (name "Net-(T2-B)") (class "Default")
      (node (ref "R2") (pin "2") (pinfunction "2_2") (pintype "passive"))
      (node (ref "T2") (pin "1") (pinfunction "B_1") (pintype "passive"))
    )
    (net (code "268") (name "Net-(T2-C)") (class "Default")
      (node (ref "J23") (pin "P$1") (pinfunction "P$1_P$1") (pintype "bidirectional"))
      (node (ref "J23") (pin "P$2") (pinfunction "P$2_P$2") (pintype "bidirectional"))
      (node (ref "J23") (pin "P$3") (pinfunction "P$3_P$3") (pintype "bidirectional"))
      (node (ref "T2") (pin "2") (pinfunction "C_2") (pintype "passive"))
    )
    (net (code "269") (name "Net-(U$1-P3_SCLK)") (class "Default")
      (node (ref "J125") (pin "P$1") (pinfunction "P$1_P$1") (pintype "bidirectional"))
      (node (ref "J125") (pin "P$2") (pinfunction "P$2_P$2") (pintype "bidirectional"))
      (node (ref "J125") (pin "P$3") (pinfunction "P$3_P$3") (pintype "bidirectional"))
      (node (ref "U$1") (pin "3") (pinfunction "P3_SCLK_3") (pintype "bidirectional"))
    )
    (net (code "270") (name "Net-(U$1-P4_SDA{slash}SPIMOSI)") (class "Default")
      (node (ref "J126") (pin "P$1") (pinfunction "P$1_P$1") (pintype "bidirectional"))
      (node (ref "J126") (pin "P$2") (pinfunction "P$2_P$2") (pintype "bidirectional"))
      (node (ref "J126") (pin "P$3") (pinfunction "P$3_P$3") (pintype "bidirectional"))
      (node (ref "U$1") (pin "4") (pinfunction "P4_SDA/SPIMOSI_4") (pintype "bidirectional"))
    )
    (net (code "271") (name "Net-(U$1-P5_EDA{slash}AUX-DA)") (class "Default")
      (node (ref "J127") (pin "P$1") (pinfunction "P$1_P$1") (pintype "bidirectional"))
      (node (ref "J127") (pin "P$2") (pinfunction "P$2_P$2") (pintype "bidirectional"))
      (node (ref "J127") (pin "P$3") (pinfunction "P$3_P$3") (pintype "bidirectional"))
      (node (ref "U$1") (pin "5") (pinfunction "P5_EDA/AUX-DA_5") (pintype "bidirectional"))
    )
    (net (code "272") (name "Net-(U$1-P6_ECL{slash}AUX-CL)") (class "Default")
      (node (ref "J128") (pin "P$1") (pinfunction "P$1_P$1") (pintype "bidirectional"))
      (node (ref "J128") (pin "P$2") (pinfunction "P$2_P$2") (pintype "bidirectional"))
      (node (ref "J128") (pin "P$3") (pinfunction "P$3_P$3") (pintype "bidirectional"))
      (node (ref "U$1") (pin "6") (pinfunction "P6_ECL/AUX-CL_6") (pintype "bidirectional"))
    )
    (net (code "273") (name "Net-(U$1-P7_ADO{slash}SPIMISO)") (class "Default")
      (node (ref "J129") (pin "P$1") (pinfunction "P$1_P$1") (pintype "bidirectional"))
      (node (ref "J129") (pin "P$2") (pinfunction "P$2_P$2") (pintype "bidirectional"))
      (node (ref "J129") (pin "P$3") (pinfunction "P$3_P$3") (pintype "bidirectional"))
      (node (ref "U$1") (pin "7") (pinfunction "P7_ADO/SPIMISO_7") (pintype "bidirectional"))
    )
    (net (code "274") (name "Net-(U$1-P8_INT)") (class "Default")
      (node (ref "J130") (pin "P$1") (pinfunction "P$1_P$1") (pintype "bidirectional"))
      (node (ref "J130") (pin "P$2") (pinfunction "P$2_P$2") (pintype "bidirectional"))
      (node (ref "J130") (pin "P$3") (pinfunction "P$3_P$3") (pintype "bidirectional"))
      (node (ref "U$1") (pin "8") (pinfunction "P8_INT_8") (pintype "bidirectional"))
    )
    (net (code "275") (name "Net-(U$1-P9_NCS)") (class "Default")
      (node (ref "J131") (pin "P$1") (pinfunction "P$1_P$1") (pintype "bidirectional"))
      (node (ref "J131") (pin "P$2") (pinfunction "P$2_P$2") (pintype "bidirectional"))
      (node (ref "J131") (pin "P$3") (pinfunction "P$3_P$3") (pintype "bidirectional"))
      (node (ref "U$1") (pin "9") (pinfunction "P9_NCS_9") (pintype "bidirectional"))
    )
    (net (code "276") (name "Net-(U$1-P10_FSYNC)") (class "Default")
      (node (ref "J132") (pin "P$1") (pinfunction "P$1_P$1") (pintype "bidirectional"))
      (node (ref "J132") (pin "P$2") (pinfunction "P$2_P$2") (pintype "bidirectional"))
      (node (ref "J132") (pin "P$3") (pinfunction "P$3_P$3") (pintype "bidirectional"))
      (node (ref "U$1") (pin "10") (pinfunction "P10_FSYNC_10") (pintype "bidirectional"))
    )
    (net (code "277") (name "Net-(U1-MODE)") (class "Default")
      (node (ref "JP2") (pin "1") (pinfunction "1_1") (pintype "passive"))
      (node (ref "R4") (pin "1") (pinfunction "1_1") (pintype "passive"))
      (node (ref "U1") (pin "14") (pinfunction "MODE_14") (pintype "bidirectional"))
    )
    (net (code "278") (name "Net-(U1-PHASE)") (class "Default")
      (node (ref "J196") (pin "P$1") (pinfunction "P$1_P$1") (pintype "bidirectional"))
      (node (ref "J196") (pin "P$2") (pinfunction "P$2_P$2") (pintype "bidirectional"))
      (node (ref "J25") (pin "P$1") (pinfunction "P$1_P$1") (pintype "bidirectional"))
      (node (ref "J25") (pin "P$2") (pinfunction "P$2_P$2") (pintype "bidirectional"))
      (node (ref "U1") (pin "7") (pinfunction "PHASE_7") (pintype "bidirectional"))
    )
    (net (code "279") (name "Net-(U1-RC)") (class "Default")
      (node (ref "C14") (pin "1") (pinfunction "1_1") (pintype "passive"))
      (node (ref "R3") (pin "2") (pinfunction "2_2") (pintype "passive"))
      (node (ref "U1") (pin "3") (pinfunction "RC_3") (pintype "bidirectional"))
    )
    (net (code "280") (name "Net-(U1-~{BRAKE})") (class "Default")
      (node (ref "R8") (pin "1") (pinfunction "1_1") (pintype "passive"))
      (node (ref "U1") (pin "1") (pinfunction "~{BRAKE}_1") (pintype "bidirectional"))
    )
    (net (code "281") (name "Net-(U2-CPH)") (class "Default")
      (node (ref "C19") (pin "2") (pinfunction "2_2") (pintype "passive"))
      (node (ref "U2") (pin "P$13") (pinfunction "CPH_P$13") (pintype "bidirectional"))
    )
    (net (code "282") (name "Net-(U2-CPL)") (class "Default")
      (node (ref "C19") (pin "1") (pinfunction "1_1") (pintype "passive"))
      (node (ref "U2") (pin "P$14") (pinfunction "CPL_P$14") (pintype "bidirectional"))
    )
    (net (code "283") (name "Net-(U2-IPROPI)") (class "Default")
      (node (ref "R41") (pin "1") (pinfunction "1_1") (pintype "passive"))
      (node (ref "U2") (pin "P$6") (pinfunction "IPROPI_P$6") (pintype "bidirectional"))
    )
    (net (code "284") (name "Net-(U2-NFAULT)") (class "Default")
      (node (ref "J78") (pin "P$1") (pinfunction "P$1_P$1") (pintype "bidirectional"))
      (node (ref "J78") (pin "P$2") (pinfunction "P$2_P$2") (pintype "bidirectional"))
      (node (ref "R42") (pin "2") (pinfunction "2_2") (pintype "passive"))
      (node (ref "U2") (pin "P$4") (pinfunction "NFAULT_P$4") (pintype "bidirectional"))
    )
    (net (code "285") (name "Net-(U2-VCP)") (class "Default")
      (node (ref "C17") (pin "1") (pinfunction "1_1") (pintype "passive"))
      (node (ref "U2") (pin "P$12") (pinfunction "VCP_P$12") (pintype "bidirectional"))
    )
    (net (code "286") (name "Net-(U2-VREF)") (class "Default")
      (node (ref "TRIMPOT1") (pin "3") (pinfunction "3_3") (pintype "passive"))
      (node (ref "TRIMPOT1") (pin "4") (pinfunction "4_4") (pintype "passive"))
      (node (ref "U2") (pin "P$5") (pinfunction "VREF_P$5") (pintype "bidirectional"))
    )
    (net (code "287") (name "Net-(U3-P1_OSCI)") (class "Default")
      (node (ref "Q1") (pin "2") (pinfunction "2_2") (pintype "passive"))
      (node (ref "U3") (pin "1") (pinfunction "P1_OSCI_1") (pintype "bidirectional"))
    )
    (net (code "288") (name "Net-(U3-P2_OSC0)") (class "Default")
      (node (ref "Q1") (pin "1") (pinfunction "1_1") (pintype "passive"))
      (node (ref "U3") (pin "2") (pinfunction "P2_OSC0_2") (pintype "bidirectional"))
    )
    (net (code "289") (name "Net-(U3-P3_VBACK)") (class "Default")
      (node (ref "G1") (pin "+") (pinfunction "+_+") (pintype "passive"))
      (node (ref "U3") (pin "3") (pinfunction "P3_VBACK_3") (pintype "bidirectional"))
    )
    (net (code "290") (name "Net-(U3-P7_IRQ)") (class "Default")
      (node (ref "J1") (pin "P$1") (pinfunction "P$1_P$1") (pintype "bidirectional"))
      (node (ref "J1") (pin "P$2") (pinfunction "P$2_P$2") (pintype "bidirectional"))
      (node (ref "J1") (pin "P$3") (pinfunction "P$3_P$3") (pintype "bidirectional"))
      (node (ref "U3") (pin "7") (pinfunction "P7_IRQ_7") (pintype "bidirectional"))
    )
    (net (code "291") (name "Net-(U4-CPH)") (class "Default")
      (node (ref "C24") (pin "2") (pinfunction "2_2") (pintype "passive"))
      (node (ref "U4") (pin "P$13") (pinfunction "CPH_P$13") (pintype "bidirectional"))
    )
    (net (code "292") (name "Net-(U4-CPL)") (class "Default")
      (node (ref "C24") (pin "1") (pinfunction "1_1") (pintype "passive"))
      (node (ref "U4") (pin "P$14") (pinfunction "CPL_P$14") (pintype "bidirectional"))
    )
    (net (code "293") (name "Net-(U4-IPROPI)") (class "Default")
      (node (ref "R43") (pin "1") (pinfunction "1_1") (pintype "passive"))
      (node (ref "U4") (pin "P$6") (pinfunction "IPROPI_P$6") (pintype "bidirectional"))
    )
    (net (code "294") (name "Net-(U4-NFAULT)") (class "Default")
      (node (ref "J81") (pin "P$1") (pinfunction "P$1_P$1") (pintype "bidirectional"))
      (node (ref "J81") (pin "P$2") (pinfunction "P$2_P$2") (pintype "bidirectional"))
      (node (ref "R44") (pin "2") (pinfunction "2_2") (pintype "passive"))
      (node (ref "U4") (pin "P$4") (pinfunction "NFAULT_P$4") (pintype "bidirectional"))
    )
    (net (code "295") (name "Net-(U4-VCP)") (class "Default")
      (node (ref "C23") (pin "1") (pinfunction "1_1") (pintype "passive"))
      (node (ref "U4") (pin "P$12") (pinfunction "VCP_P$12") (pintype "bidirectional"))
    )
    (net (code "296") (name "Net-(U4-VREF)") (class "Default")
      (node (ref "TRIMPOT2") (pin "3") (pinfunction "3_3") (pintype "passive"))
      (node (ref "TRIMPOT2") (pin "4") (pinfunction "4_4") (pintype "passive"))
      (node (ref "U4") (pin "P$5") (pinfunction "VREF_P$5") (pintype "bidirectional"))
    )
    (net (code "297") (name "Net-(U5-MODE)") (class "Default")
      (node (ref "JP3") (pin "1") (pinfunction "1_1") (pintype "passive"))
      (node (ref "R5") (pin "1") (pinfunction "1_1") (pintype "passive"))
      (node (ref "U5") (pin "14") (pinfunction "MODE_14") (pintype "bidirectional"))
    )
    (net (code "298") (name "Net-(U5-PHASE)") (class "Default")
      (node (ref "J197") (pin "P$1") (pinfunction "P$1_P$1") (pintype "bidirectional"))
      (node (ref "J197") (pin "P$2") (pinfunction "P$2_P$2") (pintype "bidirectional"))
      (node (ref "J34") (pin "P$1") (pinfunction "P$1_P$1") (pintype "bidirectional"))
      (node (ref "J34") (pin "P$2") (pinfunction "P$2_P$2") (pintype "bidirectional"))
      (node (ref "U5") (pin "7") (pinfunction "PHASE_7") (pintype "bidirectional"))
    )
    (net (code "299") (name "Net-(U5-RC)") (class "Default")
      (node (ref "C2") (pin "1") (pinfunction "1_1") (pintype "passive"))
      (node (ref "R7") (pin "2") (pinfunction "2_2") (pintype "passive"))
      (node (ref "U5") (pin "3") (pinfunction "RC_3") (pintype "bidirectional"))
    )
    (net (code "300") (name "Net-(U5-~{BRAKE})") (class "Default")
      (node (ref "R6") (pin "1") (pinfunction "1_1") (pintype "passive"))
      (node (ref "U5") (pin "1") (pinfunction "~{BRAKE}_1") (pintype "bidirectional"))
    )
    (net (code "301") (name "Net-(U6-IN2)") (class "Default")
      (node (ref "SV10") (pin "2") (pinfunction "2_2") (pintype "passive"))
      (node (ref "U6") (pin "P$2") (pinfunction "IN2_P$2") (pintype "bidirectional"))
    )
    (net (code "302") (name "Net-(U6-IN3)") (class "Default")
      (node (ref "SV10") (pin "3") (pinfunction "3_3") (pintype "passive"))
      (node (ref "U6") (pin "P$3") (pinfunction "IN3_P$3") (pintype "bidirectional"))
    )
    (net (code "303") (name "Net-(U6-OUT1)") (class "Default")
      (node (ref "SV9") (pin "1") (pinfunction "1_1") (pintype "passive"))
      (node (ref "U6") (pin "P$7") (pinfunction "OUT1_P$7") (pintype "bidirectional"))
    )
    (net (code "304") (name "Net-(U6-OUT3)") (class "Default")
      (node (ref "SV9") (pin "3") (pinfunction "3_3") (pintype "passive"))
      (node (ref "U6") (pin "P$5") (pinfunction "OUT3_P$5") (pintype "bidirectional"))
    )
    (net (code "305") (name "Net-(U7-~{HOLD})") (class "Default")
      (node (ref "R25") (pin "1") (pinfunction "1_1") (pintype "passive"))
      (node (ref "U7") (pin "7") (pinfunction "~{HOLD}_7") (pintype "bidirectional"))
    )
    (net (code "306") (name "Net-(U8-VDD)") (class "Default")
      (node (ref "C11") (pin "1") (pinfunction "1_1") (pintype "passive"))
      (node (ref "U8") (pin "1") (pinfunction "VDD_1") (pintype "bidirectional"))
    )
    (net (code "307") (name "Net-(U8-VDD2)") (class "Default")
      (node (ref "C8") (pin "1") (pinfunction "1_1") (pintype "passive"))
      (node (ref "U8") (pin "11") (pinfunction "VDD2_11") (pintype "bidirectional"))
    )
    (net (code "308") (name "Net-(U8-{slash}XRS)") (class "Default")
      (node (ref "P1") (pin "1") (pinfunction "1_1") (pintype "bidirectional"))
      (node (ref "R38") (pin "1") (pinfunction "1_1") (pintype "passive"))
      (node (ref "U8") (pin "17") (pinfunction "/XRS_17") (pintype "bidirectional"))
    )
    (net (code "309") (name "POWER") (class "Default")
      (node (ref "B2") (pin "P$1") (pinfunction "BAT+_P$1") (pintype "bidirectional"))
      (node (ref "C1") (pin "+") (pinfunction "+_+") (pintype "passive"))
      (node (ref "C12") (pin "+") (pinfunction "+_+") (pintype "passive"))
      (node (ref "C13") (pin "+") (pinfunction "+_+") (pintype "passive"))
      (node (ref "C15") (pin "+") (pinfunction "+_+") (pintype "passive"))
      (node (ref "C16") (pin "1") (pinfunction "1_1") (pintype "passive"))
      (node (ref "C17") (pin "2") (pinfunction "2_2") (pintype "passive"))
      (node (ref "C20") (pin "+") (pinfunction "+_+") (pintype "passive"))
      (node (ref "C22") (pin "1") (pinfunction "1_1") (pintype "passive"))
      (node (ref "C23") (pin "2") (pinfunction "2_2") (pintype "passive"))
      (node (ref "C25") (pin "+") (pinfunction "+_+") (pintype "passive"))
      (node (ref "C27") (pin "+") (pinfunction "+_+") (pintype "passive"))
      (node (ref "C28") (pin "+") (pinfunction "+_+") (pintype "passive"))
      (node (ref "DCDC3.3V") (pin "1") (pinfunction "1_1") (pintype "passive"))
      (node (ref "DCDC5V") (pin "1") (pinfunction "1_1") (pintype "passive"))
      (node (ref "J5") (pin "1") (pinfunction "1_1") (pintype "passive"))
      (node (ref "POWER") (pin "2") (pinfunction "2_2") (pintype "passive"))
      (node (ref "S141") (pin "P$1") (pinfunction "P$1_P$1") (pintype "bidirectional"))
      (node (ref "S141") (pin "P$2") (pinfunction "P$2_P$2") (pintype "bidirectional"))
      (node (ref "S141") (pin "P$3") (pinfunction "P$3_P$3") (pintype "bidirectional"))
      (node (ref "S141") (pin "P$4") (pinfunction "P$4_P$4") (pintype "bidirectional"))
      (node (ref "S141") (pin "P$5") (pinfunction "P$5_P$5") (pintype "bidirectional"))
      (node (ref "U1") (pin "16") (pinfunction "VBB_16") (pintype "bidirectional"))
      (node (ref "U1") (pin "9") (pinfunction "VBB_9") (pintype "bidirectional"))
      (node (ref "U2") (pin "P$11") (pinfunction "VM_P$11") (pintype "bidirectional"))
      (node (ref "U4") (pin "P$11") (pinfunction "VM_P$11") (pintype "bidirectional"))
      (node (ref "U5") (pin "16") (pinfunction "VBB_16") (pintype "bidirectional"))
      (node (ref "U5") (pin "9") (pinfunction "VBB_9") (pintype "bidirectional"))
    )
    (net (code "310") (name "RESET") (class "Default")
      (node (ref "J98") (pin "P$1") (pinfunction "P$1_P$1") (pintype "bidirectional"))
      (node (ref "J98") (pin "P$2") (pinfunction "P$2_P$2") (pintype "bidirectional"))
      (node (ref "J98") (pin "P$3") (pinfunction "P$3_P$3") (pintype "bidirectional"))
      (node (ref "L1") (pin "P$16") (pinfunction "RST_P$16") (pintype "bidirectional"))
    )
    (net (code "311") (name "RESET_2") (class "Default")
      (node (ref "J157") (pin "P$1") (pinfunction "P$1_P$1") (pintype "bidirectional"))
      (node (ref "J157") (pin "P$2") (pinfunction "P$2_P$2") (pintype "bidirectional"))
      (node (ref "J157") (pin "P$3") (pinfunction "P$3_P$3") (pintype "bidirectional"))
      (node (ref "L1") (pin "P$56") (pinfunction "RST_2_P$56") (pintype "bidirectional"))
    )
    (net (code "312") (name "SCL") (class "Default")
      (node (ref "J2") (pin "P$1") (pinfunction "P$1_P$1") (pintype "bidirectional"))
      (node (ref "J2") (pin "P$2") (pinfunction "P$2_P$2") (pintype "bidirectional"))
      (node (ref "J2") (pin "P$3") (pinfunction "P$3_P$3") (pintype "bidirectional"))
      (node (ref "U3") (pin "6") (pinfunction "P6_SCL_6") (pintype "bidirectional"))
    )
    (net (code "313") (name "SDA") (class "Default")
      (node (ref "J3") (pin "P$1") (pinfunction "P$1_P$1") (pintype "bidirectional"))
      (node (ref "J3") (pin "P$2") (pinfunction "P$2_P$2") (pintype "bidirectional"))
      (node (ref "J3") (pin "P$3") (pinfunction "P$3_P$3") (pintype "bidirectional"))
      (node (ref "U3") (pin "5") (pinfunction "P5_SDA_5") (pintype "bidirectional"))
    )
    (net (code "314") (name "TCK") (class "Default")
      (node (ref "SV14") (pin "11") (pinfunction "11_11") (pintype "passive"))
      (node (ref "SV14") (pin "9") (pinfunction "9_9") (pintype "passive"))
      (node (ref "U8") (pin "31") (pinfunction "GPIO38/XCLKIN(TCK)_31") (pintype "bidirectional"))
    )
    (net (code "315") (name "TDI") (class "Default")
      (node (ref "SV14") (pin "3") (pinfunction "3_3") (pintype "passive"))
      (node (ref "U8") (pin "28") (pinfunction "GPIO35(TDI)_28") (pintype "bidirectional"))
    )
    (net (code "316") (name "TDO") (class "Default")
      (node (ref "R33") (pin "2") (pinfunction "2_2") (pintype "passive"))
      (node (ref "SV14") (pin "7") (pinfunction "7_7") (pintype "passive"))
      (node (ref "U8") (pin "30") (pinfunction "GPIO37(TDO)_30") (pintype "bidirectional"))
    )
    (net (code "317") (name "TMS") (class "Default")
      (node (ref "SV14") (pin "1") (pinfunction "1_1") (pintype "passive"))
      (node (ref "U8") (pin "29") (pinfunction "GPIO36(TMS)_29") (pintype "bidirectional"))
    )
    (net (code "318") (name "TRSTN") (class "Default")
      (node (ref "R32") (pin "1") (pinfunction "1_1") (pintype "passive"))
      (node (ref "SV14") (pin "2") (pinfunction "2_2") (pintype "passive"))
      (node (ref "U8") (pin "16") (pinfunction "/TRST_16") (pintype "bidirectional"))
    )
    (net (code "319") (name "VCC") (class "Default")
      (node (ref "C10") (pin "1") (pinfunction "1_1") (pintype "passive"))
      (node (ref "C18") (pin "1") (pinfunction "1_1") (pintype "passive"))
      (node (ref "C21") (pin "1") (pinfunction "1_1") (pintype "passive"))
      (node (ref "C3") (pin "1") (pinfunction "1_1") (pintype "passive"))
      (node (ref "C4") (pin "1") (pinfunction "1_1") (pintype "passive"))
      (node (ref "C5") (pin "1") (pinfunction "1_1") (pintype "passive"))
      (node (ref "C6") (pin "1") (pinfunction "1_1") (pintype "passive"))
      (node (ref "C7") (pin "1") (pinfunction "1_1") (pintype "passive"))
      (node (ref "C9") (pin "1") (pinfunction "1_1") (pintype "passive"))
      (node (ref "DCDC3.3V") (pin "3") (pinfunction "3_3") (pintype "passive"))
      (node (ref "ETH1") (pin "P$10") (pinfunction "3V3_1_P$10") (pintype "bidirectional"))
      (node (ref "ETH1") (pin "P$11") (pinfunction "3V3_2_P$11") (pintype "bidirectional"))
      (node (ref "IC1") (pin "14") (pinfunction "VCC_14") (pintype "power_in"))
      (node (ref "IC2") (pin "14") (pinfunction "VCC_14") (pintype "power_in"))
      (node (ref "IC3") (pin "14") (pinfunction "VCC_14") (pintype "power_in"))
      (node (ref "J10") (pin "P$1") (pinfunction "P$1_P$1") (pintype "bidirectional"))
      (node (ref "J10") (pin "P$2") (pinfunction "P$2_P$2") (pintype "bidirectional"))
      (node (ref "J10") (pin "P$3") (pinfunction "P$3_P$3") (pintype "bidirectional"))
      (node (ref "J123") (pin "P$1") (pinfunction "P$1_P$1") (pintype "bidirectional"))
      (node (ref "J123") (pin "P$2") (pinfunction "P$2_P$2") (pintype "bidirectional"))
      (node (ref "J123") (pin "P$3") (pinfunction "P$3_P$3") (pintype "bidirectional"))
      (node (ref "J177") (pin "P$1") (pinfunction "P$1_P$1") (pintype "bidirectional"))
      (node (ref "J177") (pin "P$2") (pinfunction "P$2_P$2") (pintype "bidirectional"))
      (node (ref "J177") (pin "P$3") (pinfunction "P$3_P$3") (pintype "bidirectional"))
      (node (ref "L1") (pin "P$1") (pinfunction "3.3V_1_P$1") (pintype "bidirectional"))
      (node (ref "L1") (pin "P$41") (pinfunction "3.3V_2_P$41") (pintype "bidirectional"))
      (node (ref "R10") (pin "1") (pinfunction "1_1") (pintype "passive"))
      (node (ref "R11") (pin "2") (pinfunction "2_2") (pintype "passive"))
      (node (ref "R12") (pin "2") (pinfunction "2_2") (pintype "passive"))
      (node (ref "R13") (pin "2") (pinfunction "2_2") (pintype "passive"))
      (node (ref "R14") (pin "2") (pinfunction "2_2") (pintype "passive"))
      (node (ref "R15") (pin "2") (pinfunction "2_2") (pintype "passive"))
      (node (ref "R16") (pin "2") (pinfunction "2_2") (pintype "passive"))
      (node (ref "R17") (pin "2") (pinfunction "2_2") (pintype "passive"))
      (node (ref "R18") (pin "2") (pinfunction "2_2") (pintype "passive"))
      (node (ref "R19") (pin "2") (pinfunction "2_2") (pintype "passive"))
      (node (ref "R20") (pin "2") (pinfunction "2_2") (pintype "passive"))
      (node (ref "R21") (pin "2") (pinfunction "2_2") (pintype "passive"))
      (node (ref "R22") (pin "2") (pinfunction "2_2") (pintype "passive"))
      (node (ref "R23") (pin "2") (pinfunction "2_2") (pintype "passive"))
      (node (ref "R24") (pin "2") (pinfunction "2_2") (pintype "passive"))
      (node (ref "R25") (pin "2") (pinfunction "2_2") (pintype "passive"))
      (node (ref "R27") (pin "2") (pinfunction "2_2") (pintype "passive"))
      (node (ref "R28") (pin "2") (pinfunction "2_2") (pintype "passive"))
      (node (ref "R29") (pin "2") (pinfunction "2_2") (pintype "passive"))
      (node (ref "R30") (pin "2") (pinfunction "2_2") (pintype "passive"))
      (node (ref "R31") (pin "2") (pinfunction "2_2") (pintype "passive"))
      (node (ref "R33") (pin "1") (pinfunction "1_1") (pintype "passive"))
      (node (ref "R34") (pin "1") (pinfunction "1_1") (pintype "passive"))
      (node (ref "R35") (pin "1") (pinfunction "1_1") (pintype "passive"))
      (node (ref "R36") (pin "2") (pinfunction "2_2") (pintype "passive"))
      (node (ref "R37") (pin "2") (pinfunction "2_2") (pintype "passive"))
      (node (ref "R38") (pin "2") (pinfunction "2_2") (pintype "passive"))
      (node (ref "R39") (pin "2") (pinfunction "2_2") (pintype "passive"))
      (node (ref "R4") (pin "2") (pinfunction "2_2") (pintype "passive"))
      (node (ref "R42") (pin "1") (pinfunction "1_1") (pintype "passive"))
      (node (ref "R44") (pin "1") (pinfunction "1_1") (pintype "passive"))
      (node (ref "R5") (pin "2") (pinfunction "2_2") (pintype "passive"))
      (node (ref "R6") (pin "2") (pinfunction "2_2") (pintype "passive"))
      (node (ref "R8") (pin "2") (pinfunction "2_2") (pintype "passive"))
      (node (ref "R9") (pin "1") (pinfunction "1_1") (pintype "passive"))
      (node (ref "S53") (pin "P$1") (pinfunction "P$1_P$1") (pintype "bidirectional"))
      (node (ref "S53") (pin "P$10") (pinfunction "P$10_P$10") (pintype "bidirectional"))
      (node (ref "S53") (pin "P$2") (pinfunction "P$2_P$2") (pintype "bidirectional"))
      (node (ref "S53") (pin "P$3") (pinfunction "P$3_P$3") (pintype "bidirectional"))
      (node (ref "S53") (pin "P$4") (pinfunction "P$4_P$4") (pintype "bidirectional"))
      (node (ref "S53") (pin "P$5") (pinfunction "P$5_P$5") (pintype "bidirectional"))
      (node (ref "S53") (pin "P$6") (pinfunction "P$6_P$6") (pintype "bidirectional"))
      (node (ref "S53") (pin "P$7") (pinfunction "P$7_P$7") (pintype "bidirectional"))
      (node (ref "S53") (pin "P$8") (pinfunction "P$8_P$8") (pintype "bidirectional"))
      (node (ref "S53") (pin "P$9") (pinfunction "P$9_P$9") (pintype "bidirectional"))
      (node (ref "S58") (pin "P$1") (pinfunction "P$1_P$1") (pintype "bidirectional"))
      (node (ref "S58") (pin "P$10") (pinfunction "P$10_P$10") (pintype "bidirectional"))
      (node (ref "S58") (pin "P$2") (pinfunction "P$2_P$2") (pintype "bidirectional"))
      (node (ref "S58") (pin "P$3") (pinfunction "P$3_P$3") (pintype "bidirectional"))
      (node (ref "S58") (pin "P$4") (pinfunction "P$4_P$4") (pintype "bidirectional"))
      (node (ref "S58") (pin "P$5") (pinfunction "P$5_P$5") (pintype "bidirectional"))
      (node (ref "S58") (pin "P$6") (pinfunction "P$6_P$6") (pintype "bidirectional"))
      (node (ref "S58") (pin "P$7") (pinfunction "P$7_P$7") (pintype "bidirectional"))
      (node (ref "S58") (pin "P$8") (pinfunction "P$8_P$8") (pintype "bidirectional"))
      (node (ref "S58") (pin "P$9") (pinfunction "P$9_P$9") (pintype "bidirectional"))
      (node (ref "SV11") (pin "2") (pinfunction "2_2") (pintype "passive"))
      (node (ref "SV12") (pin "2") (pinfunction "2_2") (pintype "passive"))
      (node (ref "SV13") (pin "3") (pinfunction "3_3") (pintype "passive"))
      (node (ref "SV13") (pin "7") (pinfunction "7_7") (pintype "passive"))
      (node (ref "SV14") (pin "5") (pinfunction "5_5") (pintype "passive"))
      (node (ref "SV16") (pin "1") (pinfunction "1_1") (pintype "passive"))
      (node (ref "SV16") (pin "2") (pinfunction "2_2") (pintype "passive"))
      (node (ref "SV18") (pin "1") (pinfunction "1_1") (pintype "passive"))
      (node (ref "SV6") (pin "1") (pinfunction "1_1") (pintype "passive"))
      (node (ref "SV6") (pin "2") (pinfunction "2_2") (pintype "passive"))
      (node (ref "TRIMPOT1") (pin "1") (pinfunction "1_1") (pintype "passive"))
      (node (ref "TRIMPOT1") (pin "2") (pinfunction "2_2") (pintype "passive"))
      (node (ref "TRIMPOT2") (pin "1") (pinfunction "1_1") (pintype "passive"))
      (node (ref "TRIMPOT2") (pin "2") (pinfunction "2_2") (pintype "passive"))
      (node (ref "U$1") (pin "1") (pinfunction "P1_VCC_1") (pintype "bidirectional"))
      (node (ref "U1") (pin "2") (pinfunction "REF_2") (pintype "bidirectional"))
      (node (ref "U1") (pin "6") (pinfunction "VCC_6") (pintype "bidirectional"))
      (node (ref "U3") (pin "8") (pinfunction "P8_VCC_8") (pintype "bidirectional"))
      (node (ref "U5") (pin "2") (pinfunction "REF_2") (pintype "bidirectional"))
      (node (ref "U5") (pin "6") (pinfunction "VCC_6") (pintype "bidirectional"))
      (node (ref "U6") (pin "P$8") (pinfunction "V+_P$8") (pintype "bidirectional"))
      (node (ref "U7") (pin "8") (pinfunction "VCC_8") (pintype "bidirectional"))
      (node (ref "U8") (pin "22") (pinfunction "VDDA_22") (pintype "bidirectional"))
      (node (ref "U8") (pin "4") (pinfunction "VDDIO_4") (pintype "bidirectional"))
    )
    (net (code "320") (name "unconnected-(ETH1-NC-PadP$9)") (class "Default")
      (node (ref "ETH1") (pin "P$9") (pinfunction "NC_P$9") (pintype "bidirectional"))
    )
    (net (code "321") (name "unconnected-(G1-+-Pad+@1)") (class "Default")
      (node (ref "G1") (pin "+@1") (pinfunction "+_+@1") (pintype "passive"))
    )
    (net (code "322") (name "unconnected-(J8-PadP$1)") (class "Default")
      (node (ref "J8") (pin "P$1") (pinfunction "P$1_P$1") (pintype "bidirectional"))
    )
    (net (code "323") (name "unconnected-(J8-PadP$2)") (class "Default")
      (node (ref "J8") (pin "P$2") (pinfunction "P$2_P$2") (pintype "bidirectional"))
    )
    (net (code "324") (name "unconnected-(SV12-Pad3)") (class "Default")
      (node (ref "SV12") (pin "3") (pinfunction "3_3") (pintype "passive"))
    )
    (net (code "325") (name "unconnected-(SV12-Pad5)") (class "Default")
      (node (ref "SV12") (pin "5") (pinfunction "5_5") (pintype "passive"))
    )
    (net (code "326") (name "unconnected-(SV13-Pad4)") (class "Default")
      (node (ref "SV13") (pin "4") (pinfunction "4_4") (pintype "passive"))
    )
    (net (code "327") (name "unconnected-(SV13-Pad6)") (class "Default")
      (node (ref "SV13") (pin "6") (pinfunction "6_6") (pintype "passive"))
    )
    (net (code "328") (name "unconnected-(SV14-Pad6)") (class "Default")
      (node (ref "SV14") (pin "6") (pinfunction "6_6") (pintype "passive"))
    )
    (net (code "329") (name "unconnected-(SV14-Pad13)") (class "Default")
      (node (ref "SV14") (pin "13") (pinfunction "13_13") (pintype "passive"))
    )
    (net (code "330") (name "unconnected-(SV14-Pad14)") (class "Default")
      (node (ref "SV14") (pin "14") (pinfunction "14_14") (pintype "passive"))
    )
    (net (code "331") (name "unconnected-(U7-DNU-Pad3)") (class "Default")
      (node (ref "U7") (pin "3") (pinfunction "DNU_3") (pintype "bidirectional"))
    )
    (net (code "332") (name "unconnected-(U8-TEST-Pad38)") (class "Default")
      (node (ref "U8") (pin "38") (pinfunction "TEST_38") (pintype "bidirectional"))
    )
  )
)
